# Main_Board.net
KiCad netlist of a schematic drawn in EAGLE
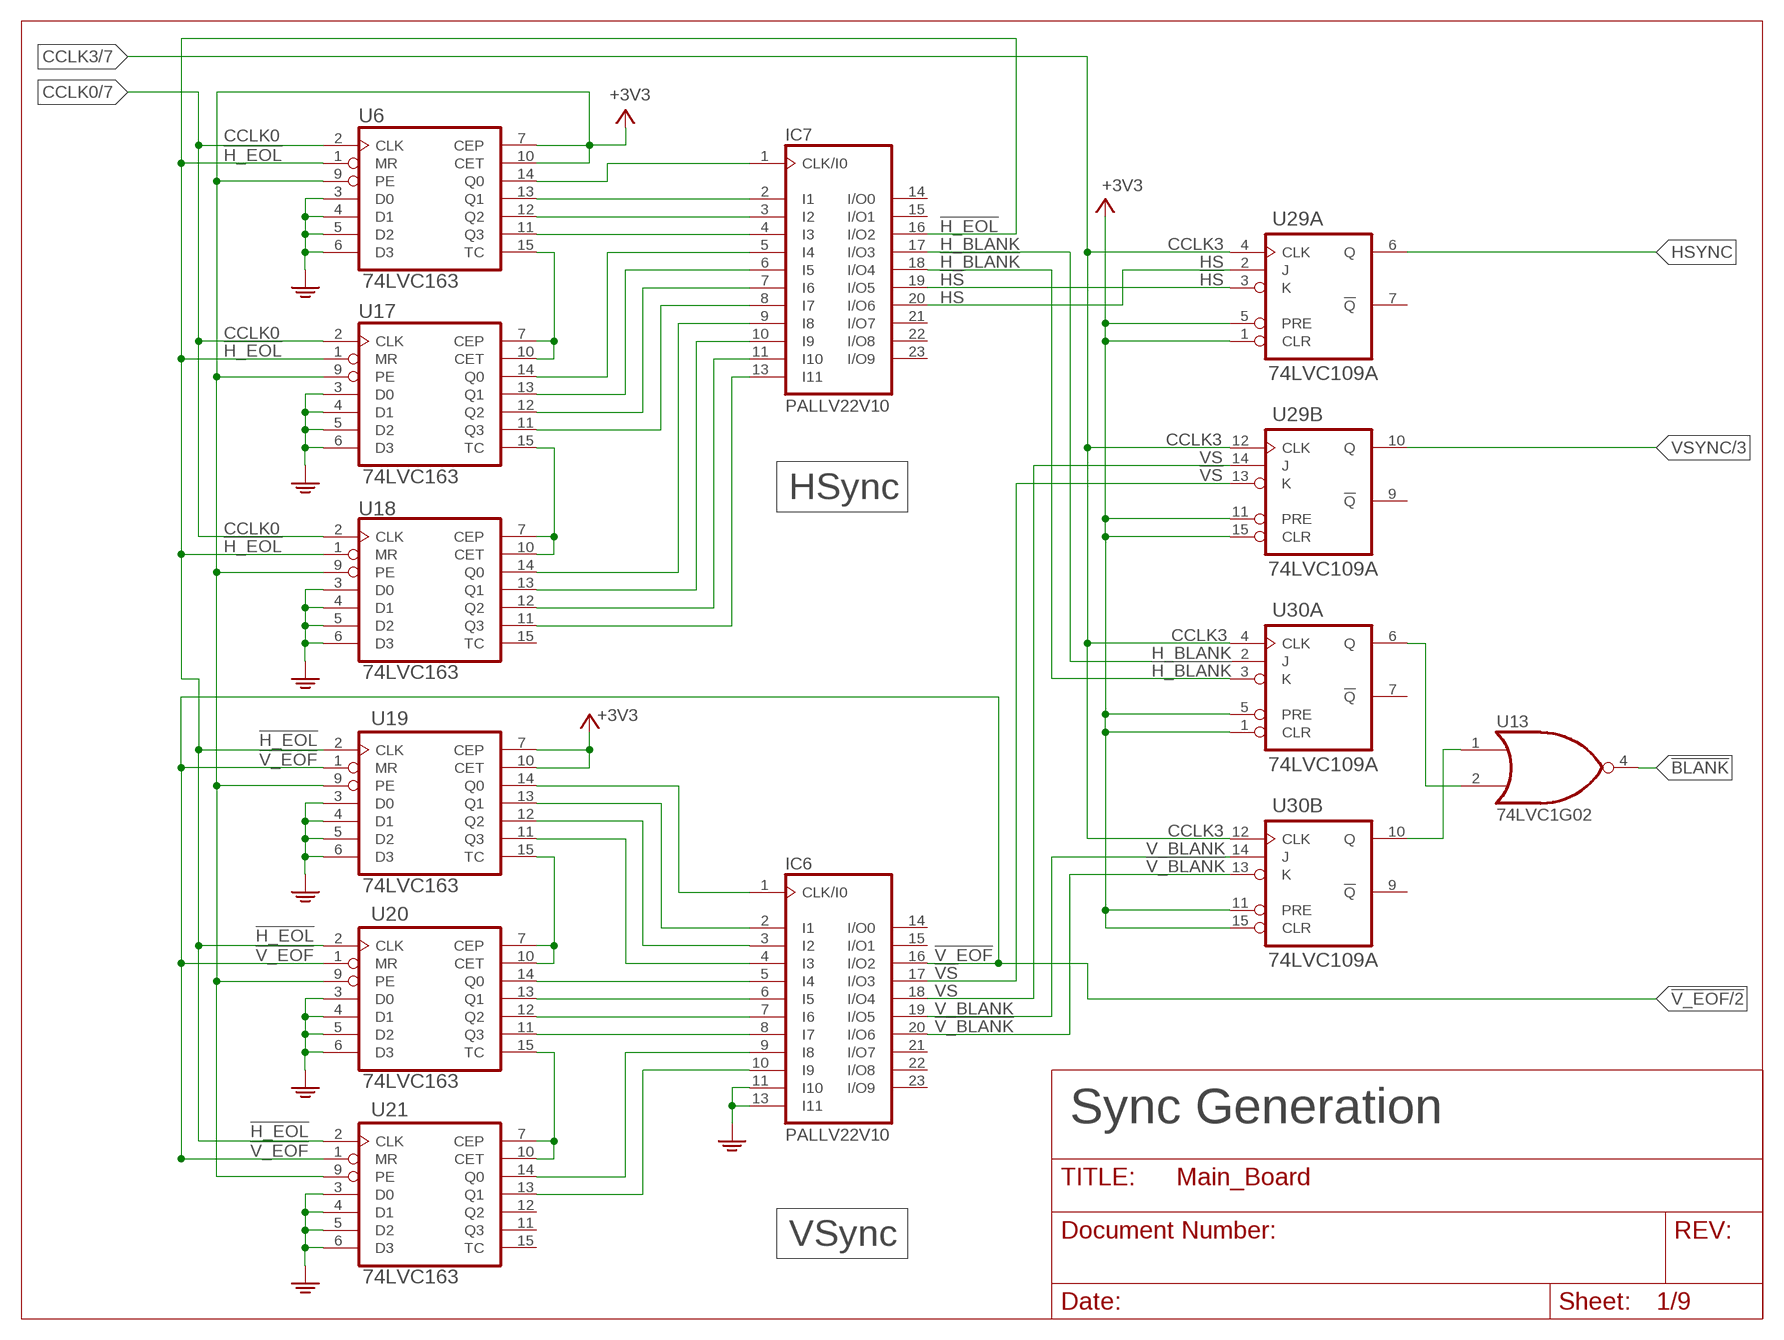
[diagram p0: schematic, sheet 1]
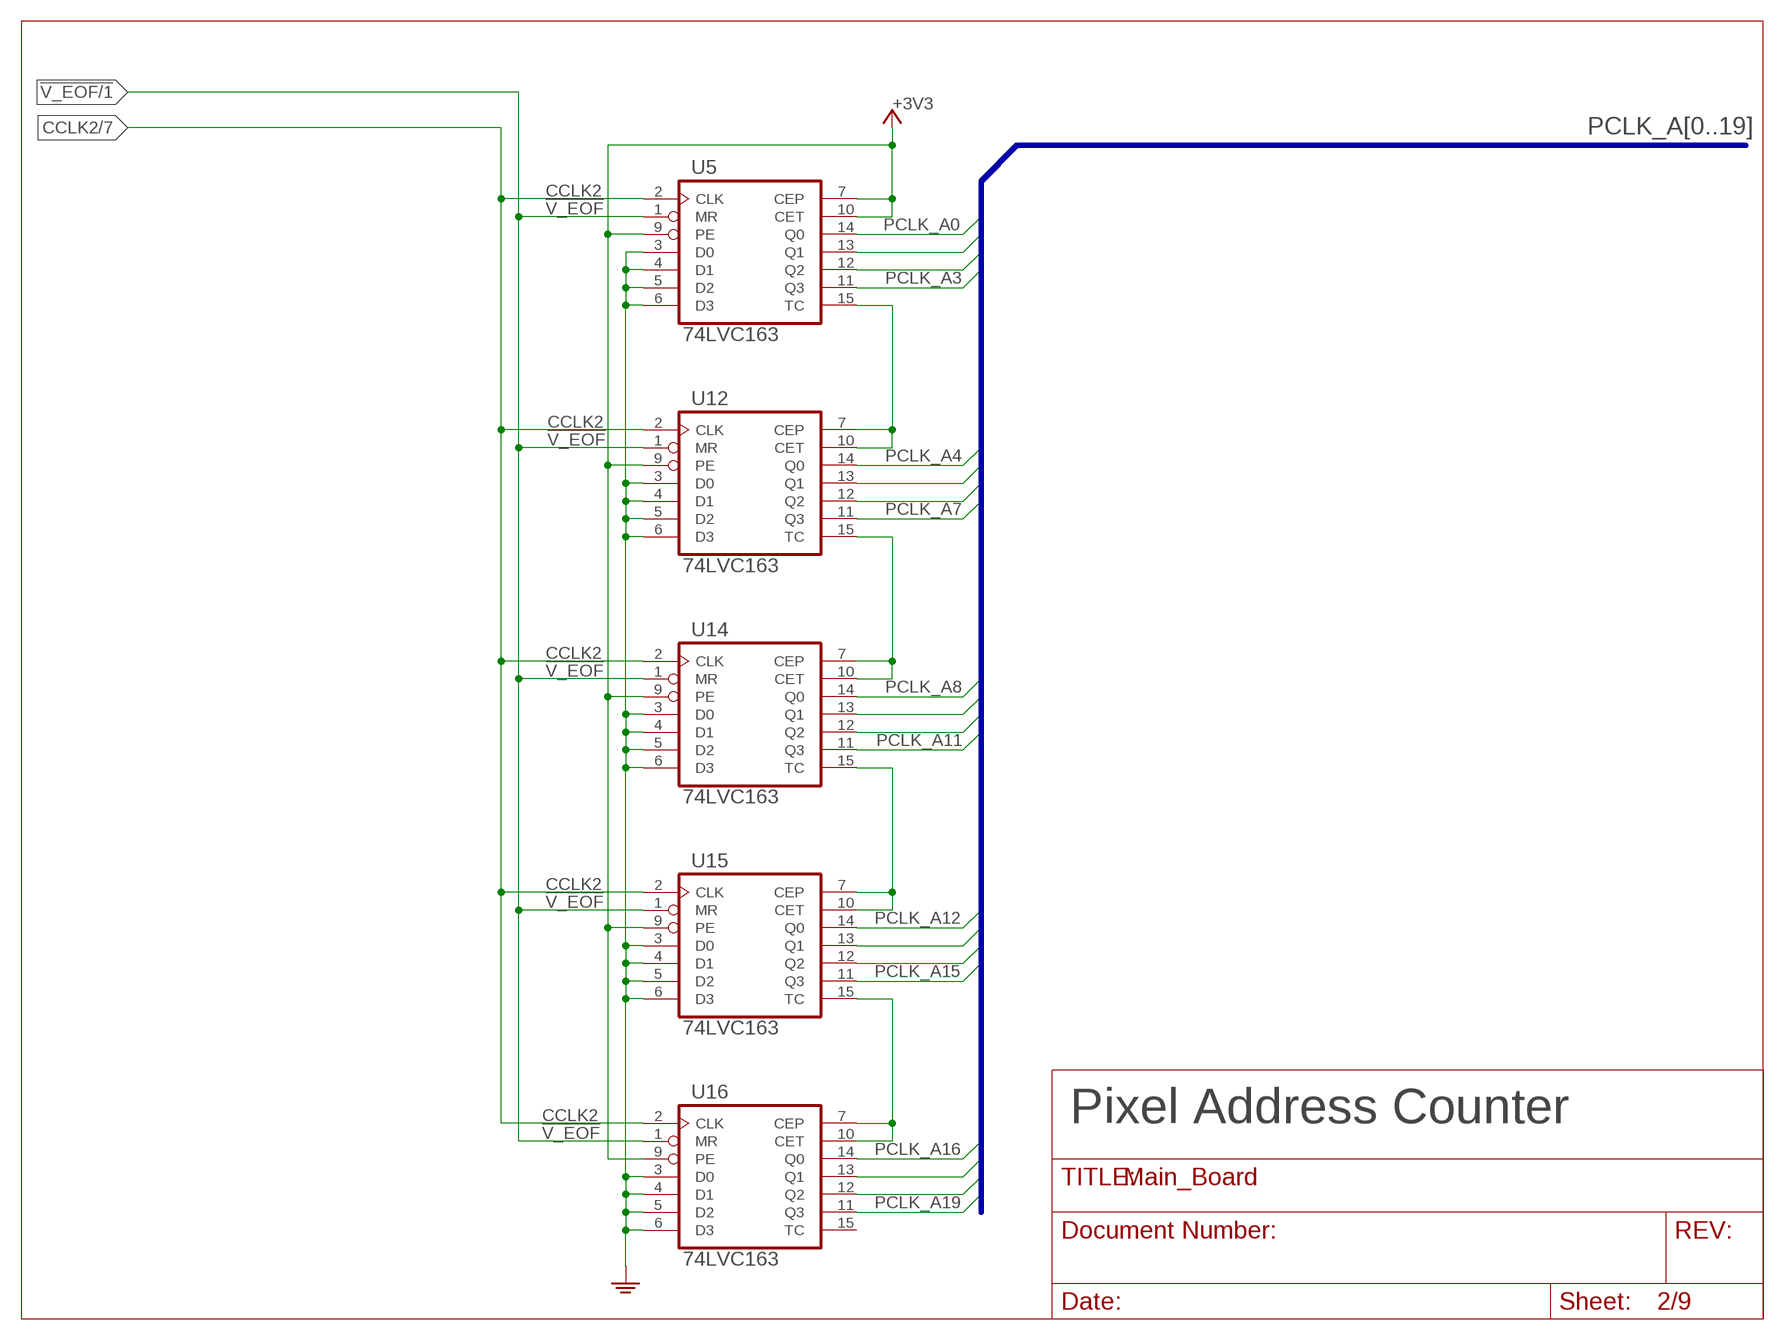
[diagram p1: schematic, sheet 2]
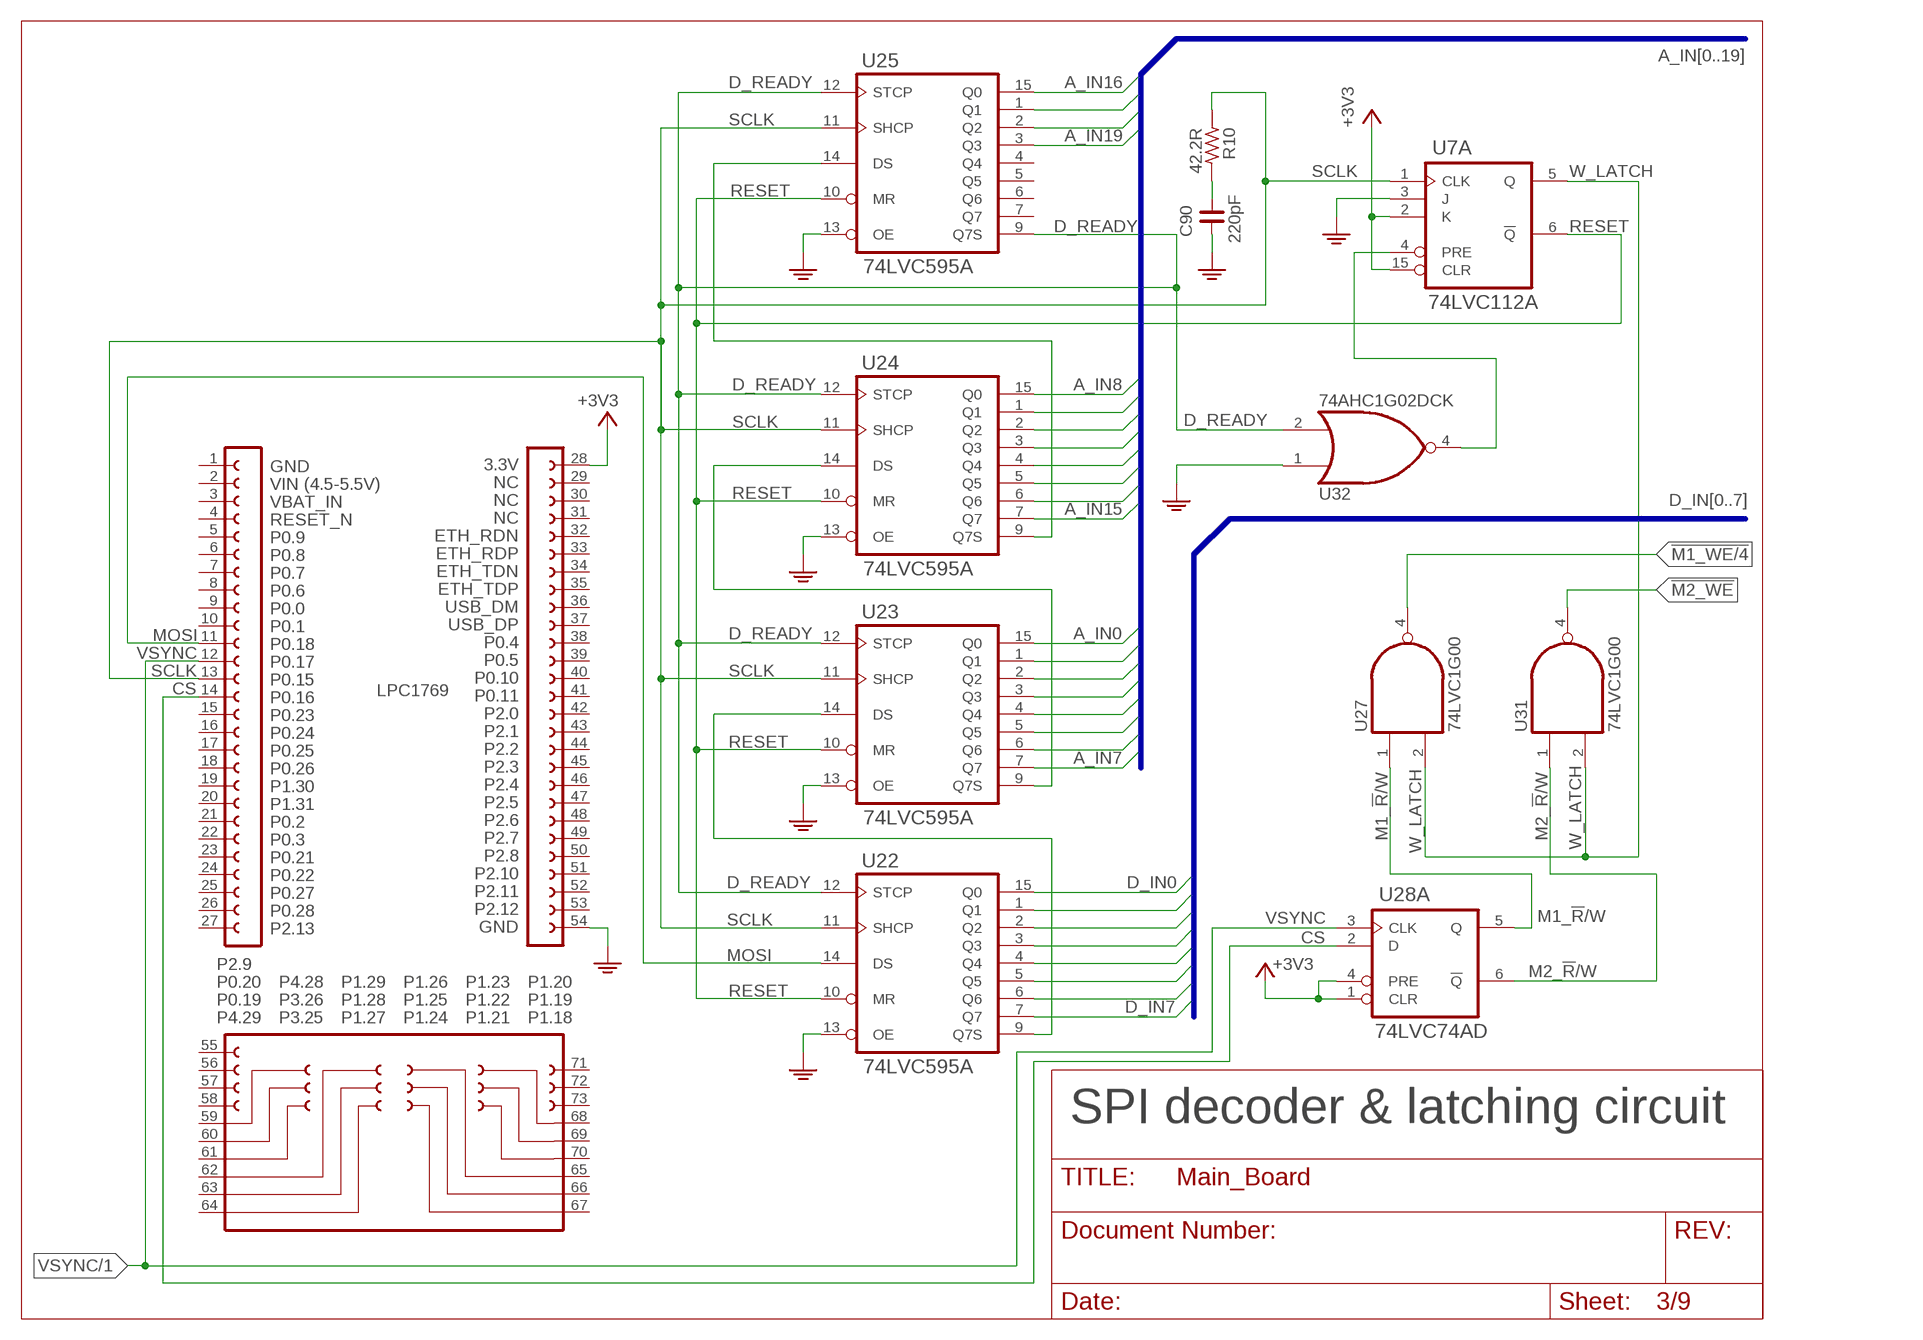
[diagram p2: schematic, sheet 3]
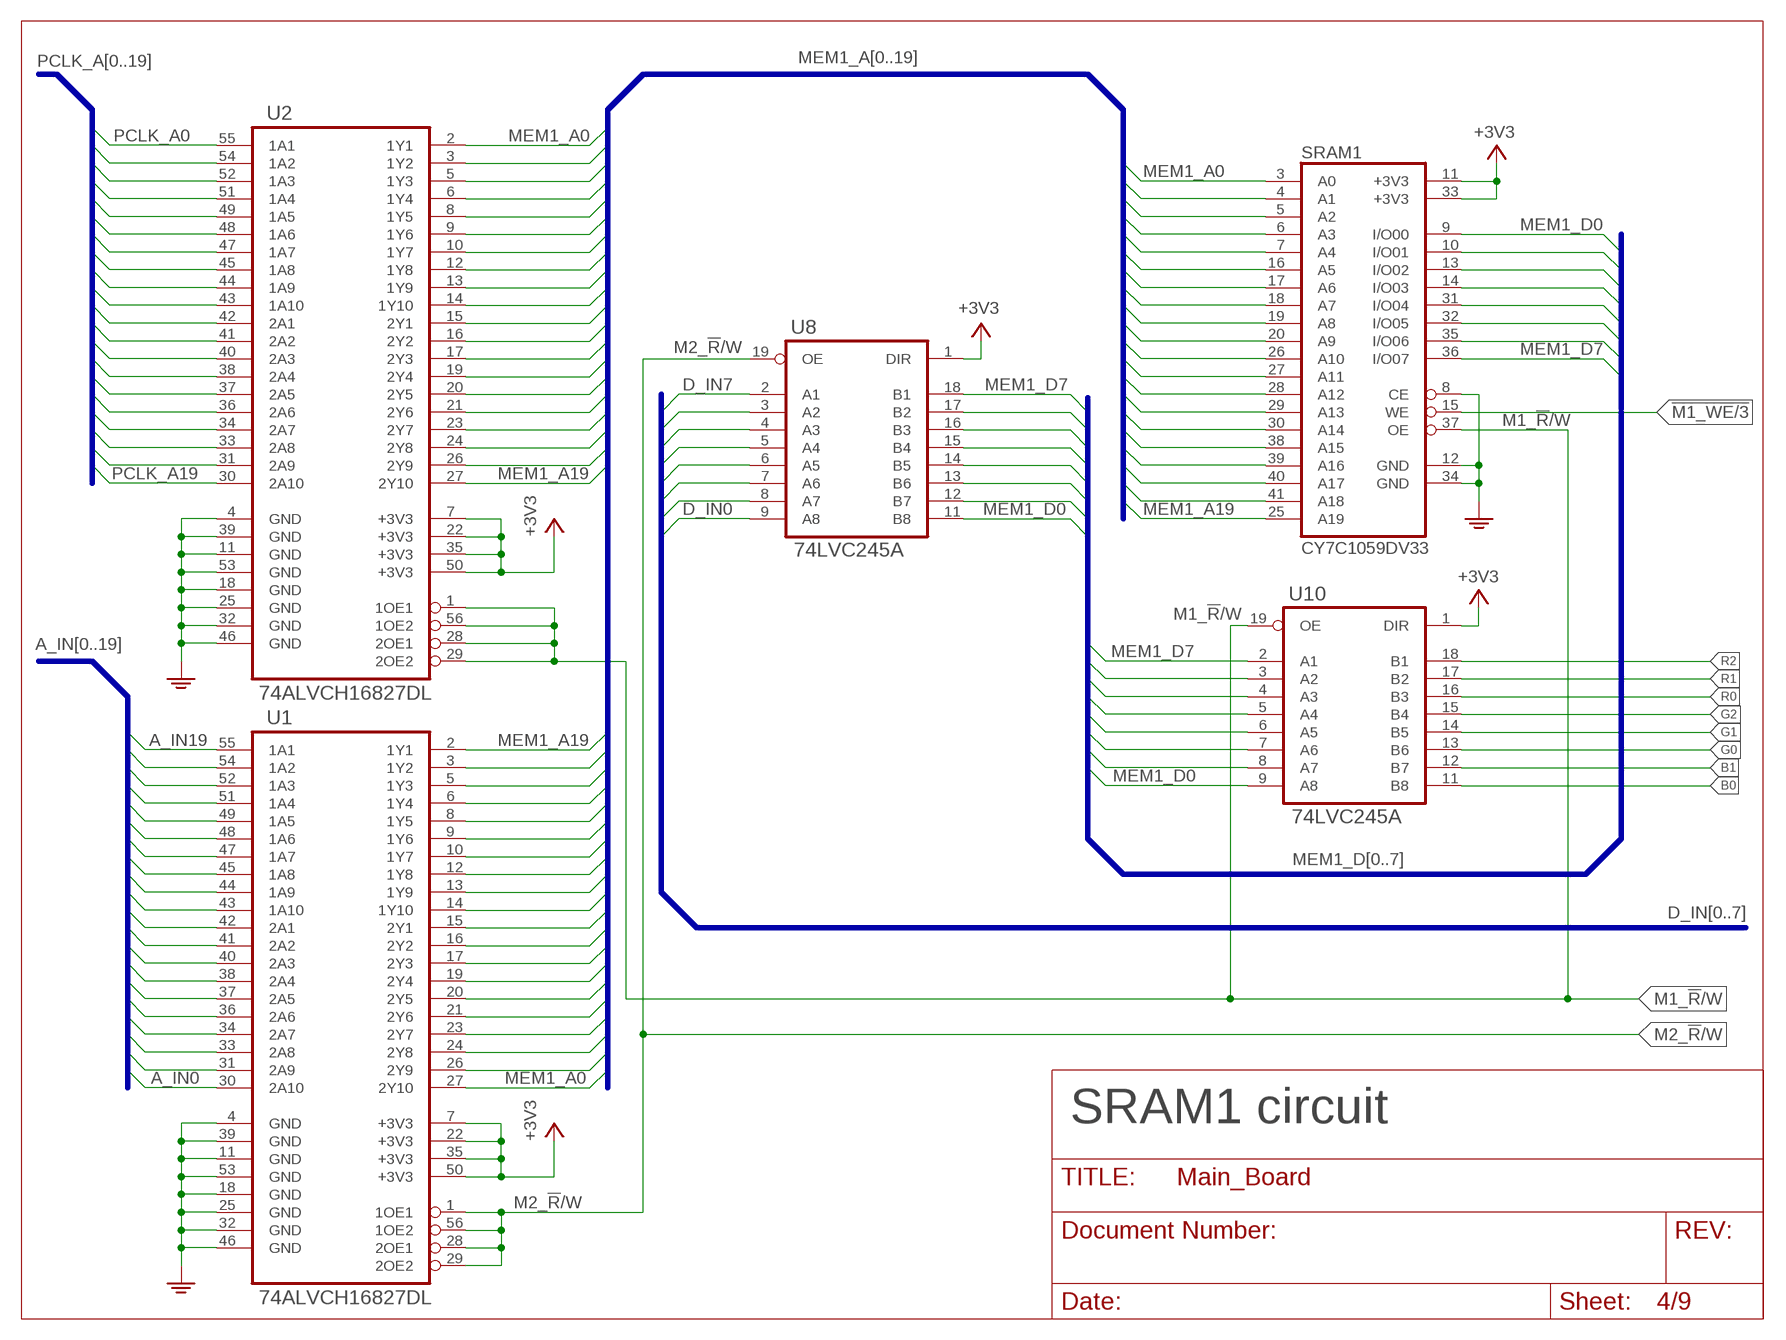
[diagram p3: schematic, sheet 4]
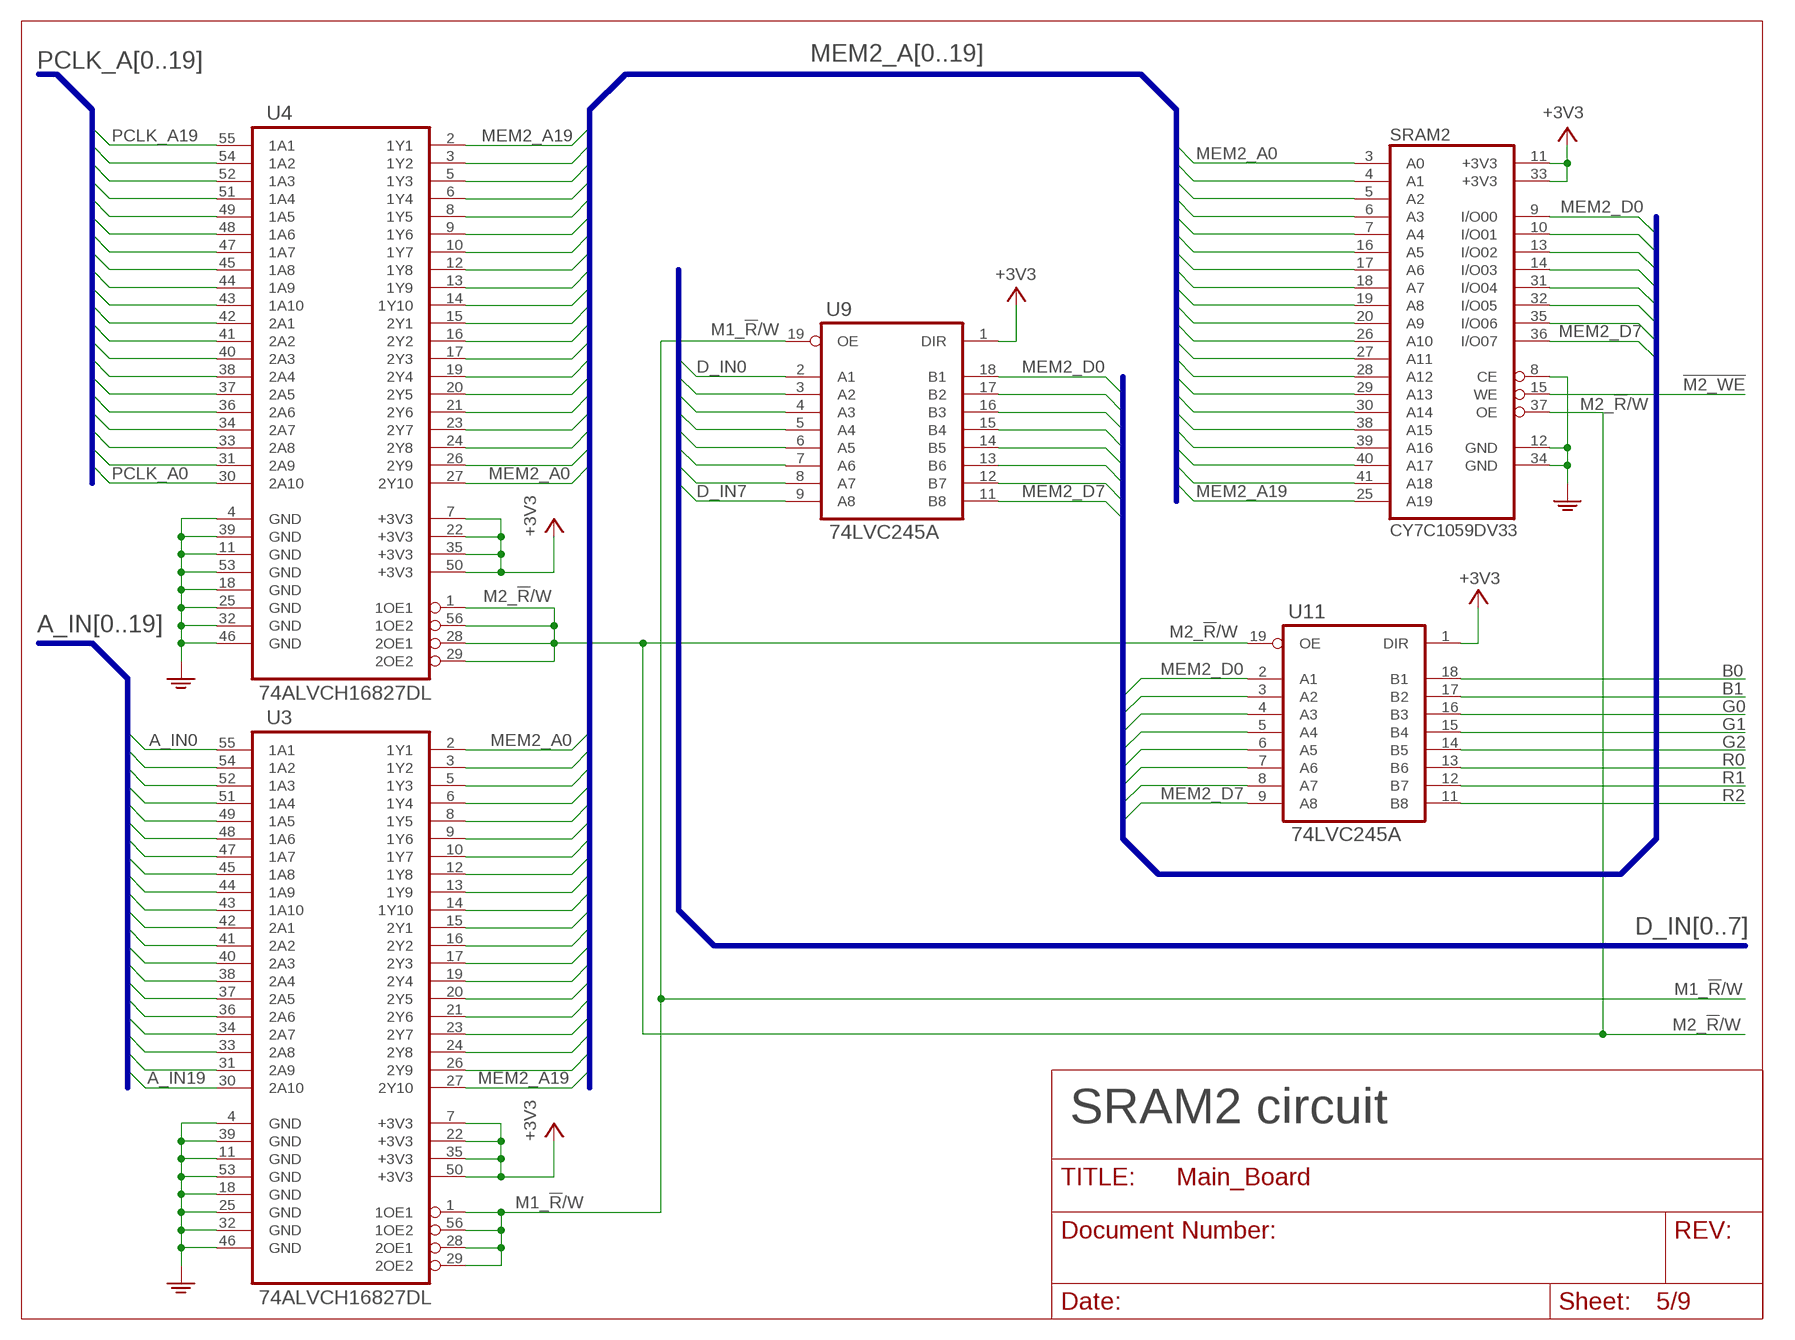
[diagram p4: schematic, sheet 5]
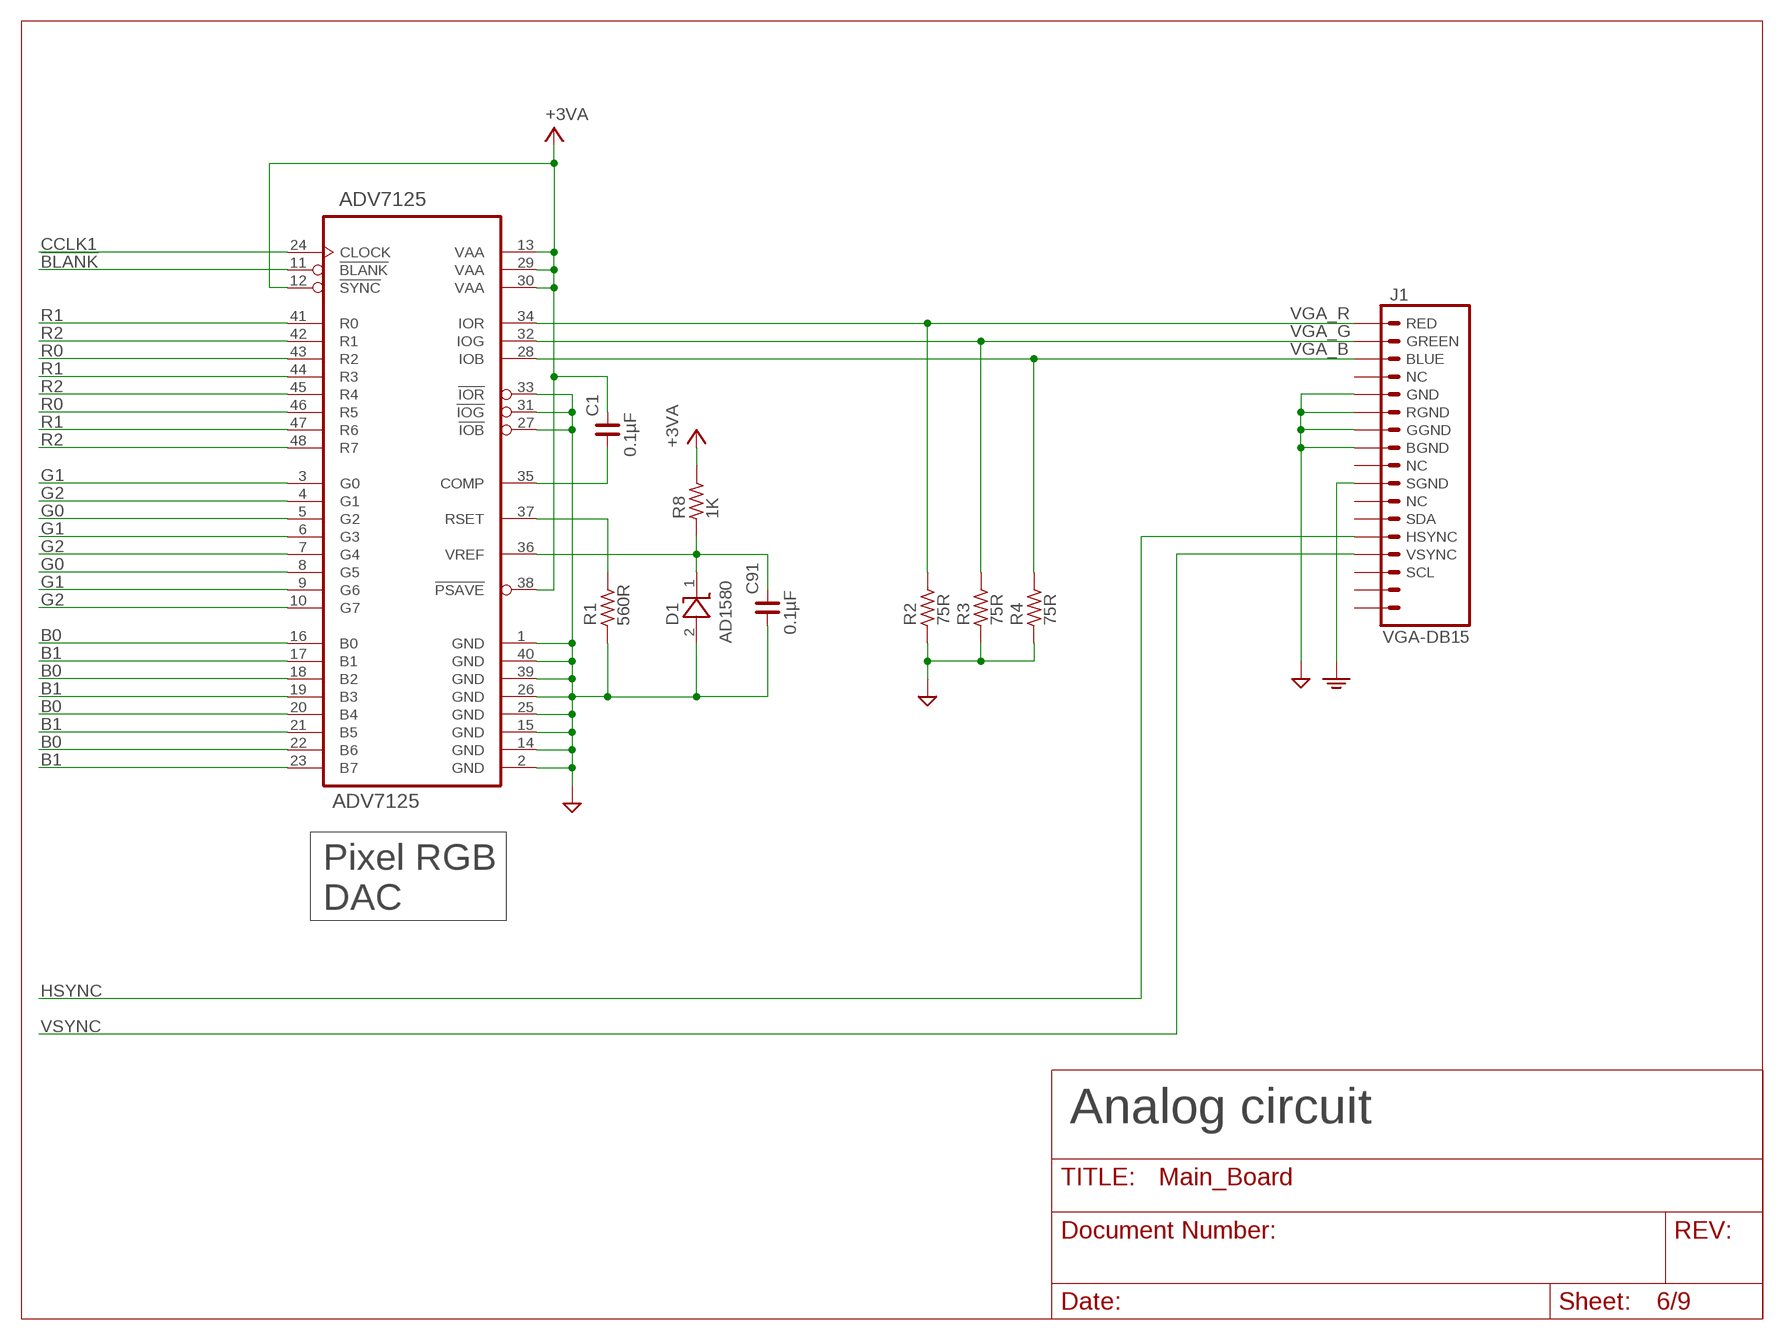
[diagram p5: schematic, sheet 6]
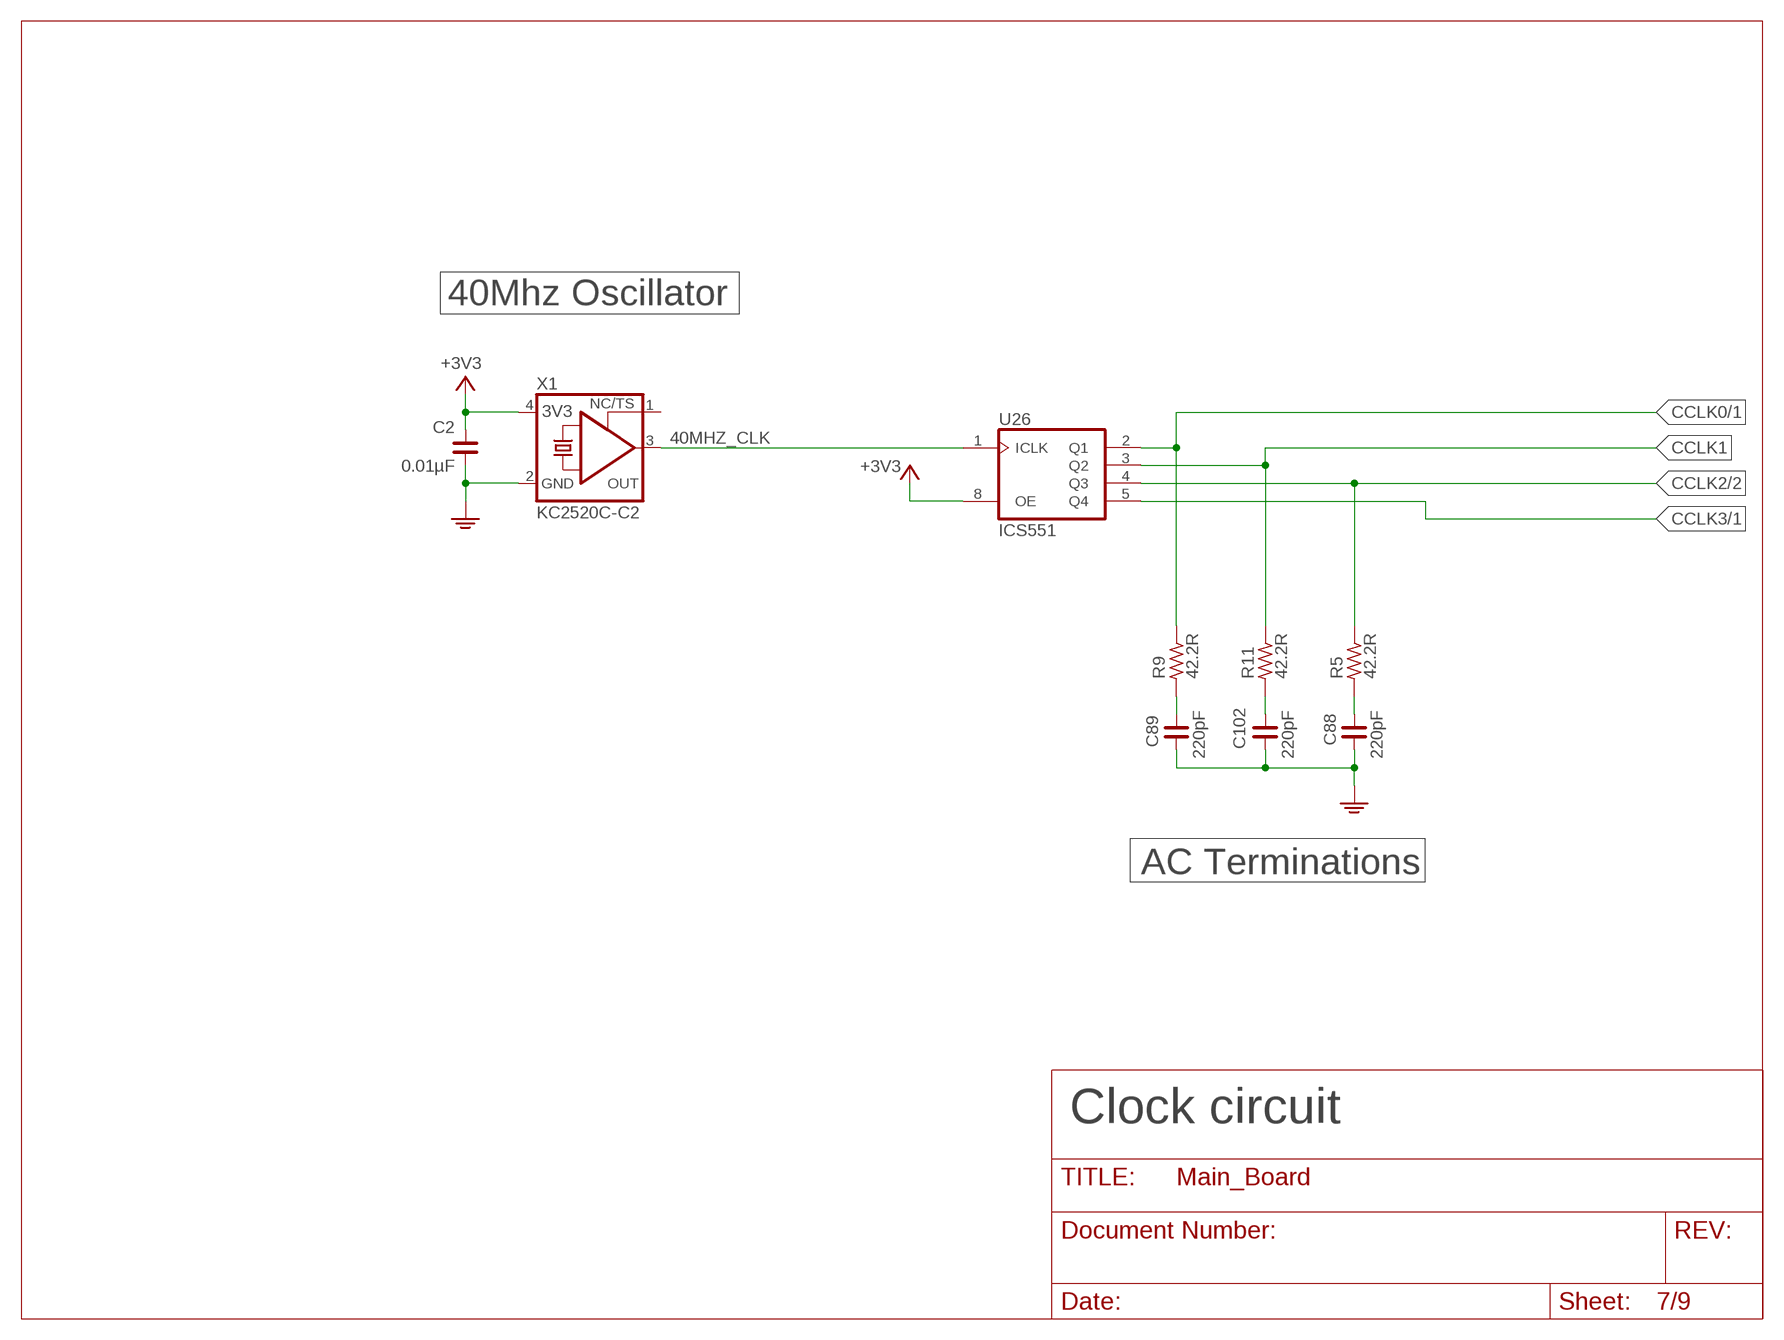
[diagram p6: schematic, sheet 7]
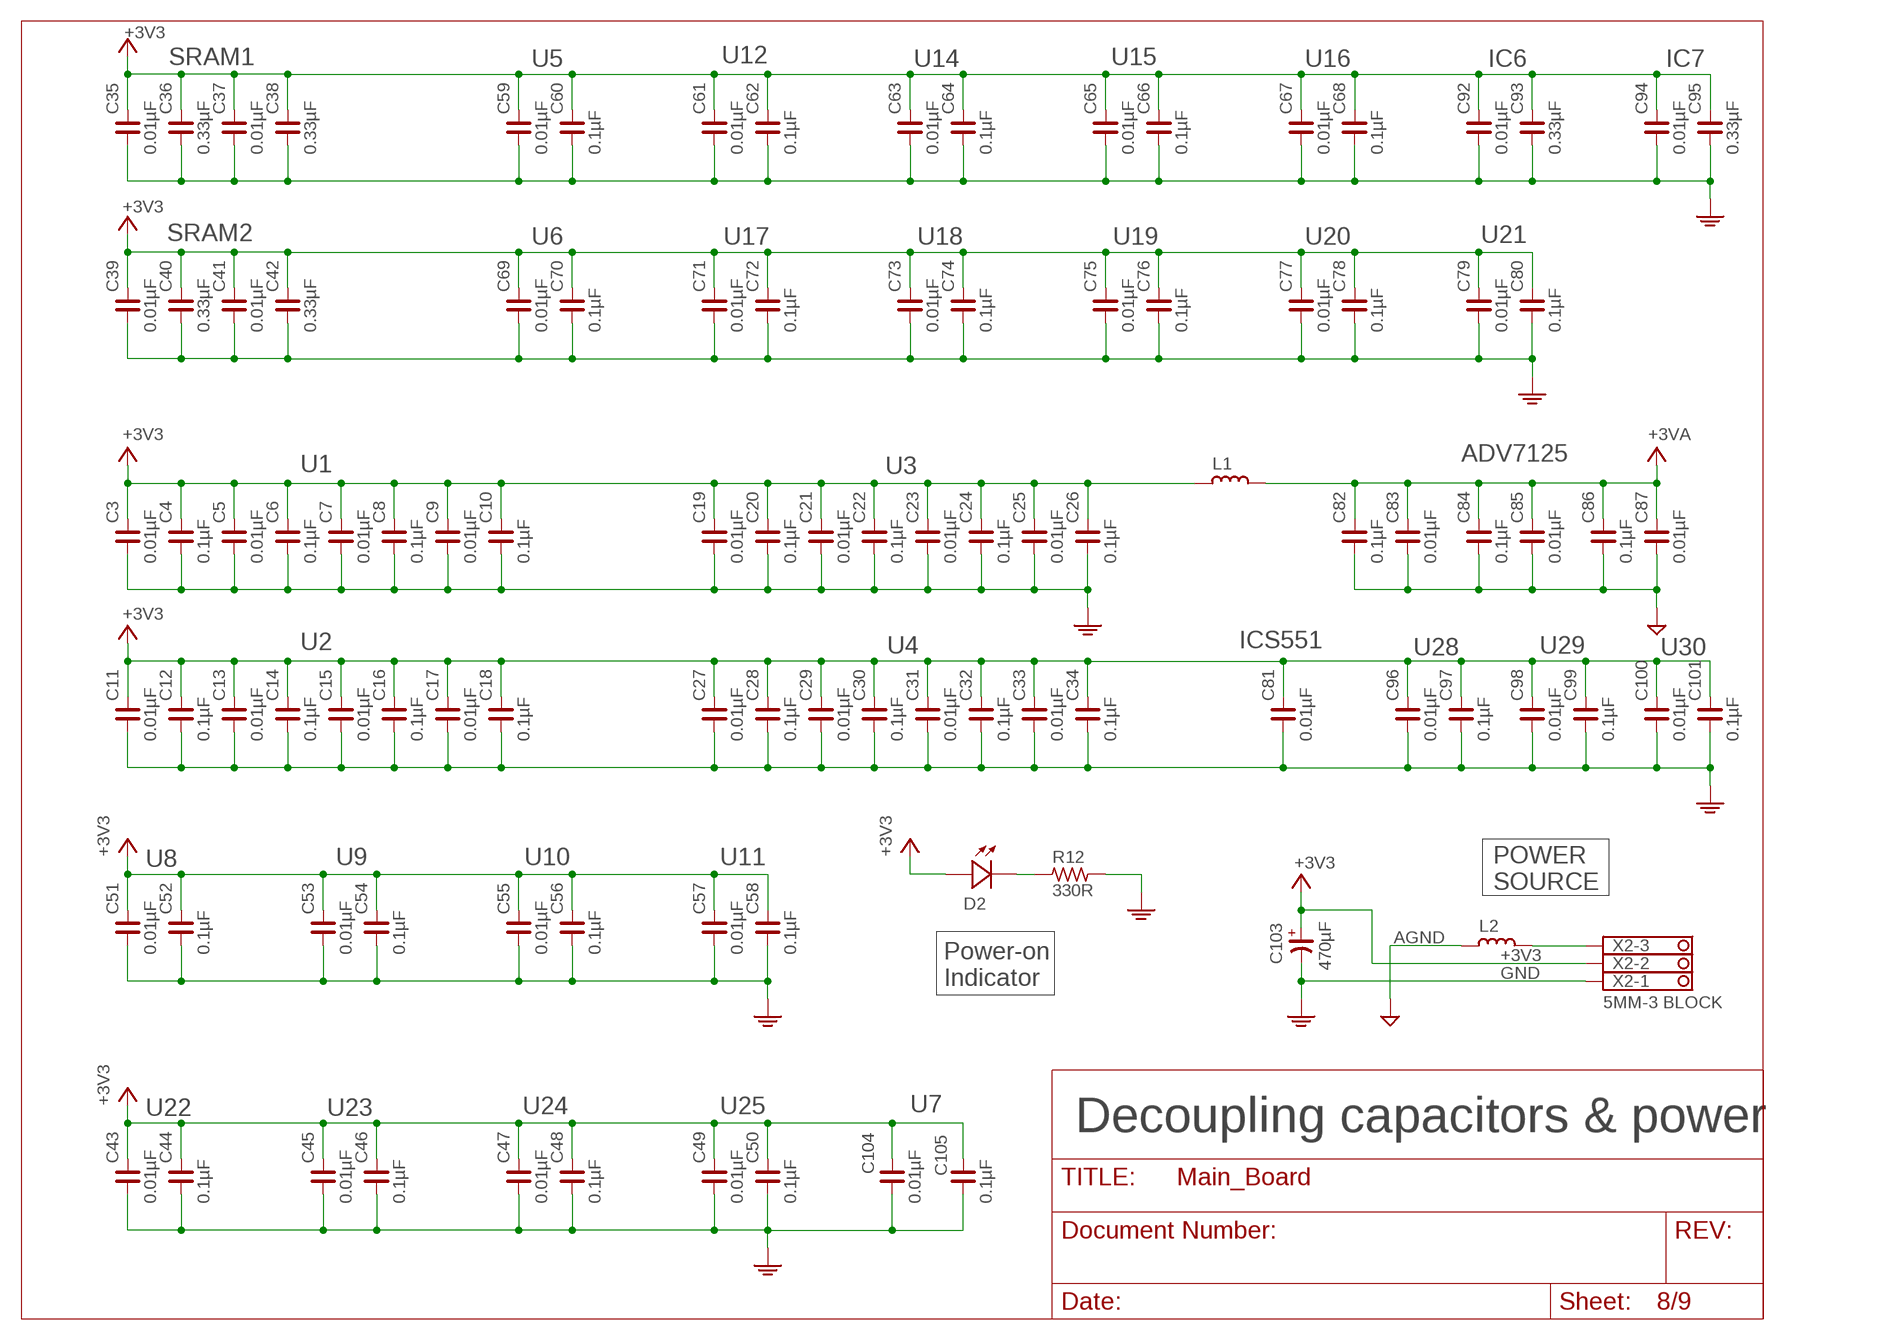
[diagram p7: schematic, sheet 8]
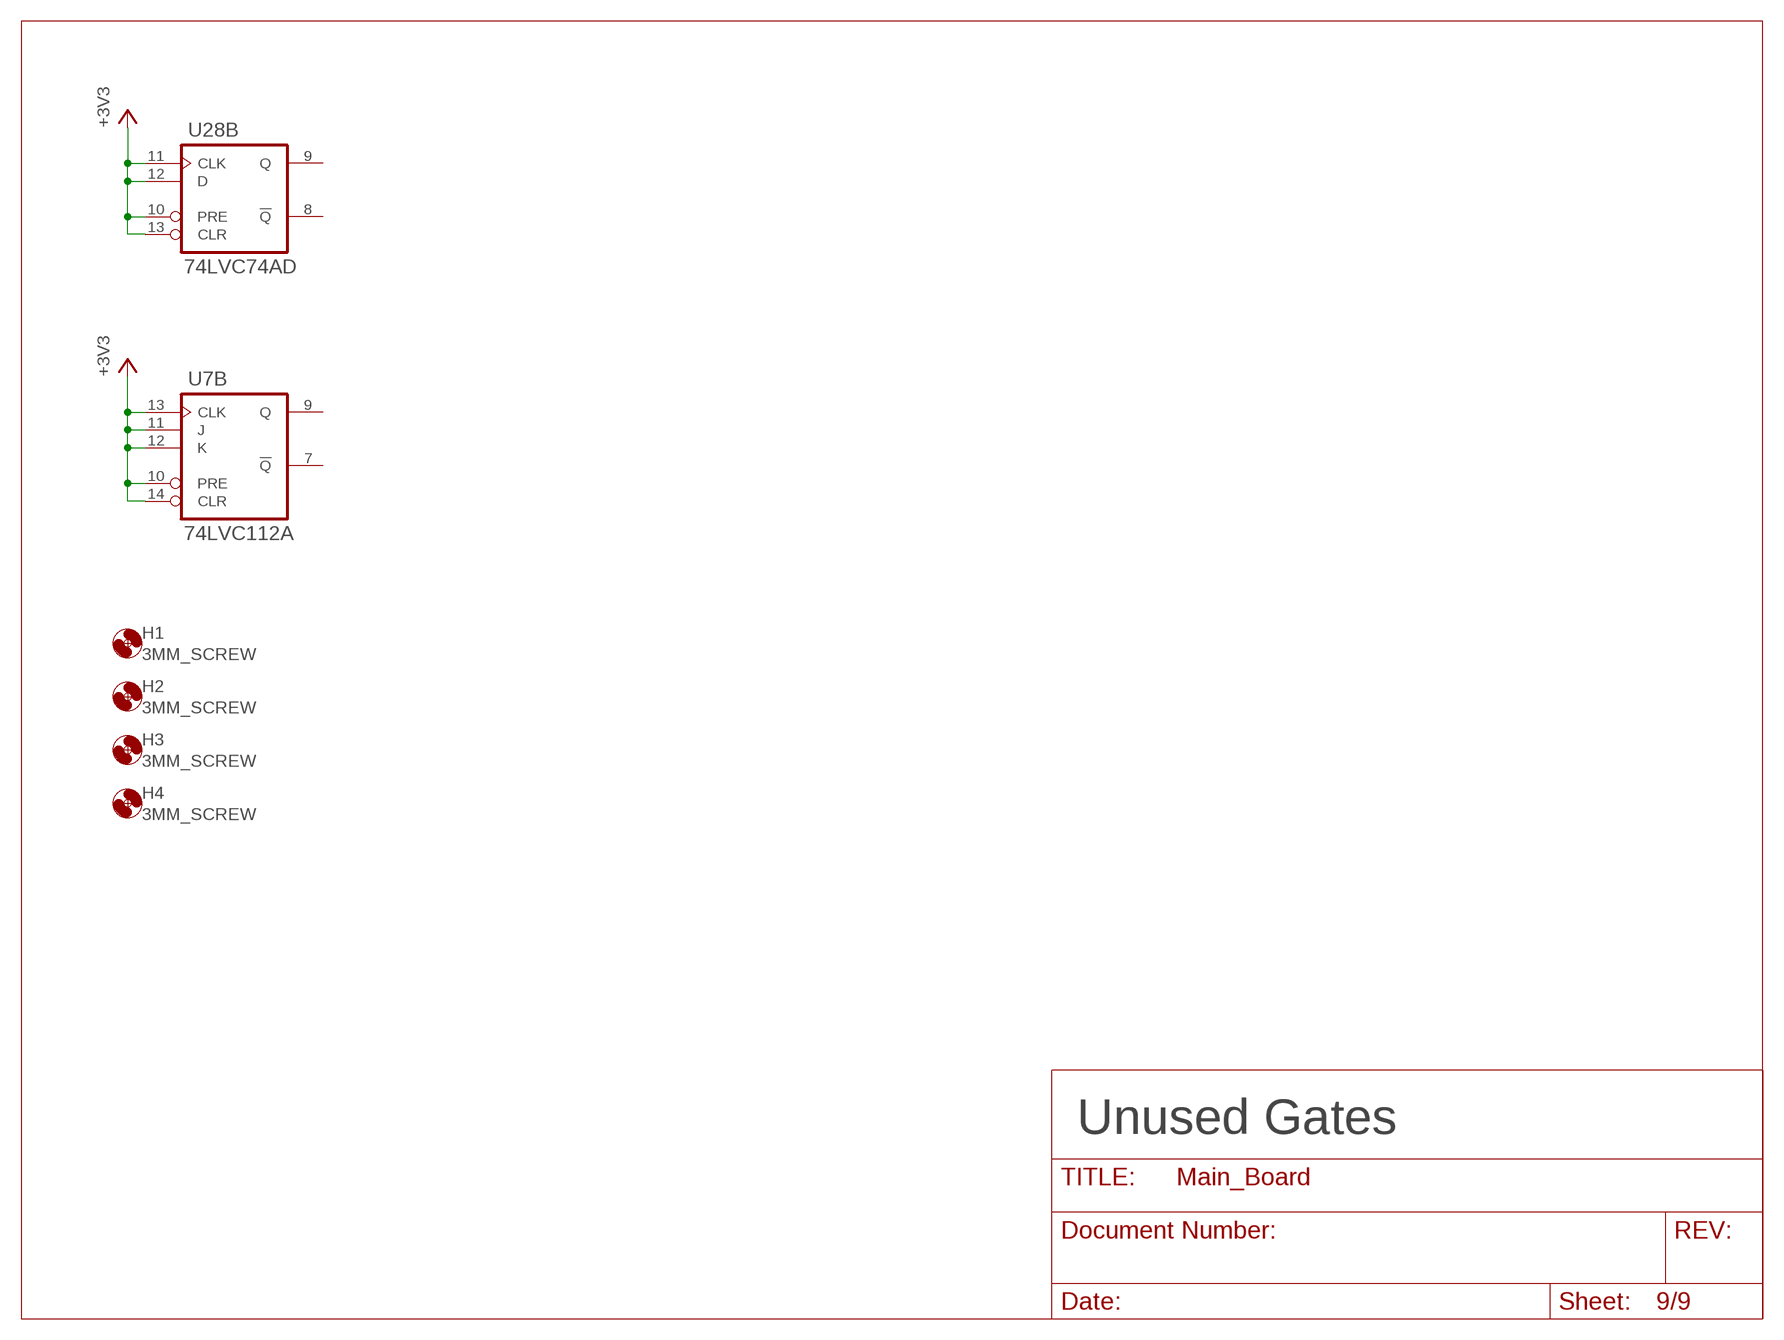
[diagram p8: schematic, sheet 9]

(export (version "E")
  (design (tool "Eeschema 10.0.6"))
  (components
    (comp (ref "C2")
      (value "0.01µF")
      (footprint "eagle-import:C0603")
      (libsource (lib "eagle-import") (part "C_0603"))
    )
    (comp (ref "C88")
      (value "220pF")
      (footprint "eagle-import:C0603")
      (libsource (lib "eagle-import") (part "C_0603"))
    )
    (comp (ref "C89")
      (value "220pF")
      (footprint "eagle-import:C0603")
      (libsource (lib "eagle-import") (part "C_0603"))
    )
    (comp (ref "C102")
      (value "220pF")
      (footprint "eagle-import:C0603")
      (libsource (lib "eagle-import") (part "C_0603"))
    )
    (comp (ref "R5")
      (value "42.2R")
      (footprint "eagle-import:R0603")
      (libsource (lib "eagle-import") (part "R_0603"))
    )
    (comp (ref "R9")
      (value "42.2R")
      (footprint "eagle-import:R0603")
      (libsource (lib "eagle-import") (part "R_0603"))
    )
    (comp (ref "R11")
      (value "42.2R")
      (footprint "eagle-import:R0603")
      (libsource (lib "eagle-import") (part "R_0603"))
    )
    (comp (ref "U26")
      (value "ICS551")
      (footprint "eagle-import:SO08(SOT96)")
      (libsource (lib "eagle-import") (part "ICS551"))
    )
    (comp (ref "X1")
      (value "KC2520C-C2")
      (footprint "eagle-import:OSCXO2.5X2.0")
      (libsource (lib "eagle-import") (part "KC2520C-C2"))
    )
    (comp (ref "C90")
      (value "220pF")
      (footprint "eagle-import:C0603")
      (libsource (lib "eagle-import") (part "C_0603"))
    )
    (comp (ref "LPC1769")
      (value "LPCXPRESSO_LPC1769")
      (footprint "eagle-import:LPCXPRESSO_LPC1769")
      (libsource (lib "eagle-import") (part "LPCXPRESSO_LPC1769"))
    )
    (comp (ref "R10")
      (value "42.2R")
      (footprint "eagle-import:R0603")
      (libsource (lib "eagle-import") (part "R_0603"))
    )
    (comp (ref "U7")
      (value "74LVC112A")
      (footprint "eagle-import:SO16D(SOT109)")
      (libsource (lib "eagle-import") (part "74LVC112A"))
    )
    (comp (ref "U22")
      (value "74LVC595A")
      (footprint "eagle-import:SO16D(SOT109)")
      (libsource (lib "eagle-import") (part "74LVC595A"))
    )
    (comp (ref "U23")
      (value "74LVC595A")
      (footprint "eagle-import:SO16D(SOT109)")
      (libsource (lib "eagle-import") (part "74LVC595A"))
    )
    (comp (ref "U24")
      (value "74LVC595A")
      (footprint "eagle-import:SO16D(SOT109)")
      (libsource (lib "eagle-import") (part "74LVC595A"))
    )
    (comp (ref "U25")
      (value "74LVC595A")
      (footprint "eagle-import:SO16D(SOT109)")
      (libsource (lib "eagle-import") (part "74LVC595A"))
    )
    (comp (ref "U27")
      (value "74LVC1G00")
      (footprint "eagle-import:SC70-5(SOT353)")
      (libsource (lib "eagle-import") (part "74LVC1G00"))
    )
    (comp (ref "U28")
      (value "74LVC74AD")
      (footprint "eagle-import:SO14(SOT108)")
      (libsource (lib "eagle-import") (part "74LVC74AD"))
    )
    (comp (ref "U31")
      (value "74LVC1G00")
      (footprint "eagle-import:SC70-5(SOT353)")
      (libsource (lib "eagle-import") (part "74LVC1G00"))
    )
    (comp (ref "U32")
      (value "74AHC1G02DCK")
      (footprint "eagle-import:SC70-5(SOT353)")
      (libsource (lib "eagle-import") (part "74AHC1G02DCKSC70-5"))
    )
    (comp (ref "U5")
      (value "74LVC163")
      (footprint "eagle-import:SO16D(SOT109)")
      (libsource (lib "eagle-import") (part "74LVC163"))
    )
    (comp (ref "U12")
      (value "74LVC163")
      (footprint "eagle-import:SO16D(SOT109)")
      (libsource (lib "eagle-import") (part "74LVC163"))
    )
    (comp (ref "U14")
      (value "74LVC163")
      (footprint "eagle-import:SO16D(SOT109)")
      (libsource (lib "eagle-import") (part "74LVC163"))
    )
    (comp (ref "U15")
      (value "74LVC163")
      (footprint "eagle-import:SO16D(SOT109)")
      (libsource (lib "eagle-import") (part "74LVC163"))
    )
    (comp (ref "U16")
      (value "74LVC163")
      (footprint "eagle-import:SO16D(SOT109)")
      (libsource (lib "eagle-import") (part "74LVC163"))
    )
    (comp (ref "IC6")
      (value "PALLV22V10")
      (footprint "eagle-import:DIP24")
      (libsource (lib "eagle-import") (part "PALLV22V10"))
    )
    (comp (ref "IC7")
      (value "PALLV22V10")
      (footprint "eagle-import:DIP24")
      (libsource (lib "eagle-import") (part "PALLV22V10"))
    )
    (comp (ref "U6")
      (value "74LVC163")
      (footprint "eagle-import:SO16D(SOT109)")
      (libsource (lib "eagle-import") (part "74LVC163"))
    )
    (comp (ref "U13")
      (value "74LVC1G02")
      (footprint "eagle-import:SC70-5(SOT353)")
      (libsource (lib "eagle-import") (part "74LVC1G02"))
    )
    (comp (ref "U17")
      (value "74LVC163")
      (footprint "eagle-import:SO16D(SOT109)")
      (libsource (lib "eagle-import") (part "74LVC163"))
    )
    (comp (ref "U18")
      (value "74LVC163")
      (footprint "eagle-import:SO16D(SOT109)")
      (libsource (lib "eagle-import") (part "74LVC163"))
    )
    (comp (ref "U19")
      (value "74LVC163")
      (footprint "eagle-import:SO16D(SOT109)")
      (libsource (lib "eagle-import") (part "74LVC163"))
    )
    (comp (ref "U20")
      (value "74LVC163")
      (footprint "eagle-import:SO16D(SOT109)")
      (libsource (lib "eagle-import") (part "74LVC163"))
    )
    (comp (ref "U21")
      (value "74LVC163")
      (footprint "eagle-import:SO16D(SOT109)")
      (libsource (lib "eagle-import") (part "74LVC163"))
    )
    (comp (ref "U29")
      (value "74LVC109A")
      (footprint "eagle-import:SO16D(SOT109)")
      (libsource (lib "eagle-import") (part "74LVC109A"))
    )
    (comp (ref "U30")
      (value "74LVC109A")
      (footprint "eagle-import:SO16D(SOT109)")
      (libsource (lib "eagle-import") (part "74LVC109A"))
    )
    (comp (ref "C3")
      (value "0.01µF")
      (footprint "eagle-import:C0603")
      (libsource (lib "eagle-import") (part "C_0603"))
    )
    (comp (ref "C4")
      (value "0.1µF")
      (footprint "eagle-import:C0603")
      (libsource (lib "eagle-import") (part "C_0603"))
    )
    (comp (ref "C5")
      (value "0.01µF")
      (footprint "eagle-import:C0603")
      (libsource (lib "eagle-import") (part "C_0603"))
    )
    (comp (ref "C6")
      (value "0.1µF")
      (footprint "eagle-import:C0603")
      (libsource (lib "eagle-import") (part "C_0603"))
    )
    (comp (ref "C7")
      (value "0.01µF")
      (footprint "eagle-import:C0603")
      (libsource (lib "eagle-import") (part "C_0603"))
    )
    (comp (ref "C8")
      (value "0.1µF")
      (footprint "eagle-import:C0603")
      (libsource (lib "eagle-import") (part "C_0603"))
    )
    (comp (ref "C9")
      (value "0.01µF")
      (footprint "eagle-import:C0603")
      (libsource (lib "eagle-import") (part "C_0603"))
    )
    (comp (ref "C10")
      (value "0.1µF")
      (footprint "eagle-import:C0603")
      (libsource (lib "eagle-import") (part "C_0603"))
    )
    (comp (ref "C11")
      (value "0.01µF")
      (footprint "eagle-import:C0603")
      (libsource (lib "eagle-import") (part "C_0603"))
    )
    (comp (ref "C12")
      (value "0.1µF")
      (footprint "eagle-import:C0603")
      (libsource (lib "eagle-import") (part "C_0603"))
    )
    (comp (ref "C13")
      (value "0.01µF")
      (footprint "eagle-import:C0603")
      (libsource (lib "eagle-import") (part "C_0603"))
    )
    (comp (ref "C14")
      (value "0.1µF")
      (footprint "eagle-import:C0603")
      (libsource (lib "eagle-import") (part "C_0603"))
    )
    (comp (ref "C15")
      (value "0.01µF")
      (footprint "eagle-import:C0603")
      (libsource (lib "eagle-import") (part "C_0603"))
    )
    (comp (ref "C16")
      (value "0.1µF")
      (footprint "eagle-import:C0603")
      (libsource (lib "eagle-import") (part "C_0603"))
    )
    (comp (ref "C17")
      (value "0.01µF")
      (footprint "eagle-import:C0603")
      (libsource (lib "eagle-import") (part "C_0603"))
    )
    (comp (ref "C18")
      (value "0.1µF")
      (footprint "eagle-import:C0603")
      (libsource (lib "eagle-import") (part "C_0603"))
    )
    (comp (ref "C19")
      (value "0.01µF")
      (footprint "eagle-import:C0603")
      (libsource (lib "eagle-import") (part "C_0603"))
    )
    (comp (ref "C20")
      (value "0.1µF")
      (footprint "eagle-import:C0603")
      (libsource (lib "eagle-import") (part "C_0603"))
    )
    (comp (ref "C21")
      (value "0.01µF")
      (footprint "eagle-import:C0603")
      (libsource (lib "eagle-import") (part "C_0603"))
    )
    (comp (ref "C22")
      (value "0.1µF")
      (footprint "eagle-import:C0603")
      (libsource (lib "eagle-import") (part "C_0603"))
    )
    (comp (ref "C23")
      (value "0.01µF")
      (footprint "eagle-import:C0603")
      (libsource (lib "eagle-import") (part "C_0603"))
    )
    (comp (ref "C24")
      (value "0.1µF")
      (footprint "eagle-import:C0603")
      (libsource (lib "eagle-import") (part "C_0603"))
    )
    (comp (ref "C25")
      (value "0.01µF")
      (footprint "eagle-import:C0603")
      (libsource (lib "eagle-import") (part "C_0603"))
    )
    (comp (ref "C26")
      (value "0.1µF")
      (footprint "eagle-import:C0603")
      (libsource (lib "eagle-import") (part "C_0603"))
    )
    (comp (ref "C27")
      (value "0.01µF")
      (footprint "eagle-import:C0603")
      (libsource (lib "eagle-import") (part "C_0603"))
    )
    (comp (ref "C28")
      (value "0.1µF")
      (footprint "eagle-import:C0603")
      (libsource (lib "eagle-import") (part "C_0603"))
    )
    (comp (ref "C29")
      (value "0.01µF")
      (footprint "eagle-import:C0603")
      (libsource (lib "eagle-import") (part "C_0603"))
    )
    (comp (ref "C30")
      (value "0.1µF")
      (footprint "eagle-import:C0603")
      (libsource (lib "eagle-import") (part "C_0603"))
    )
    (comp (ref "C31")
      (value "0.01µF")
      (footprint "eagle-import:C0603")
      (libsource (lib "eagle-import") (part "C_0603"))
    )
    (comp (ref "C32")
      (value "0.1µF")
      (footprint "eagle-import:C0603")
      (libsource (lib "eagle-import") (part "C_0603"))
    )
    (comp (ref "C33")
      (value "0.01µF")
      (footprint "eagle-import:C0603")
      (libsource (lib "eagle-import") (part "C_0603"))
    )
    (comp (ref "C34")
      (value "0.1µF")
      (footprint "eagle-import:C0603")
      (libsource (lib "eagle-import") (part "C_0603"))
    )
    (comp (ref "C35")
      (value "0.01µF")
      (footprint "eagle-import:C0603")
      (libsource (lib "eagle-import") (part "C_0603"))
    )
    (comp (ref "C36")
      (value "0.33µF")
      (footprint "eagle-import:C0603")
      (libsource (lib "eagle-import") (part "C_0603"))
    )
    (comp (ref "C37")
      (value "0.01µF")
      (footprint "eagle-import:C0603")
      (libsource (lib "eagle-import") (part "C_0603"))
    )
    (comp (ref "C38")
      (value "0.33µF")
      (footprint "eagle-import:C0603")
      (libsource (lib "eagle-import") (part "C_0603"))
    )
    (comp (ref "C39")
      (value "0.01µF")
      (footprint "eagle-import:C0603")
      (libsource (lib "eagle-import") (part "C_0603"))
    )
    (comp (ref "C40")
      (value "0.33µF")
      (footprint "eagle-import:C0603")
      (libsource (lib "eagle-import") (part "C_0603"))
    )
    (comp (ref "C41")
      (value "0.01µF")
      (footprint "eagle-import:C0603")
      (libsource (lib "eagle-import") (part "C_0603"))
    )
    (comp (ref "C42")
      (value "0.33µF")
      (footprint "eagle-import:C0603")
      (libsource (lib "eagle-import") (part "C_0603"))
    )
    (comp (ref "C43")
      (value "0.01µF")
      (footprint "eagle-import:C0603")
      (libsource (lib "eagle-import") (part "C_0603"))
    )
    (comp (ref "C44")
      (value "0.1µF")
      (footprint "eagle-import:C0603")
      (libsource (lib "eagle-import") (part "C_0603"))
    )
    (comp (ref "C45")
      (value "0.01µF")
      (footprint "eagle-import:C0603")
      (libsource (lib "eagle-import") (part "C_0603"))
    )
    (comp (ref "C46")
      (value "0.1µF")
      (footprint "eagle-import:C0603")
      (libsource (lib "eagle-import") (part "C_0603"))
    )
    (comp (ref "C47")
      (value "0.01µF")
      (footprint "eagle-import:C0603")
      (fields (field (name "SPICEPREFIX") "C"))
      (libsource (lib "eagle-import") (part "C_0603"))
    )
    (comp (ref "C48")
      (value "0.1µF")
      (footprint "eagle-import:C0603")
      (libsource (lib "eagle-import") (part "C_0603"))
    )
    (comp (ref "C49")
      (value "0.01µF")
      (footprint "eagle-import:C0603")
      (libsource (lib "eagle-import") (part "C_0603"))
    )
    (comp (ref "C50")
      (value "0.1µF")
      (footprint "eagle-import:C0603")
      (libsource (lib "eagle-import") (part "C_0603"))
    )
    (comp (ref "C51")
      (value "0.01µF")
      (footprint "eagle-import:C0603")
      (libsource (lib "eagle-import") (part "C_0603"))
    )
    (comp (ref "C52")
      (value "0.1µF")
      (footprint "eagle-import:C0603")
      (libsource (lib "eagle-import") (part "C_0603"))
    )
    (comp (ref "C53")
      (value "0.01µF")
      (footprint "eagle-import:C0603")
      (libsource (lib "eagle-import") (part "C_0603"))
    )
    (comp (ref "C54")
      (value "0.1µF")
      (footprint "eagle-import:C0603")
      (libsource (lib "eagle-import") (part "C_0603"))
    )
    (comp (ref "C55")
      (value "0.01µF")
      (footprint "eagle-import:C0603")
      (libsource (lib "eagle-import") (part "C_0603"))
    )
    (comp (ref "C56")
      (value "0.1µF")
      (footprint "eagle-import:C0603")
      (libsource (lib "eagle-import") (part "C_0603"))
    )
    (comp (ref "C57")
      (value "0.01µF")
      (footprint "eagle-import:C0603")
      (libsource (lib "eagle-import") (part "C_0603"))
    )
    (comp (ref "C58")
      (value "0.1µF")
      (footprint "eagle-import:C0603")
      (libsource (lib "eagle-import") (part "C_0603"))
    )
    (comp (ref "C59")
      (value "0.01µF")
      (footprint "eagle-import:C0603")
      (libsource (lib "eagle-import") (part "C_0603"))
    )
    (comp (ref "C60")
      (value "0.1µF")
      (footprint "eagle-import:C0603")
      (libsource (lib "eagle-import") (part "C_0603"))
    )
    (comp (ref "C61")
      (value "0.01µF")
      (footprint "eagle-import:C0603")
      (libsource (lib "eagle-import") (part "C_0603"))
    )
    (comp (ref "C62")
      (value "0.1µF")
      (footprint "eagle-import:C0603")
      (libsource (lib "eagle-import") (part "C_0603"))
    )
    (comp (ref "C63")
      (value "0.01µF")
      (footprint "eagle-import:C0603")
      (libsource (lib "eagle-import") (part "C_0603"))
    )
    (comp (ref "C64")
      (value "0.1µF")
      (footprint "eagle-import:C0603")
      (libsource (lib "eagle-import") (part "C_0603"))
    )
    (comp (ref "C65")
      (value "0.01µF")
      (footprint "eagle-import:C0603")
      (libsource (lib "eagle-import") (part "C_0603"))
    )
    (comp (ref "C66")
      (value "0.1µF")
      (footprint "eagle-import:C0603")
      (libsource (lib "eagle-import") (part "C_0603"))
    )
    (comp (ref "C67")
      (value "0.01µF")
      (footprint "eagle-import:C0603")
      (libsource (lib "eagle-import") (part "C_0603"))
    )
    (comp (ref "C68")
      (value "0.1µF")
      (footprint "eagle-import:C0603")
      (libsource (lib "eagle-import") (part "C_0603"))
    )
    (comp (ref "C69")
      (value "0.01µF")
      (footprint "eagle-import:C0603")
      (libsource (lib "eagle-import") (part "C_0603"))
    )
    (comp (ref "C70")
      (value "0.1µF")
      (footprint "eagle-import:C0603")
      (libsource (lib "eagle-import") (part "C_0603"))
    )
    (comp (ref "C71")
      (value "0.01µF")
      (footprint "eagle-import:C0603")
      (libsource (lib "eagle-import") (part "C_0603"))
    )
    (comp (ref "C72")
      (value "0.1µF")
      (footprint "eagle-import:C0603")
      (libsource (lib "eagle-import") (part "C_0603"))
    )
    (comp (ref "C73")
      (value "0.01µF")
      (footprint "eagle-import:C0603")
      (libsource (lib "eagle-import") (part "C_0603"))
    )
    (comp (ref "C74")
      (value "0.1µF")
      (footprint "eagle-import:C0603")
      (libsource (lib "eagle-import") (part "C_0603"))
    )
    (comp (ref "C75")
      (value "0.01µF")
      (footprint "eagle-import:C0603")
      (libsource (lib "eagle-import") (part "C_0603"))
    )
    (comp (ref "C76")
      (value "0.1µF")
      (footprint "eagle-import:C0603")
      (libsource (lib "eagle-import") (part "C_0603"))
    )
    (comp (ref "C77")
      (value "0.01µF")
      (footprint "eagle-import:C0603")
      (libsource (lib "eagle-import") (part "C_0603"))
    )
    (comp (ref "C78")
      (value "0.1µF")
      (footprint "eagle-import:C0603")
      (libsource (lib "eagle-import") (part "C_0603"))
    )
    (comp (ref "C79")
      (value "0.01µF")
      (footprint "eagle-import:C0603")
      (libsource (lib "eagle-import") (part "C_0603"))
    )
    (comp (ref "C80")
      (value "0.1µF")
      (footprint "eagle-import:C0603")
      (libsource (lib "eagle-import") (part "C_0603"))
    )
    (comp (ref "C81")
      (value "0.01µF")
      (footprint "eagle-import:C0603")
      (libsource (lib "eagle-import") (part "C_0603"))
    )
    (comp (ref "C82")
      (value "0.1µF")
      (footprint "eagle-import:C0603")
      (libsource (lib "eagle-import") (part "C_0603"))
    )
    (comp (ref "C83")
      (value "0.01µF")
      (footprint "eagle-import:C0603")
      (libsource (lib "eagle-import") (part "C_0603"))
    )
    (comp (ref "C84")
      (value "0.1µF")
      (footprint "eagle-import:C0603")
      (libsource (lib "eagle-import") (part "C_0603"))
    )
    (comp (ref "C85")
      (value "0.01µF")
      (footprint "eagle-import:C0603")
      (libsource (lib "eagle-import") (part "C_0603"))
    )
    (comp (ref "C86")
      (value "0.1µF")
      (footprint "eagle-import:C0603")
      (libsource (lib "eagle-import") (part "C_0603"))
    )
    (comp (ref "C87")
      (value "0.01µF")
      (footprint "eagle-import:C0603")
      (libsource (lib "eagle-import") (part "C_0603"))
    )
    (comp (ref "C92")
      (value "0.01µF")
      (footprint "eagle-import:C0603")
      (libsource (lib "eagle-import") (part "C_0603"))
    )
    (comp (ref "C93")
      (value "0.33µF")
      (footprint "eagle-import:C0603")
      (libsource (lib "eagle-import") (part "C_0603"))
    )
    (comp (ref "C94")
      (value "0.01µF")
      (footprint "eagle-import:C0603")
      (libsource (lib "eagle-import") (part "C_0603"))
    )
    (comp (ref "C95")
      (value "0.33µF")
      (footprint "eagle-import:C0603")
      (libsource (lib "eagle-import") (part "C_0603"))
    )
    (comp (ref "C96")
      (value "0.01µF")
      (footprint "eagle-import:C0603")
      (libsource (lib "eagle-import") (part "C_0603"))
    )
    (comp (ref "C97")
      (value "0.1µF")
      (footprint "eagle-import:C0603")
      (libsource (lib "eagle-import") (part "C_0603"))
    )
    (comp (ref "C98")
      (value "0.01µF")
      (footprint "eagle-import:C0603")
      (libsource (lib "eagle-import") (part "C_0603"))
    )
    (comp (ref "C99")
      (value "0.1µF")
      (footprint "eagle-import:C0603")
      (libsource (lib "eagle-import") (part "C_0603"))
    )
    (comp (ref "C100")
      (value "0.01µF")
      (footprint "eagle-import:C0603")
      (libsource (lib "eagle-import") (part "C_0603"))
    )
    (comp (ref "C101")
      (value "0.1µF")
      (footprint "eagle-import:C0603")
      (libsource (lib "eagle-import") (part "C_0603"))
    )
    (comp (ref "C103")
      (value "470µF")
      (footprint "eagle-import:CSV-G")
      (libsource (lib "eagle-import") (part "CP_SV-G"))
    )
    (comp (ref "C104")
      (value "0.01µF")
      (footprint "eagle-import:C0603")
      (libsource (lib "eagle-import") (part "C_0603"))
    )
    (comp (ref "C105")
      (value "0.1µF")
      (footprint "eagle-import:C0603")
      (libsource (lib "eagle-import") (part "C_0603"))
    )
    (comp (ref "D2")
      (value "DEL-1206")
      (footprint "eagle-import:DEL1206")
      (libsource (lib "eagle-import") (part "DEL-1206"))
    )
    (comp (ref "L1")
      (value "L_0805")
      (footprint "eagle-import:L0805")
      (libsource (lib "eagle-import") (part "L_0805"))
    )
    (comp (ref "L2")
      (value "L_0805")
      (footprint "eagle-import:L0805")
      (libsource (lib "eagle-import") (part "L_0805"))
    )
    (comp (ref "R12")
      (value "330R")
      (footprint "eagle-import:R1206")
      (libsource (lib "eagle-import") (part "R_1206"))
    )
    (comp (ref "X2")
      (value "5MM-3 BLOCK")
      (footprint "eagle-import:TERMINAL-BLOCK-3-PIN-5MM")
      (libsource (lib "eagle-import") (part "TERMINAL-BLOCK-5MM-3-PIN-LONG-PAD"))
    )
    (comp (ref "SRAM1")
      (value "CY7C1059DV33")
      (footprint "eagle-import:TSOPII-44")
      (libsource (lib "eagle-import") (part "CY7C1059DV33"))
    )
    (comp (ref "U1")
      (value "74ALVCH16827DL")
      (footprint "eagle-import:SSOP56(SOT371)")
      (libsource (lib "eagle-import") (part "74ALVCH16827DL"))
    )
    (comp (ref "U2")
      (value "74ALVCH16827DL")
      (footprint "eagle-import:SSOP56(SOT371)")
      (libsource (lib "eagle-import") (part "74ALVCH16827DL"))
    )
    (comp (ref "U8")
      (value "74LVC245A")
      (footprint "eagle-import:SO20DW(SOT163)")
      (libsource (lib "eagle-import") (part "74LVC245A"))
    )
    (comp (ref "U10")
      (value "74LVC245A")
      (footprint "eagle-import:SO20DW(SOT163)")
      (libsource (lib "eagle-import") (part "74LVC245A"))
    )
    (comp (ref "ADV7125")
      (value "ADV7125")
      (footprint "eagle-import:LQFP48(SOT313)")
      (libsource (lib "eagle-import") (part "ADV7125"))
    )
    (comp (ref "C1")
      (value "0.1µF")
      (footprint "eagle-import:C0603")
      (libsource (lib "eagle-import") (part "C_0603"))
    )
    (comp (ref "C91")
      (value "0.1µF")
      (footprint "eagle-import:C0603")
      (libsource (lib "eagle-import") (part "C_0603"))
    )
    (comp (ref "D1")
      (value "AD1580")
      (footprint "eagle-import:TO236-3(SOT23)")
      (fields (field (name "MPN") "AD1580BRTZ"))
      (libsource (lib "eagle-import") (part "AD1580"))
    )
    (comp (ref "J1")
      (value "VGA-DB15")
      (footprint "eagle-import:DB15-VGA-90DEG")
      (libsource (lib "eagle-import") (part "VGA-DB15"))
    )
    (comp (ref "R1")
      (value "560R")
      (footprint "eagle-import:R0603")
      (libsource (lib "eagle-import") (part "R_0603"))
    )
    (comp (ref "R2")
      (value "75R")
      (footprint "eagle-import:R0603")
      (libsource (lib "eagle-import") (part "R_0603"))
    )
    (comp (ref "R3")
      (value "75R")
      (footprint "eagle-import:R0603")
      (libsource (lib "eagle-import") (part "R_0603"))
    )
    (comp (ref "R4")
      (value "75R")
      (footprint "eagle-import:R0603")
      (libsource (lib "eagle-import") (part "R_0603"))
    )
    (comp (ref "R8")
      (value "1K")
      (footprint "eagle-import:R0603")
      (libsource (lib "eagle-import") (part "R_0603"))
    )
    (comp (ref "SRAM2")
      (value "CY7C1059DV33")
      (footprint "eagle-import:TSOPII-44")
      (libsource (lib "eagle-import") (part "CY7C1059DV33"))
    )
    (comp (ref "U3")
      (value "74ALVCH16827DL")
      (footprint "eagle-import:SSOP56(SOT371)")
      (libsource (lib "eagle-import") (part "74ALVCH16827DL"))
    )
    (comp (ref "U4")
      (value "74ALVCH16827DL")
      (footprint "eagle-import:SSOP56(SOT371)")
      (libsource (lib "eagle-import") (part "74ALVCH16827DL"))
    )
    (comp (ref "U9")
      (value "74LVC245A")
      (footprint "eagle-import:SO20DW(SOT163)")
      (libsource (lib "eagle-import") (part "74LVC245A"))
    )
    (comp (ref "U11")
      (value "74LVC245A")
      (footprint "eagle-import:SO20DW(SOT163)")
      (libsource (lib "eagle-import") (part "74LVC245A"))
    )
    (comp (ref "H1")
      (value "3MM_SCREW")
      (footprint "eagle-import:3MM_HOLE")
      (libsource (lib "eagle-import") (part "SCREW_MOUNT_HOLE3.0"))
    )
    (comp (ref "H2")
      (value "3MM_SCREW")
      (footprint "eagle-import:3MM_HOLE")
      (libsource (lib "eagle-import") (part "SCREW_MOUNT_HOLE3.0"))
    )
    (comp (ref "H3")
      (value "3MM_SCREW")
      (footprint "eagle-import:3MM_HOLE")
      (libsource (lib "eagle-import") (part "SCREW_MOUNT_HOLE3.0"))
    )
    (comp (ref "H4")
      (value "3MM_SCREW")
      (footprint "eagle-import:3MM_HOLE")
      (libsource (lib "eagle-import") (part "SCREW_MOUNT_HOLE3.0"))
    )
  )
  (nets
    (net (code "1") (name "+3V3") (class "Default")
      (node (ref "C10") (pin "2") (pinfunction "2_2") (pintype "passive"))
      (node (ref "C100") (pin "2") (pinfunction "2_2") (pintype "passive"))
      (node (ref "C101") (pin "2") (pinfunction "2_2") (pintype "passive"))
      (node (ref "C103") (pin "+") (pinfunction "+_+") (pintype "passive"))
      (node (ref "C104") (pin "2") (pinfunction "2_2") (pintype "passive"))
      (node (ref "C105") (pin "2") (pinfunction "2_2") (pintype "passive"))
      (node (ref "C11") (pin "2") (pinfunction "2_2") (pintype "passive"))
      (node (ref "C12") (pin "2") (pinfunction "2_2") (pintype "passive"))
      (node (ref "C13") (pin "2") (pinfunction "2_2") (pintype "passive"))
      (node (ref "C14") (pin "2") (pinfunction "2_2") (pintype "passive"))
      (node (ref "C15") (pin "2") (pinfunction "2_2") (pintype "passive"))
      (node (ref "C16") (pin "2") (pinfunction "2_2") (pintype "passive"))
      (node (ref "C17") (pin "2") (pinfunction "2_2") (pintype "passive"))
      (node (ref "C18") (pin "2") (pinfunction "2_2") (pintype "passive"))
      (node (ref "C19") (pin "2") (pinfunction "2_2") (pintype "passive"))
      (node (ref "C2") (pin "2") (pinfunction "2_2") (pintype "passive"))
      (node (ref "C20") (pin "2") (pinfunction "2_2") (pintype "passive"))
      (node (ref "C21") (pin "2") (pinfunction "2_2") (pintype "passive"))
      (node (ref "C22") (pin "2") (pinfunction "2_2") (pintype "passive"))
      (node (ref "C23") (pin "2") (pinfunction "2_2") (pintype "passive"))
      (node (ref "C24") (pin "2") (pinfunction "2_2") (pintype "passive"))
      (node (ref "C25") (pin "2") (pinfunction "2_2") (pintype "passive"))
      (node (ref "C26") (pin "2") (pinfunction "2_2") (pintype "passive"))
      (node (ref "C27") (pin "2") (pinfunction "2_2") (pintype "passive"))
      (node (ref "C28") (pin "2") (pinfunction "2_2") (pintype "passive"))
      (node (ref "C29") (pin "2") (pinfunction "2_2") (pintype "passive"))
      (node (ref "C3") (pin "2") (pinfunction "2_2") (pintype "passive"))
      (node (ref "C30") (pin "2") (pinfunction "2_2") (pintype "passive"))
      (node (ref "C31") (pin "2") (pinfunction "2_2") (pintype "passive"))
      (node (ref "C32") (pin "2") (pinfunction "2_2") (pintype "passive"))
      (node (ref "C33") (pin "2") (pinfunction "2_2") (pintype "passive"))
      (node (ref "C34") (pin "2") (pinfunction "2_2") (pintype "passive"))
      (node (ref "C35") (pin "2") (pinfunction "2_2") (pintype "passive"))
      (node (ref "C36") (pin "2") (pinfunction "2_2") (pintype "passive"))
      (node (ref "C37") (pin "2") (pinfunction "2_2") (pintype "passive"))
      (node (ref "C38") (pin "2") (pinfunction "2_2") (pintype "passive"))
      (node (ref "C39") (pin "2") (pinfunction "2_2") (pintype "passive"))
      (node (ref "C4") (pin "2") (pinfunction "2_2") (pintype "passive"))
      (node (ref "C40") (pin "2") (pinfunction "2_2") (pintype "passive"))
      (node (ref "C41") (pin "2") (pinfunction "2_2") (pintype "passive"))
      (node (ref "C42") (pin "2") (pinfunction "2_2") (pintype "passive"))
      (node (ref "C43") (pin "2") (pinfunction "2_2") (pintype "passive"))
      (node (ref "C44") (pin "2") (pinfunction "2_2") (pintype "passive"))
      (node (ref "C45") (pin "2") (pinfunction "2_2") (pintype "passive"))
      (node (ref "C46") (pin "2") (pinfunction "2_2") (pintype "passive"))
      (node (ref "C47") (pin "2") (pinfunction "2_2") (pintype "passive"))
      (node (ref "C48") (pin "2") (pinfunction "2_2") (pintype "passive"))
      (node (ref "C49") (pin "2") (pinfunction "2_2") (pintype "passive"))
      (node (ref "C5") (pin "2") (pinfunction "2_2") (pintype "passive"))
      (node (ref "C50") (pin "2") (pinfunction "2_2") (pintype "passive"))
      (node (ref "C51") (pin "2") (pinfunction "2_2") (pintype "passive"))
      (node (ref "C52") (pin "2") (pinfunction "2_2") (pintype "passive"))
      (node (ref "C53") (pin "2") (pinfunction "2_2") (pintype "passive"))
      (node (ref "C54") (pin "2") (pinfunction "2_2") (pintype "passive"))
      (node (ref "C55") (pin "2") (pinfunction "2_2") (pintype "passive"))
      (node (ref "C56") (pin "2") (pinfunction "2_2") (pintype "passive"))
      (node (ref "C57") (pin "2") (pinfunction "2_2") (pintype "passive"))
      (node (ref "C58") (pin "2") (pinfunction "2_2") (pintype "passive"))
      (node (ref "C59") (pin "2") (pinfunction "2_2") (pintype "passive"))
      (node (ref "C6") (pin "2") (pinfunction "2_2") (pintype "passive"))
      (node (ref "C60") (pin "2") (pinfunction "2_2") (pintype "passive"))
      (node (ref "C61") (pin "2") (pinfunction "2_2") (pintype "passive"))
      (node (ref "C62") (pin "2") (pinfunction "2_2") (pintype "passive"))
      (node (ref "C63") (pin "2") (pinfunction "2_2") (pintype "passive"))
      (node (ref "C64") (pin "2") (pinfunction "2_2") (pintype "passive"))
      (node (ref "C65") (pin "2") (pinfunction "2_2") (pintype "passive"))
      (node (ref "C66") (pin "2") (pinfunction "2_2") (pintype "passive"))
      (node (ref "C67") (pin "2") (pinfunction "2_2") (pintype "passive"))
      (node (ref "C68") (pin "2") (pinfunction "2_2") (pintype "passive"))
      (node (ref "C69") (pin "2") (pinfunction "2_2") (pintype "passive"))
      (node (ref "C7") (pin "2") (pinfunction "2_2") (pintype "passive"))
      (node (ref "C70") (pin "2") (pinfunction "2_2") (pintype "passive"))
      (node (ref "C71") (pin "2") (pinfunction "2_2") (pintype "passive"))
      (node (ref "C72") (pin "2") (pinfunction "2_2") (pintype "passive"))
      (node (ref "C73") (pin "2") (pinfunction "2_2") (pintype "passive"))
      (node (ref "C74") (pin "2") (pinfunction "2_2") (pintype "passive"))
      (node (ref "C75") (pin "2") (pinfunction "2_2") (pintype "passive"))
      (node (ref "C76") (pin "2") (pinfunction "2_2") (pintype "passive"))
      (node (ref "C77") (pin "2") (pinfunction "2_2") (pintype "passive"))
      (node (ref "C78") (pin "2") (pinfunction "2_2") (pintype "passive"))
      (node (ref "C79") (pin "2") (pinfunction "2_2") (pintype "passive"))
      (node (ref "C8") (pin "2") (pinfunction "2_2") (pintype "passive"))
      (node (ref "C80") (pin "2") (pinfunction "2_2") (pintype "passive"))
      (node (ref "C81") (pin "2") (pinfunction "2_2") (pintype "passive"))
      (node (ref "C9") (pin "2") (pinfunction "2_2") (pintype "passive"))
      (node (ref "C92") (pin "2") (pinfunction "2_2") (pintype "passive"))
      (node (ref "C93") (pin "2") (pinfunction "2_2") (pintype "passive"))
      (node (ref "C94") (pin "2") (pinfunction "2_2") (pintype "passive"))
      (node (ref "C95") (pin "2") (pinfunction "2_2") (pintype "passive"))
      (node (ref "C96") (pin "2") (pinfunction "2_2") (pintype "passive"))
      (node (ref "C97") (pin "2") (pinfunction "2_2") (pintype "passive"))
      (node (ref "C98") (pin "2") (pinfunction "2_2") (pintype "passive"))
      (node (ref "C99") (pin "2") (pinfunction "2_2") (pintype "passive"))
      (node (ref "D2") (pin "A") (pinfunction "A_A") (pintype "passive"))
      (node (ref "L1") (pin "2") (pinfunction "2_2") (pintype "passive"))
      (node (ref "LPC1769") (pin "28") (pinfunction "28_28") (pintype "passive"))
      (node (ref "SRAM1") (pin "11") (pinfunction "+3V3_11") (pintype "power_in"))
      (node (ref "SRAM1") (pin "33") (pinfunction "+3V3_33") (pintype "power_in"))
      (node (ref "SRAM2") (pin "11") (pinfunction "+3V3_11") (pintype "power_in"))
      (node (ref "SRAM2") (pin "33") (pinfunction "+3V3_33") (pintype "power_in"))
      (node (ref "U1") (pin "22") (pinfunction "+3V3_22") (pintype "power_in"))
      (node (ref "U1") (pin "35") (pinfunction "+3V3_35") (pintype "power_in"))
      (node (ref "U1") (pin "50") (pinfunction "+3V3_50") (pintype "power_in"))
      (node (ref "U1") (pin "7") (pinfunction "+3V3_7") (pintype "power_in"))
      (node (ref "U10") (pin "1") (pinfunction "DIR_1") (pintype "input"))
      (node (ref "U11") (pin "1") (pinfunction "DIR_1") (pintype "input"))
      (node (ref "U12") (pin "9") (pinfunction "PE_9") (pintype "input"))
      (node (ref "U14") (pin "9") (pinfunction "PE_9") (pintype "input"))
      (node (ref "U15") (pin "9") (pinfunction "PE_9") (pintype "input"))
      (node (ref "U16") (pin "9") (pinfunction "PE_9") (pintype "input"))
      (node (ref "U17") (pin "9") (pinfunction "PE_9") (pintype "input"))
      (node (ref "U18") (pin "9") (pinfunction "PE_9") (pintype "input"))
      (node (ref "U19") (pin "10") (pinfunction "CET_10") (pintype "input"))
      (node (ref "U19") (pin "7") (pinfunction "CEP_7") (pintype "input"))
      (node (ref "U19") (pin "9") (pinfunction "PE_9") (pintype "input"))
      (node (ref "U2") (pin "22") (pinfunction "+3V3_22") (pintype "power_in"))
      (node (ref "U2") (pin "35") (pinfunction "+3V3_35") (pintype "power_in"))
      (node (ref "U2") (pin "50") (pinfunction "+3V3_50") (pintype "power_in"))
      (node (ref "U2") (pin "7") (pinfunction "+3V3_7") (pintype "power_in"))
      (node (ref "U20") (pin "9") (pinfunction "PE_9") (pintype "input"))
      (node (ref "U21") (pin "9") (pinfunction "PE_9") (pintype "input"))
      (node (ref "U26") (pin "8") (pinfunction "OE_8") (pintype "input"))
      (node (ref "U28") (pin "1") (pinfunction "CLR_1") (pintype "input"))
      (node (ref "U28") (pin "10") (pinfunction "PRE_10") (pintype "input"))
      (node (ref "U28") (pin "11") (pinfunction "CLK_11") (pintype "input"))
      (node (ref "U28") (pin "12") (pinfunction "D_12") (pintype "input"))
      (node (ref "U28") (pin "13") (pinfunction "CLR_13") (pintype "input"))
      (node (ref "U28") (pin "4") (pinfunction "PRE_4") (pintype "input"))
      (node (ref "U29") (pin "1") (pinfunction "CLR_1") (pintype "input"))
      (node (ref "U29") (pin "11") (pinfunction "PRE_11") (pintype "input"))
      (node (ref "U29") (pin "15") (pinfunction "CLR_15") (pintype "input"))
      (node (ref "U29") (pin "5") (pinfunction "PRE_5") (pintype "input"))
      (node (ref "U3") (pin "22") (pinfunction "+3V3_22") (pintype "power_in"))
      (node (ref "U3") (pin "35") (pinfunction "+3V3_35") (pintype "power_in"))
      (node (ref "U3") (pin "50") (pinfunction "+3V3_50") (pintype "power_in"))
      (node (ref "U3") (pin "7") (pinfunction "+3V3_7") (pintype "power_in"))
      (node (ref "U30") (pin "1") (pinfunction "CLR_1") (pintype "input"))
      (node (ref "U30") (pin "11") (pinfunction "PRE_11") (pintype "input"))
      (node (ref "U30") (pin "15") (pinfunction "CLR_15") (pintype "input"))
      (node (ref "U30") (pin "5") (pinfunction "PRE_5") (pintype "input"))
      (node (ref "U4") (pin "22") (pinfunction "+3V3_22") (pintype "power_in"))
      (node (ref "U4") (pin "35") (pinfunction "+3V3_35") (pintype "power_in"))
      (node (ref "U4") (pin "50") (pinfunction "+3V3_50") (pintype "power_in"))
      (node (ref "U4") (pin "7") (pinfunction "+3V3_7") (pintype "power_in"))
      (node (ref "U5") (pin "10") (pinfunction "CET_10") (pintype "input"))
      (node (ref "U5") (pin "7") (pinfunction "CEP_7") (pintype "input"))
      (node (ref "U5") (pin "9") (pinfunction "PE_9") (pintype "input"))
      (node (ref "U6") (pin "10") (pinfunction "CET_10") (pintype "input"))
      (node (ref "U6") (pin "7") (pinfunction "CEP_7") (pintype "input"))
      (node (ref "U6") (pin "9") (pinfunction "PE_9") (pintype "input"))
      (node (ref "U7") (pin "10") (pinfunction "PRE_10") (pintype "input"))
      (node (ref "U7") (pin "11") (pinfunction "J_11") (pintype "input"))
      (node (ref "U7") (pin "12") (pinfunction "K_12") (pintype "input"))
      (node (ref "U7") (pin "13") (pinfunction "CLK_13") (pintype "input"))
      (node (ref "U7") (pin "14") (pinfunction "CLR_14") (pintype "input"))
      (node (ref "U7") (pin "15") (pinfunction "CLR_15") (pintype "input"))
      (node (ref "U7") (pin "2") (pinfunction "K_2") (pintype "input"))
      (node (ref "U8") (pin "1") (pinfunction "DIR_1") (pintype "input"))
      (node (ref "U9") (pin "1") (pinfunction "DIR_1") (pintype "input"))
      (node (ref "X1") (pin "4") (pinfunction "+3V3_4") (pintype "power_in"))
      (node (ref "X2") (pin "2") (pinfunction "K_2") (pintype "passive"))
    )
    (net (code "2") (name "+3VA") (class "Default")
      (node (ref "ADV7125") (pin "12") (pinfunction "~{SYNC}_12") (pintype "input"))
      (node (ref "ADV7125") (pin "13") (pinfunction "VAA_13") (pintype "power_in"))
      (node (ref "ADV7125") (pin "29") (pinfunction "VAA_29") (pintype "power_in"))
      (node (ref "ADV7125") (pin "30") (pinfunction "VAA_30") (pintype "power_in"))
      (node (ref "ADV7125") (pin "38") (pinfunction "~{PSAVE}_38") (pintype "input"))
      (node (ref "C1") (pin "2") (pinfunction "2_2") (pintype "passive"))
      (node (ref "C82") (pin "2") (pinfunction "2_2") (pintype "passive"))
      (node (ref "C83") (pin "2") (pinfunction "2_2") (pintype "passive"))
      (node (ref "C84") (pin "2") (pinfunction "2_2") (pintype "passive"))
      (node (ref "C85") (pin "2") (pinfunction "2_2") (pintype "passive"))
      (node (ref "C86") (pin "2") (pinfunction "2_2") (pintype "passive"))
      (node (ref "C87") (pin "2") (pinfunction "2_2") (pintype "passive"))
      (node (ref "L1") (pin "1") (pinfunction "1_1") (pintype "passive"))
      (node (ref "R8") (pin "2") (pinfunction "2_2") (pintype "passive"))
    )
    (net (code "15") (name "40MHZ_CLK") (class "Default")
      (node (ref "U26") (pin "1") (pinfunction "ICLK_1") (pintype "input"))
      (node (ref "X1") (pin "3") (pinfunction "OUT_3") (pintype "output"))
    )
    (net (code "16") (name "AGND") (class "Default")
      (node (ref "ADV7125") (pin "1") (pinfunction "GND_1") (pintype "passive"))
      (node (ref "ADV7125") (pin "14") (pinfunction "GND_14") (pintype "passive"))
      (node (ref "ADV7125") (pin "15") (pinfunction "GND_15") (pintype "passive"))
      (node (ref "ADV7125") (pin "2") (pinfunction "GND_2") (pintype "passive"))
      (node (ref "ADV7125") (pin "25") (pinfunction "GND_25") (pintype "passive"))
      (node (ref "ADV7125") (pin "26") (pinfunction "GND_26") (pintype "passive"))
      (node (ref "ADV7125") (pin "27") (pinfunction "~{IOB}_27") (pintype "output"))
      (node (ref "ADV7125") (pin "31") (pinfunction "~{IOG}_31") (pintype "output"))
      (node (ref "ADV7125") (pin "33") (pinfunction "~{IOR}_33") (pintype "output"))
      (node (ref "ADV7125") (pin "39") (pinfunction "GND_39") (pintype "passive"))
      (node (ref "ADV7125") (pin "40") (pinfunction "GND_40") (pintype "passive"))
      (node (ref "C82") (pin "1") (pinfunction "1_1") (pintype "passive"))
      (node (ref "C83") (pin "1") (pinfunction "1_1") (pintype "passive"))
      (node (ref "C84") (pin "1") (pinfunction "1_1") (pintype "passive"))
      (node (ref "C85") (pin "1") (pinfunction "1_1") (pintype "passive"))
      (node (ref "C86") (pin "1") (pinfunction "1_1") (pintype "passive"))
      (node (ref "C87") (pin "1") (pinfunction "1_1") (pintype "passive"))
      (node (ref "C91") (pin "1") (pinfunction "1_1") (pintype "passive"))
      (node (ref "D1") (pin "2") (pinfunction "V-_2") (pintype "passive"))
      (node (ref "J1") (pin "5") (pinfunction "GND_5") (pintype "passive"))
      (node (ref "J1") (pin "6") (pinfunction "RGND_6") (pintype "passive"))
      (node (ref "J1") (pin "7") (pinfunction "GGND_7") (pintype "passive"))
      (node (ref "J1") (pin "8") (pinfunction "BGND_8") (pintype "passive"))
      (node (ref "L2") (pin "2") (pinfunction "2_2") (pintype "passive"))
      (node (ref "R1") (pin "1") (pinfunction "1_1") (pintype "passive"))
      (node (ref "R2") (pin "1") (pinfunction "1_1") (pintype "passive"))
      (node (ref "R3") (pin "1") (pinfunction "1_1") (pintype "passive"))
      (node (ref "R4") (pin "1") (pinfunction "1_1") (pintype "passive"))
    )
    (net (code "17") (name "A_IN0") (class "Default")
      (node (ref "U1") (pin "30") (pinfunction "2A10_30") (pintype "input"))
      (node (ref "U23") (pin "15") (pinfunction "Q0_15") (pintype "output"))
      (node (ref "U3") (pin "55") (pinfunction "1A1_55") (pintype "input"))
    )
    (net (code "18") (name "A_IN1") (class "Default")
      (node (ref "U1") (pin "31") (pinfunction "2A9_31") (pintype "input"))
      (node (ref "U23") (pin "1") (pinfunction "Q1_1") (pintype "output"))
      (node (ref "U3") (pin "54") (pinfunction "1A2_54") (pintype "input"))
    )
    (net (code "19") (name "A_IN2") (class "Default")
      (node (ref "U1") (pin "33") (pinfunction "2A8_33") (pintype "input"))
      (node (ref "U23") (pin "2") (pinfunction "Q2_2") (pintype "output"))
      (node (ref "U3") (pin "52") (pinfunction "1A3_52") (pintype "input"))
    )
    (net (code "20") (name "A_IN3") (class "Default")
      (node (ref "U1") (pin "34") (pinfunction "2A7_34") (pintype "input"))
      (node (ref "U23") (pin "3") (pinfunction "Q3_3") (pintype "output"))
      (node (ref "U3") (pin "51") (pinfunction "1A4_51") (pintype "input"))
    )
    (net (code "21") (name "A_IN4") (class "Default")
      (node (ref "U1") (pin "36") (pinfunction "2A6_36") (pintype "input"))
      (node (ref "U23") (pin "4") (pinfunction "Q4_4") (pintype "output"))
      (node (ref "U3") (pin "49") (pinfunction "1A5_49") (pintype "input"))
    )
    (net (code "22") (name "A_IN5") (class "Default")
      (node (ref "U1") (pin "37") (pinfunction "2A5_37") (pintype "input"))
      (node (ref "U23") (pin "5") (pinfunction "Q5_5") (pintype "output"))
      (node (ref "U3") (pin "48") (pinfunction "1A6_48") (pintype "input"))
    )
    (net (code "23") (name "A_IN6") (class "Default")
      (node (ref "U1") (pin "38") (pinfunction "2A4_38") (pintype "input"))
      (node (ref "U23") (pin "6") (pinfunction "Q6_6") (pintype "output"))
      (node (ref "U3") (pin "47") (pinfunction "1A7_47") (pintype "input"))
    )
    (net (code "24") (name "A_IN7") (class "Default")
      (node (ref "U1") (pin "40") (pinfunction "2A3_40") (pintype "input"))
      (node (ref "U23") (pin "7") (pinfunction "Q7_7") (pintype "output"))
      (node (ref "U3") (pin "45") (pinfunction "1A8_45") (pintype "input"))
    )
    (net (code "25") (name "A_IN8") (class "Default")
      (node (ref "U1") (pin "41") (pinfunction "2A2_41") (pintype "input"))
      (node (ref "U24") (pin "15") (pinfunction "Q0_15") (pintype "output"))
      (node (ref "U3") (pin "44") (pinfunction "1A9_44") (pintype "input"))
    )
    (net (code "26") (name "A_IN9") (class "Default")
      (node (ref "U1") (pin "42") (pinfunction "2A1_42") (pintype "input"))
      (node (ref "U24") (pin "1") (pinfunction "Q1_1") (pintype "output"))
      (node (ref "U3") (pin "43") (pinfunction "1A10_43") (pintype "input"))
    )
    (net (code "27") (name "A_IN10") (class "Default")
      (node (ref "U1") (pin "43") (pinfunction "1A10_43") (pintype "input"))
      (node (ref "U24") (pin "2") (pinfunction "Q2_2") (pintype "output"))
      (node (ref "U3") (pin "42") (pinfunction "2A1_42") (pintype "input"))
    )
    (net (code "28") (name "A_IN11") (class "Default")
      (node (ref "U1") (pin "44") (pinfunction "1A9_44") (pintype "input"))
      (node (ref "U24") (pin "3") (pinfunction "Q3_3") (pintype "output"))
      (node (ref "U3") (pin "41") (pinfunction "2A2_41") (pintype "input"))
    )
    (net (code "29") (name "A_IN12") (class "Default")
      (node (ref "U1") (pin "45") (pinfunction "1A8_45") (pintype "input"))
      (node (ref "U24") (pin "4") (pinfunction "Q4_4") (pintype "output"))
      (node (ref "U3") (pin "40") (pinfunction "2A3_40") (pintype "input"))
    )
    (net (code "30") (name "A_IN13") (class "Default")
      (node (ref "U1") (pin "47") (pinfunction "1A7_47") (pintype "input"))
      (node (ref "U24") (pin "5") (pinfunction "Q5_5") (pintype "output"))
      (node (ref "U3") (pin "38") (pinfunction "2A4_38") (pintype "input"))
    )
    (net (code "31") (name "A_IN14") (class "Default")
      (node (ref "U1") (pin "48") (pinfunction "1A6_48") (pintype "input"))
      (node (ref "U24") (pin "6") (pinfunction "Q6_6") (pintype "output"))
      (node (ref "U3") (pin "37") (pinfunction "2A5_37") (pintype "input"))
    )
    (net (code "32") (name "A_IN15") (class "Default")
      (node (ref "U1") (pin "49") (pinfunction "1A5_49") (pintype "input"))
      (node (ref "U24") (pin "7") (pinfunction "Q7_7") (pintype "output"))
      (node (ref "U3") (pin "36") (pinfunction "2A6_36") (pintype "input"))
    )
    (net (code "33") (name "A_IN16") (class "Default")
      (node (ref "U1") (pin "51") (pinfunction "1A4_51") (pintype "input"))
      (node (ref "U25") (pin "15") (pinfunction "Q0_15") (pintype "output"))
      (node (ref "U3") (pin "34") (pinfunction "2A7_34") (pintype "input"))
    )
    (net (code "34") (name "A_IN17") (class "Default")
      (node (ref "U1") (pin "52") (pinfunction "1A3_52") (pintype "input"))
      (node (ref "U25") (pin "1") (pinfunction "Q1_1") (pintype "output"))
      (node (ref "U3") (pin "33") (pinfunction "2A8_33") (pintype "input"))
    )
    (net (code "35") (name "A_IN18") (class "Default")
      (node (ref "U1") (pin "54") (pinfunction "1A2_54") (pintype "input"))
      (node (ref "U25") (pin "2") (pinfunction "Q2_2") (pintype "output"))
      (node (ref "U3") (pin "31") (pinfunction "2A9_31") (pintype "input"))
    )
    (net (code "36") (name "A_IN19") (class "Default")
      (node (ref "U1") (pin "55") (pinfunction "1A1_55") (pintype "input"))
      (node (ref "U25") (pin "3") (pinfunction "Q3_3") (pintype "output"))
      (node (ref "U3") (pin "30") (pinfunction "2A10_30") (pintype "input"))
    )
    (net (code "37") (name "B0") (class "Default")
      (node (ref "ADV7125") (pin "16") (pinfunction "B0_16") (pintype "input"))
      (node (ref "ADV7125") (pin "18") (pinfunction "B2_18") (pintype "input"))
      (node (ref "ADV7125") (pin "20") (pinfunction "B4_20") (pintype "input"))
      (node (ref "ADV7125") (pin "22") (pinfunction "B6_22") (pintype "input"))
      (node (ref "U10") (pin "11") (pinfunction "B8_11") (pintype "output"))
      (node (ref "U11") (pin "18") (pinfunction "B1_18") (pintype "output"))
    )
    (net (code "38") (name "B1") (class "Default")
      (node (ref "ADV7125") (pin "17") (pinfunction "B1_17") (pintype "input"))
      (node (ref "ADV7125") (pin "19") (pinfunction "B3_19") (pintype "input"))
      (node (ref "ADV7125") (pin "21") (pinfunction "B5_21") (pintype "input"))
      (node (ref "ADV7125") (pin "23") (pinfunction "B7_23") (pintype "input"))
      (node (ref "U10") (pin "12") (pinfunction "B7_12") (pintype "output"))
      (node (ref "U11") (pin "17") (pinfunction "B2_17") (pintype "output"))
    )
    (net (code "39") (name "CCLK0") (class "Default")
      (node (ref "R9") (pin "2") (pinfunction "2_2") (pintype "passive"))
      (node (ref "U17") (pin "2") (pinfunction "CLK_2") (pintype "input"))
      (node (ref "U18") (pin "2") (pinfunction "CLK_2") (pintype "input"))
      (node (ref "U26") (pin "2") (pinfunction "Q1_2") (pintype "output"))
      (node (ref "U6") (pin "2") (pinfunction "CLK_2") (pintype "input"))
    )
    (net (code "40") (name "CCLK1") (class "Default")
      (node (ref "ADV7125") (pin "24") (pinfunction "CLOCK_24") (pintype "input"))
      (node (ref "R11") (pin "2") (pinfunction "2_2") (pintype "passive"))
      (node (ref "U26") (pin "3") (pinfunction "Q2_3") (pintype "output"))
    )
    (net (code "41") (name "CCLK2") (class "Default")
      (node (ref "R5") (pin "2") (pinfunction "2_2") (pintype "passive"))
      (node (ref "U12") (pin "2") (pinfunction "CLK_2") (pintype "input"))
      (node (ref "U14") (pin "2") (pinfunction "CLK_2") (pintype "input"))
      (node (ref "U15") (pin "2") (pinfunction "CLK_2") (pintype "input"))
      (node (ref "U16") (pin "2") (pinfunction "CLK_2") (pintype "input"))
      (node (ref "U26") (pin "4") (pinfunction "Q3_4") (pintype "output"))
      (node (ref "U5") (pin "2") (pinfunction "CLK_2") (pintype "input"))
    )
    (net (code "42") (name "CCLK3") (class "Default")
      (node (ref "U26") (pin "5") (pinfunction "Q4_5") (pintype "output"))
      (node (ref "U29") (pin "12") (pinfunction "CLK_12") (pintype "input"))
      (node (ref "U29") (pin "4") (pinfunction "CLK_4") (pintype "input"))
      (node (ref "U30") (pin "12") (pinfunction "CLK_12") (pintype "input"))
      (node (ref "U30") (pin "4") (pinfunction "CLK_4") (pintype "input"))
    )
    (net (code "43") (name "CS") (class "Default")
      (node (ref "LPC1769") (pin "14") (pinfunction "14_14") (pintype "passive"))
      (node (ref "U28") (pin "2") (pinfunction "D_2") (pintype "input"))
    )
    (net (code "44") (name "D_IN0") (class "Default")
      (node (ref "U22") (pin "15") (pinfunction "Q0_15") (pintype "output"))
      (node (ref "U8") (pin "9") (pinfunction "A8_9") (pintype "input"))
      (node (ref "U9") (pin "2") (pinfunction "A1_2") (pintype "input"))
    )
    (net (code "45") (name "D_IN1") (class "Default")
      (node (ref "U22") (pin "1") (pinfunction "Q1_1") (pintype "output"))
      (node (ref "U8") (pin "8") (pinfunction "A7_8") (pintype "input"))
      (node (ref "U9") (pin "3") (pinfunction "A2_3") (pintype "input"))
    )
    (net (code "46") (name "D_IN2") (class "Default")
      (node (ref "U22") (pin "2") (pinfunction "Q2_2") (pintype "output"))
      (node (ref "U8") (pin "7") (pinfunction "A6_7") (pintype "input"))
      (node (ref "U9") (pin "4") (pinfunction "A3_4") (pintype "input"))
    )
    (net (code "47") (name "D_IN3") (class "Default")
      (node (ref "U22") (pin "3") (pinfunction "Q3_3") (pintype "output"))
      (node (ref "U8") (pin "6") (pinfunction "A5_6") (pintype "input"))
      (node (ref "U9") (pin "5") (pinfunction "A4_5") (pintype "input"))
    )
    (net (code "48") (name "D_IN4") (class "Default")
      (node (ref "U22") (pin "4") (pinfunction "Q4_4") (pintype "output"))
      (node (ref "U8") (pin "5") (pinfunction "A4_5") (pintype "input"))
      (node (ref "U9") (pin "6") (pinfunction "A5_6") (pintype "input"))
    )
    (net (code "49") (name "D_IN5") (class "Default")
      (node (ref "U22") (pin "5") (pinfunction "Q5_5") (pintype "output"))
      (node (ref "U8") (pin "4") (pinfunction "A3_4") (pintype "input"))
      (node (ref "U9") (pin "7") (pinfunction "A6_7") (pintype "input"))
    )
    (net (code "50") (name "D_IN6") (class "Default")
      (node (ref "U22") (pin "6") (pinfunction "Q6_6") (pintype "output"))
      (node (ref "U8") (pin "3") (pinfunction "A2_3") (pintype "input"))
      (node (ref "U9") (pin "8") (pinfunction "A7_8") (pintype "input"))
    )
    (net (code "51") (name "D_IN7") (class "Default")
      (node (ref "U22") (pin "7") (pinfunction "Q7_7") (pintype "output"))
      (node (ref "U8") (pin "2") (pinfunction "A1_2") (pintype "input"))
      (node (ref "U9") (pin "9") (pinfunction "A8_9") (pintype "input"))
    )
    (net (code "52") (name "D_READY") (class "Default")
      (node (ref "U22") (pin "12") (pinfunction "STCP_12") (pintype "input"))
      (node (ref "U23") (pin "12") (pinfunction "STCP_12") (pintype "input"))
      (node (ref "U24") (pin "12") (pinfunction "STCP_12") (pintype "input"))
      (node (ref "U25") (pin "12") (pinfunction "STCP_12") (pintype "input"))
      (node (ref "U25") (pin "9") (pinfunction "Q7S_9") (pintype "output"))
      (node (ref "U32") (pin "2") (pinfunction "B_2") (pintype "input"))
    )
    (net (code "53") (name "G0") (class "Default")
      (node (ref "ADV7125") (pin "5") (pinfunction "G2_5") (pintype "input"))
      (node (ref "ADV7125") (pin "8") (pinfunction "G5_8") (pintype "input"))
      (node (ref "U10") (pin "13") (pinfunction "B6_13") (pintype "output"))
      (node (ref "U11") (pin "16") (pinfunction "B3_16") (pintype "output"))
    )
    (net (code "54") (name "G1") (class "Default")
      (node (ref "ADV7125") (pin "3") (pinfunction "G0_3") (pintype "input"))
      (node (ref "ADV7125") (pin "6") (pinfunction "G3_6") (pintype "input"))
      (node (ref "ADV7125") (pin "9") (pinfunction "G6_9") (pintype "input"))
      (node (ref "U10") (pin "14") (pinfunction "B5_14") (pintype "output"))
      (node (ref "U11") (pin "15") (pinfunction "B4_15") (pintype "output"))
    )
    (net (code "55") (name "G2") (class "Default")
      (node (ref "ADV7125") (pin "10") (pinfunction "G7_10") (pintype "input"))
      (node (ref "ADV7125") (pin "4") (pinfunction "G1_4") (pintype "input"))
      (node (ref "ADV7125") (pin "7") (pinfunction "G4_7") (pintype "input"))
      (node (ref "U10") (pin "15") (pinfunction "B4_15") (pintype "output"))
      (node (ref "U11") (pin "14") (pinfunction "B5_14") (pintype "output"))
    )
    (net (code "56") (name "GND") (class "Default")
      (node (ref "C10") (pin "1") (pinfunction "1_1") (pintype "passive"))
      (node (ref "C100") (pin "1") (pinfunction "1_1") (pintype "passive"))
      (node (ref "C101") (pin "1") (pinfunction "1_1") (pintype "passive"))
      (node (ref "C102") (pin "1") (pinfunction "1_1") (pintype "passive"))
      (node (ref "C103") (pin "-") (pinfunction "-_-") (pintype "passive"))
      (node (ref "C104") (pin "1") (pinfunction "1_1") (pintype "passive"))
      (node (ref "C105") (pin "1") (pinfunction "1_1") (pintype "passive"))
      (node (ref "C11") (pin "1") (pinfunction "1_1") (pintype "passive"))
      (node (ref "C12") (pin "1") (pinfunction "1_1") (pintype "passive"))
      (node (ref "C13") (pin "1") (pinfunction "1_1") (pintype "passive"))
      (node (ref "C14") (pin "1") (pinfunction "1_1") (pintype "passive"))
      (node (ref "C15") (pin "1") (pinfunction "1_1") (pintype "passive"))
      (node (ref "C16") (pin "1") (pinfunction "1_1") (pintype "passive"))
      (node (ref "C17") (pin "1") (pinfunction "1_1") (pintype "passive"))
      (node (ref "C18") (pin "1") (pinfunction "1_1") (pintype "passive"))
      (node (ref "C19") (pin "1") (pinfunction "1_1") (pintype "passive"))
      (node (ref "C2") (pin "1") (pinfunction "1_1") (pintype "passive"))
      (node (ref "C20") (pin "1") (pinfunction "1_1") (pintype "passive"))
      (node (ref "C21") (pin "1") (pinfunction "1_1") (pintype "passive"))
      (node (ref "C22") (pin "1") (pinfunction "1_1") (pintype "passive"))
      (node (ref "C23") (pin "1") (pinfunction "1_1") (pintype "passive"))
      (node (ref "C24") (pin "1") (pinfunction "1_1") (pintype "passive"))
      (node (ref "C25") (pin "1") (pinfunction "1_1") (pintype "passive"))
      (node (ref "C26") (pin "1") (pinfunction "1_1") (pintype "passive"))
      (node (ref "C27") (pin "1") (pinfunction "1_1") (pintype "passive"))
      (node (ref "C28") (pin "1") (pinfunction "1_1") (pintype "passive"))
      (node (ref "C29") (pin "1") (pinfunction "1_1") (pintype "passive"))
      (node (ref "C3") (pin "1") (pinfunction "1_1") (pintype "passive"))
      (node (ref "C30") (pin "1") (pinfunction "1_1") (pintype "passive"))
      (node (ref "C31") (pin "1") (pinfunction "1_1") (pintype "passive"))
      (node (ref "C32") (pin "1") (pinfunction "1_1") (pintype "passive"))
      (node (ref "C33") (pin "1") (pinfunction "1_1") (pintype "passive"))
      (node (ref "C34") (pin "1") (pinfunction "1_1") (pintype "passive"))
      (node (ref "C35") (pin "1") (pinfunction "1_1") (pintype "passive"))
      (node (ref "C36") (pin "1") (pinfunction "1_1") (pintype "passive"))
      (node (ref "C37") (pin "1") (pinfunction "1_1") (pintype "passive"))
      (node (ref "C38") (pin "1") (pinfunction "1_1") (pintype "passive"))
      (node (ref "C39") (pin "1") (pinfunction "1_1") (pintype "passive"))
      (node (ref "C4") (pin "1") (pinfunction "1_1") (pintype "passive"))
      (node (ref "C40") (pin "1") (pinfunction "1_1") (pintype "passive"))
      (node (ref "C41") (pin "1") (pinfunction "1_1") (pintype "passive"))
      (node (ref "C42") (pin "1") (pinfunction "1_1") (pintype "passive"))
      (node (ref "C43") (pin "1") (pinfunction "1_1") (pintype "passive"))
      (node (ref "C44") (pin "1") (pinfunction "1_1") (pintype "passive"))
      (node (ref "C45") (pin "1") (pinfunction "1_1") (pintype "passive"))
      (node (ref "C46") (pin "1") (pinfunction "1_1") (pintype "passive"))
      (node (ref "C47") (pin "1") (pinfunction "1_1") (pintype "passive"))
      (node (ref "C48") (pin "1") (pinfunction "1_1") (pintype "passive"))
      (node (ref "C49") (pin "1") (pinfunction "1_1") (pintype "passive"))
      (node (ref "C5") (pin "1") (pinfunction "1_1") (pintype "passive"))
      (node (ref "C50") (pin "1") (pinfunction "1_1") (pintype "passive"))
      (node (ref "C51") (pin "1") (pinfunction "1_1") (pintype "passive"))
      (node (ref "C52") (pin "1") (pinfunction "1_1") (pintype "passive"))
      (node (ref "C53") (pin "1") (pinfunction "1_1") (pintype "passive"))
      (node (ref "C54") (pin "1") (pinfunction "1_1") (pintype "passive"))
      (node (ref "C55") (pin "1") (pinfunction "1_1") (pintype "passive"))
      (node (ref "C56") (pin "1") (pinfunction "1_1") (pintype "passive"))
      (node (ref "C57") (pin "1") (pinfunction "1_1") (pintype "passive"))
      (node (ref "C58") (pin "1") (pinfunction "1_1") (pintype "passive"))
      (node (ref "C59") (pin "1") (pinfunction "1_1") (pintype "passive"))
      (node (ref "C6") (pin "1") (pinfunction "1_1") (pintype "passive"))
      (node (ref "C60") (pin "1") (pinfunction "1_1") (pintype "passive"))
      (node (ref "C61") (pin "1") (pinfunction "1_1") (pintype "passive"))
      (node (ref "C62") (pin "1") (pinfunction "1_1") (pintype "passive"))
      (node (ref "C63") (pin "1") (pinfunction "1_1") (pintype "passive"))
      (node (ref "C64") (pin "1") (pinfunction "1_1") (pintype "passive"))
      (node (ref "C65") (pin "1") (pinfunction "1_1") (pintype "passive"))
      (node (ref "C66") (pin "1") (pinfunction "1_1") (pintype "passive"))
      (node (ref "C67") (pin "1") (pinfunction "1_1") (pintype "passive"))
      (node (ref "C68") (pin "1") (pinfunction "1_1") (pintype "passive"))
      (node (ref "C69") (pin "1") (pinfunction "1_1") (pintype "passive"))
      (node (ref "C7") (pin "1") (pinfunction "1_1") (pintype "passive"))
      (node (ref "C70") (pin "1") (pinfunction "1_1") (pintype "passive"))
      (node (ref "C71") (pin "1") (pinfunction "1_1") (pintype "passive"))
      (node (ref "C72") (pin "1") (pinfunction "1_1") (pintype "passive"))
      (node (ref "C73") (pin "1") (pinfunction "1_1") (pintype "passive"))
      (node (ref "C74") (pin "1") (pinfunction "1_1") (pintype "passive"))
      (node (ref "C75") (pin "1") (pinfunction "1_1") (pintype "passive"))
      (node (ref "C76") (pin "1") (pinfunction "1_1") (pintype "passive"))
      (node (ref "C77") (pin "1") (pinfunction "1_1") (pintype "passive"))
      (node (ref "C78") (pin "1") (pinfunction "1_1") (pintype "passive"))
      (node (ref "C79") (pin "1") (pinfunction "1_1") (pintype "passive"))
      (node (ref "C8") (pin "1") (pinfunction "1_1") (pintype "passive"))
      (node (ref "C80") (pin "1") (pinfunction "1_1") (pintype "passive"))
      (node (ref "C81") (pin "1") (pinfunction "1_1") (pintype "passive"))
      (node (ref "C88") (pin "1") (pinfunction "1_1") (pintype "passive"))
      (node (ref "C89") (pin "1") (pinfunction "1_1") (pintype "passive"))
      (node (ref "C9") (pin "1") (pinfunction "1_1") (pintype "passive"))
      (node (ref "C90") (pin "1") (pinfunction "1_1") (pintype "passive"))
      (node (ref "C92") (pin "1") (pinfunction "1_1") (pintype "passive"))
      (node (ref "C93") (pin "1") (pinfunction "1_1") (pintype "passive"))
      (node (ref "C94") (pin "1") (pinfunction "1_1") (pintype "passive"))
      (node (ref "C95") (pin "1") (pinfunction "1_1") (pintype "passive"))
      (node (ref "C96") (pin "1") (pinfunction "1_1") (pintype "passive"))
      (node (ref "C97") (pin "1") (pinfunction "1_1") (pintype "passive"))
      (node (ref "C98") (pin "1") (pinfunction "1_1") (pintype "passive"))
      (node (ref "C99") (pin "1") (pinfunction "1_1") (pintype "passive"))
      (node (ref "IC6") (pin "11") (pinfunction "I10_11") (pintype "input"))
      (node (ref "IC6") (pin "13") (pinfunction "I11_13") (pintype "input"))
      (node (ref "J1") (pin "10") (pinfunction "SGND_10") (pintype "passive"))
      (node (ref "LPC1769") (pin "54") (pinfunction "54_54") (pintype "passive"))
      (node (ref "R12") (pin "2") (pinfunction "2_2") (pintype "passive"))
      (node (ref "SRAM1") (pin "12") (pinfunction "GND_12") (pintype "power_in"))
      (node (ref "SRAM1") (pin "34") (pinfunction "GND_34") (pintype "power_in"))
      (node (ref "SRAM1") (pin "8") (pinfunction "CE_8") (pintype "input"))
      (node (ref "SRAM2") (pin "12") (pinfunction "GND_12") (pintype "power_in"))
      (node (ref "SRAM2") (pin "34") (pinfunction "GND_34") (pintype "power_in"))
      (node (ref "SRAM2") (pin "8") (pinfunction "CE_8") (pintype "input"))
      (node (ref "U1") (pin "11") (pinfunction "GND_11") (pintype "power_in"))
      (node (ref "U1") (pin "18") (pinfunction "GND_18") (pintype "power_in"))
      (node (ref "U1") (pin "25") (pinfunction "GND_25") (pintype "power_in"))
      (node (ref "U1") (pin "32") (pinfunction "GND_32") (pintype "power_in"))
      (node (ref "U1") (pin "39") (pinfunction "GND_39") (pintype "power_in"))
      (node (ref "U1") (pin "4") (pinfunction "GND_4") (pintype "power_in"))
      (node (ref "U1") (pin "46") (pinfunction "GND_46") (pintype "power_in"))
      (node (ref "U1") (pin "53") (pinfunction "GND_53") (pintype "power_in"))
      (node (ref "U12") (pin "3") (pinfunction "D0_3") (pintype "input"))
      (node (ref "U12") (pin "4") (pinfunction "D1_4") (pintype "input"))
      (node (ref "U12") (pin "5") (pinfunction "D2_5") (pintype "input"))
      (node (ref "U12") (pin "6") (pinfunction "D3_6") (pintype "input"))
      (node (ref "U14") (pin "3") (pinfunction "D0_3") (pintype "input"))
      (node (ref "U14") (pin "4") (pinfunction "D1_4") (pintype "input"))
      (node (ref "U14") (pin "5") (pinfunction "D2_5") (pintype "input"))
      (node (ref "U14") (pin "6") (pinfunction "D3_6") (pintype "input"))
      (node (ref "U15") (pin "3") (pinfunction "D0_3") (pintype "input"))
      (node (ref "U15") (pin "4") (pinfunction "D1_4") (pintype "input"))
      (node (ref "U15") (pin "5") (pinfunction "D2_5") (pintype "input"))
      (node (ref "U15") (pin "6") (pinfunction "D3_6") (pintype "input"))
      (node (ref "U16") (pin "3") (pinfunction "D0_3") (pintype "input"))
      (node (ref "U16") (pin "4") (pinfunction "D1_4") (pintype "input"))
      (node (ref "U16") (pin "5") (pinfunction "D2_5") (pintype "input"))
      (node (ref "U16") (pin "6") (pinfunction "D3_6") (pintype "input"))
      (node (ref "U17") (pin "3") (pinfunction "D0_3") (pintype "input"))
      (node (ref "U17") (pin "4") (pinfunction "D1_4") (pintype "input"))
      (node (ref "U17") (pin "5") (pinfunction "D2_5") (pintype "input"))
      (node (ref "U17") (pin "6") (pinfunction "D3_6") (pintype "input"))
      (node (ref "U18") (pin "3") (pinfunction "D0_3") (pintype "input"))
      (node (ref "U18") (pin "4") (pinfunction "D1_4") (pintype "input"))
      (node (ref "U18") (pin "5") (pinfunction "D2_5") (pintype "input"))
      (node (ref "U18") (pin "6") (pinfunction "D3_6") (pintype "input"))
      (node (ref "U19") (pin "3") (pinfunction "D0_3") (pintype "input"))
      (node (ref "U19") (pin "4") (pinfunction "D1_4") (pintype "input"))
      (node (ref "U19") (pin "5") (pinfunction "D2_5") (pintype "input"))
      (node (ref "U19") (pin "6") (pinfunction "D3_6") (pintype "input"))
      (node (ref "U2") (pin "11") (pinfunction "GND_11") (pintype "power_in"))
      (node (ref "U2") (pin "18") (pinfunction "GND_18") (pintype "power_in"))
      (node (ref "U2") (pin "25") (pinfunction "GND_25") (pintype "power_in"))
      (node (ref "U2") (pin "32") (pinfunction "GND_32") (pintype "power_in"))
      (node (ref "U2") (pin "39") (pinfunction "GND_39") (pintype "power_in"))
      (node (ref "U2") (pin "4") (pinfunction "GND_4") (pintype "power_in"))
      (node (ref "U2") (pin "46") (pinfunction "GND_46") (pintype "power_in"))
      (node (ref "U2") (pin "53") (pinfunction "GND_53") (pintype "power_in"))
      (node (ref "U20") (pin "3") (pinfunction "D0_3") (pintype "input"))
      (node (ref "U20") (pin "4") (pinfunction "D1_4") (pintype "input"))
      (node (ref "U20") (pin "5") (pinfunction "D2_5") (pintype "input"))
      (node (ref "U20") (pin "6") (pinfunction "D3_6") (pintype "input"))
      (node (ref "U21") (pin "3") (pinfunction "D0_3") (pintype "input"))
      (node (ref "U21") (pin "4") (pinfunction "D1_4") (pintype "input"))
      (node (ref "U21") (pin "5") (pinfunction "D2_5") (pintype "input"))
      (node (ref "U21") (pin "6") (pinfunction "D3_6") (pintype "input"))
      (node (ref "U22") (pin "13") (pinfunction "OE_13") (pintype "input"))
      (node (ref "U23") (pin "13") (pinfunction "OE_13") (pintype "input"))
      (node (ref "U24") (pin "13") (pinfunction "OE_13") (pintype "input"))
      (node (ref "U25") (pin "13") (pinfunction "OE_13") (pintype "input"))
      (node (ref "U3") (pin "11") (pinfunction "GND_11") (pintype "power_in"))
      (node (ref "U3") (pin "18") (pinfunction "GND_18") (pintype "power_in"))
      (node (ref "U3") (pin "25") (pinfunction "GND_25") (pintype "power_in"))
      (node (ref "U3") (pin "32") (pinfunction "GND_32") (pintype "power_in"))
      (node (ref "U3") (pin "39") (pinfunction "GND_39") (pintype "power_in"))
      (node (ref "U3") (pin "4") (pinfunction "GND_4") (pintype "power_in"))
      (node (ref "U3") (pin "46") (pinfunction "GND_46") (pintype "power_in"))
      (node (ref "U3") (pin "53") (pinfunction "GND_53") (pintype "power_in"))
      (node (ref "U32") (pin "1") (pinfunction "A_1") (pintype "input"))
      (node (ref "U4") (pin "11") (pinfunction "GND_11") (pintype "power_in"))
      (node (ref "U4") (pin "18") (pinfunction "GND_18") (pintype "power_in"))
      (node (ref "U4") (pin "25") (pinfunction "GND_25") (pintype "power_in"))
      (node (ref "U4") (pin "32") (pinfunction "GND_32") (pintype "power_in"))
      (node (ref "U4") (pin "39") (pinfunction "GND_39") (pintype "power_in"))
      (node (ref "U4") (pin "4") (pinfunction "GND_4") (pintype "power_in"))
      (node (ref "U4") (pin "46") (pinfunction "GND_46") (pintype "power_in"))
      (node (ref "U4") (pin "53") (pinfunction "GND_53") (pintype "power_in"))
      (node (ref "U5") (pin "3") (pinfunction "D0_3") (pintype "input"))
      (node (ref "U5") (pin "4") (pinfunction "D1_4") (pintype "input"))
      (node (ref "U5") (pin "5") (pinfunction "D2_5") (pintype "input"))
      (node (ref "U5") (pin "6") (pinfunction "D3_6") (pintype "input"))
      (node (ref "U6") (pin "3") (pinfunction "D0_3") (pintype "input"))
      (node (ref "U6") (pin "4") (pinfunction "D1_4") (pintype "input"))
      (node (ref "U6") (pin "5") (pinfunction "D2_5") (pintype "input"))
      (node (ref "U6") (pin "6") (pinfunction "D3_6") (pintype "input"))
      (node (ref "U7") (pin "3") (pinfunction "J_3") (pintype "input"))
      (node (ref "X1") (pin "2") (pinfunction "GND_2") (pintype "power_in"))
      (node (ref "X2") (pin "1") (pinfunction "K_1") (pintype "passive"))
    )
    (net (code "57") (name "HS") (class "Default")
      (node (ref "IC7") (pin "20") (pinfunction "I/O6_20") (pintype "bidirectional"))
      (node (ref "U29") (pin "2") (pinfunction "J_2") (pintype "input"))
    )
    (net (code "58") (name "HSYNC") (class "Default")
      (node (ref "J1") (pin "13") (pinfunction "HSYNC_13") (pintype "passive"))
      (node (ref "U29") (pin "6") (pinfunction "Q_6") (pintype "output"))
    )
    (net (code "59") (name "H_BLANK") (class "Default")
      (node (ref "IC7") (pin "17") (pinfunction "I/O3_17") (pintype "bidirectional"))
      (node (ref "U30") (pin "2") (pinfunction "J_2") (pintype "input"))
    )
    (net (code "60") (name "M1_~{R}{slash}W") (class "Default")
      (node (ref "SRAM1") (pin "37") (pinfunction "OE_37") (pintype "input"))
      (node (ref "U10") (pin "19") (pinfunction "OE_19") (pintype "input"))
      (node (ref "U2") (pin "1") (pinfunction "1OE1_1") (pintype "input"))
      (node (ref "U2") (pin "28") (pinfunction "2OE1_28") (pintype "input"))
      (node (ref "U2") (pin "29") (pinfunction "2OE2_29") (pintype "input"))
      (node (ref "U2") (pin "56") (pinfunction "1OE2_56") (pintype "input"))
      (node (ref "U27") (pin "1") (pinfunction "B_1") (pintype "input"))
      (node (ref "U28") (pin "5") (pinfunction "Q_5") (pintype "output"))
      (node (ref "U3") (pin "1") (pinfunction "1OE1_1") (pintype "input"))
      (node (ref "U3") (pin "28") (pinfunction "2OE1_28") (pintype "input"))
      (node (ref "U3") (pin "29") (pinfunction "2OE2_29") (pintype "input"))
      (node (ref "U3") (pin "56") (pinfunction "1OE2_56") (pintype "input"))
      (node (ref "U9") (pin "19") (pinfunction "OE_19") (pintype "input"))
    )
    (net (code "61") (name "M2_~{R}{slash}W") (class "Default")
      (node (ref "SRAM2") (pin "37") (pinfunction "OE_37") (pintype "input"))
      (node (ref "U1") (pin "1") (pinfunction "1OE1_1") (pintype "input"))
      (node (ref "U1") (pin "28") (pinfunction "2OE1_28") (pintype "input"))
      (node (ref "U1") (pin "29") (pinfunction "2OE2_29") (pintype "input"))
      (node (ref "U1") (pin "56") (pinfunction "1OE2_56") (pintype "input"))
      (node (ref "U11") (pin "19") (pinfunction "OE_19") (pintype "input"))
      (node (ref "U28") (pin "6") (pinfunction "~{Q}_6") (pintype "output"))
      (node (ref "U31") (pin "1") (pinfunction "B_1") (pintype "input"))
      (node (ref "U4") (pin "1") (pinfunction "1OE1_1") (pintype "input"))
      (node (ref "U4") (pin "28") (pinfunction "2OE1_28") (pintype "input"))
      (node (ref "U4") (pin "29") (pinfunction "2OE2_29") (pintype "input"))
      (node (ref "U4") (pin "56") (pinfunction "1OE2_56") (pintype "input"))
      (node (ref "U8") (pin "19") (pinfunction "OE_19") (pintype "input"))
    )
    (net (code "62") (name "MEM1_A0") (class "Default")
      (node (ref "SRAM1") (pin "3") (pinfunction "A0_3") (pintype "input"))
      (node (ref "U1") (pin "27") (pinfunction "2Y10_27") (pintype "output"))
      (node (ref "U2") (pin "2") (pinfunction "1Y1_2") (pintype "output"))
    )
    (net (code "63") (name "MEM1_A1") (class "Default")
      (node (ref "SRAM1") (pin "4") (pinfunction "A1_4") (pintype "input"))
      (node (ref "U1") (pin "26") (pinfunction "2Y9_26") (pintype "output"))
      (node (ref "U2") (pin "3") (pinfunction "1Y2_3") (pintype "output"))
    )
    (net (code "64") (name "MEM1_A2") (class "Default")
      (node (ref "SRAM1") (pin "5") (pinfunction "A2_5") (pintype "input"))
      (node (ref "U1") (pin "24") (pinfunction "2Y8_24") (pintype "output"))
      (node (ref "U2") (pin "5") (pinfunction "1Y3_5") (pintype "output"))
    )
    (net (code "65") (name "MEM1_A3") (class "Default")
      (node (ref "SRAM1") (pin "6") (pinfunction "A3_6") (pintype "input"))
      (node (ref "U1") (pin "23") (pinfunction "2Y7_23") (pintype "output"))
      (node (ref "U2") (pin "6") (pinfunction "1Y4_6") (pintype "output"))
    )
    (net (code "66") (name "MEM1_A4") (class "Default")
      (node (ref "SRAM1") (pin "7") (pinfunction "A4_7") (pintype "input"))
      (node (ref "U1") (pin "21") (pinfunction "2Y6_21") (pintype "output"))
      (node (ref "U2") (pin "8") (pinfunction "1Y5_8") (pintype "output"))
    )
    (net (code "67") (name "MEM1_A5") (class "Default")
      (node (ref "SRAM1") (pin "16") (pinfunction "A5_16") (pintype "input"))
      (node (ref "U1") (pin "20") (pinfunction "2Y5_20") (pintype "output"))
      (node (ref "U2") (pin "9") (pinfunction "1Y6_9") (pintype "output"))
    )
    (net (code "68") (name "MEM1_A6") (class "Default")
      (node (ref "SRAM1") (pin "17") (pinfunction "A6_17") (pintype "input"))
      (node (ref "U1") (pin "19") (pinfunction "2Y4_19") (pintype "output"))
      (node (ref "U2") (pin "10") (pinfunction "1Y7_10") (pintype "output"))
    )
    (net (code "69") (name "MEM1_A7") (class "Default")
      (node (ref "SRAM1") (pin "18") (pinfunction "A7_18") (pintype "input"))
      (node (ref "U1") (pin "17") (pinfunction "2Y3_17") (pintype "output"))
      (node (ref "U2") (pin "12") (pinfunction "1Y8_12") (pintype "output"))
    )
    (net (code "70") (name "MEM1_A8") (class "Default")
      (node (ref "SRAM1") (pin "19") (pinfunction "A8_19") (pintype "input"))
      (node (ref "U1") (pin "16") (pinfunction "2Y2_16") (pintype "output"))
      (node (ref "U2") (pin "13") (pinfunction "1Y9_13") (pintype "output"))
    )
    (net (code "71") (name "MEM1_A9") (class "Default")
      (node (ref "SRAM1") (pin "20") (pinfunction "A9_20") (pintype "input"))
      (node (ref "U1") (pin "15") (pinfunction "2Y1_15") (pintype "output"))
      (node (ref "U2") (pin "14") (pinfunction "1Y10_14") (pintype "output"))
    )
    (net (code "72") (name "MEM1_A10") (class "Default")
      (node (ref "SRAM1") (pin "26") (pinfunction "A10_26") (pintype "input"))
      (node (ref "U1") (pin "14") (pinfunction "1Y10_14") (pintype "output"))
      (node (ref "U2") (pin "15") (pinfunction "2Y1_15") (pintype "output"))
    )
    (net (code "73") (name "MEM1_A11") (class "Default")
      (node (ref "SRAM1") (pin "27") (pinfunction "A11_27") (pintype "input"))
      (node (ref "U1") (pin "13") (pinfunction "1Y9_13") (pintype "output"))
      (node (ref "U2") (pin "16") (pinfunction "2Y2_16") (pintype "output"))
    )
    (net (code "74") (name "MEM1_A12") (class "Default")
      (node (ref "SRAM1") (pin "28") (pinfunction "A12_28") (pintype "input"))
      (node (ref "U1") (pin "12") (pinfunction "1Y8_12") (pintype "output"))
      (node (ref "U2") (pin "17") (pinfunction "2Y3_17") (pintype "output"))
    )
    (net (code "75") (name "MEM1_A13") (class "Default")
      (node (ref "SRAM1") (pin "29") (pinfunction "A13_29") (pintype "input"))
      (node (ref "U1") (pin "10") (pinfunction "1Y7_10") (pintype "output"))
      (node (ref "U2") (pin "19") (pinfunction "2Y4_19") (pintype "output"))
    )
    (net (code "76") (name "MEM1_A14") (class "Default")
      (node (ref "SRAM1") (pin "30") (pinfunction "A14_30") (pintype "input"))
      (node (ref "U1") (pin "9") (pinfunction "1Y6_9") (pintype "output"))
      (node (ref "U2") (pin "20") (pinfunction "2Y5_20") (pintype "output"))
    )
    (net (code "77") (name "MEM1_A15") (class "Default")
      (node (ref "SRAM1") (pin "38") (pinfunction "A15_38") (pintype "input"))
      (node (ref "U1") (pin "8") (pinfunction "1Y5_8") (pintype "output"))
      (node (ref "U2") (pin "21") (pinfunction "2Y6_21") (pintype "output"))
    )
    (net (code "78") (name "MEM1_A16") (class "Default")
      (node (ref "SRAM1") (pin "39") (pinfunction "A16_39") (pintype "input"))
      (node (ref "U1") (pin "6") (pinfunction "1Y4_6") (pintype "output"))
      (node (ref "U2") (pin "23") (pinfunction "2Y7_23") (pintype "output"))
    )
    (net (code "79") (name "MEM1_A17") (class "Default")
      (node (ref "SRAM1") (pin "40") (pinfunction "A17_40") (pintype "input"))
      (node (ref "U1") (pin "5") (pinfunction "1Y3_5") (pintype "output"))
      (node (ref "U2") (pin "24") (pinfunction "2Y8_24") (pintype "output"))
    )
    (net (code "80") (name "MEM1_A18") (class "Default")
      (node (ref "SRAM1") (pin "41") (pinfunction "A18_41") (pintype "input"))
      (node (ref "U1") (pin "3") (pinfunction "1Y2_3") (pintype "output"))
      (node (ref "U2") (pin "26") (pinfunction "2Y9_26") (pintype "output"))
    )
    (net (code "81") (name "MEM1_A19") (class "Default")
      (node (ref "SRAM1") (pin "25") (pinfunction "A19_25") (pintype "input"))
      (node (ref "U1") (pin "2") (pinfunction "1Y1_2") (pintype "output"))
      (node (ref "U2") (pin "27") (pinfunction "2Y10_27") (pintype "output"))
    )
    (net (code "82") (name "MEM1_D0") (class "Default")
      (node (ref "SRAM1") (pin "9") (pinfunction "I/O00_9") (pintype "bidirectional"))
      (node (ref "U10") (pin "9") (pinfunction "A8_9") (pintype "input"))
      (node (ref "U8") (pin "11") (pinfunction "B8_11") (pintype "output"))
    )
    (net (code "83") (name "MEM1_D1") (class "Default")
      (node (ref "SRAM1") (pin "10") (pinfunction "I/O01_10") (pintype "bidirectional"))
      (node (ref "U10") (pin "8") (pinfunction "A7_8") (pintype "input"))
      (node (ref "U8") (pin "12") (pinfunction "B7_12") (pintype "output"))
    )
    (net (code "84") (name "MEM1_D2") (class "Default")
      (node (ref "SRAM1") (pin "13") (pinfunction "I/O02_13") (pintype "bidirectional"))
      (node (ref "U10") (pin "7") (pinfunction "A6_7") (pintype "input"))
      (node (ref "U8") (pin "13") (pinfunction "B6_13") (pintype "output"))
    )
    (net (code "85") (name "MEM1_D3") (class "Default")
      (node (ref "SRAM1") (pin "14") (pinfunction "I/O03_14") (pintype "bidirectional"))
      (node (ref "U10") (pin "6") (pinfunction "A5_6") (pintype "input"))
      (node (ref "U8") (pin "14") (pinfunction "B5_14") (pintype "output"))
    )
    (net (code "86") (name "MEM1_D4") (class "Default")
      (node (ref "SRAM1") (pin "31") (pinfunction "I/O04_31") (pintype "bidirectional"))
      (node (ref "U10") (pin "5") (pinfunction "A4_5") (pintype "input"))
      (node (ref "U8") (pin "15") (pinfunction "B4_15") (pintype "output"))
    )
    (net (code "87") (name "MEM1_D5") (class "Default")
      (node (ref "SRAM1") (pin "32") (pinfunction "I/O05_32") (pintype "bidirectional"))
      (node (ref "U10") (pin "4") (pinfunction "A3_4") (pintype "input"))
      (node (ref "U8") (pin "16") (pinfunction "B3_16") (pintype "output"))
    )
    (net (code "88") (name "MEM1_D6") (class "Default")
      (node (ref "SRAM1") (pin "35") (pinfunction "I/O06_35") (pintype "bidirectional"))
      (node (ref "U10") (pin "3") (pinfunction "A2_3") (pintype "input"))
      (node (ref "U8") (pin "17") (pinfunction "B2_17") (pintype "output"))
    )
    (net (code "89") (name "MEM1_D7") (class "Default")
      (node (ref "SRAM1") (pin "36") (pinfunction "I/O07_36") (pintype "bidirectional"))
      (node (ref "U10") (pin "2") (pinfunction "A1_2") (pintype "input"))
      (node (ref "U8") (pin "18") (pinfunction "B1_18") (pintype "output"))
    )
    (net (code "90") (name "MEM2_A0") (class "Default")
      (node (ref "SRAM2") (pin "3") (pinfunction "A0_3") (pintype "input"))
      (node (ref "U3") (pin "2") (pinfunction "1Y1_2") (pintype "output"))
      (node (ref "U4") (pin "27") (pinfunction "2Y10_27") (pintype "output"))
    )
    (net (code "91") (name "MEM2_A1") (class "Default")
      (node (ref "SRAM2") (pin "4") (pinfunction "A1_4") (pintype "input"))
      (node (ref "U3") (pin "3") (pinfunction "1Y2_3") (pintype "output"))
      (node (ref "U4") (pin "26") (pinfunction "2Y9_26") (pintype "output"))
    )
    (net (code "92") (name "MEM2_A2") (class "Default")
      (node (ref "SRAM2") (pin "5") (pinfunction "A2_5") (pintype "input"))
      (node (ref "U3") (pin "5") (pinfunction "1Y3_5") (pintype "output"))
      (node (ref "U4") (pin "24") (pinfunction "2Y8_24") (pintype "output"))
    )
    (net (code "93") (name "MEM2_A3") (class "Default")
      (node (ref "SRAM2") (pin "6") (pinfunction "A3_6") (pintype "input"))
      (node (ref "U3") (pin "6") (pinfunction "1Y4_6") (pintype "output"))
      (node (ref "U4") (pin "23") (pinfunction "2Y7_23") (pintype "output"))
    )
    (net (code "94") (name "MEM2_A4") (class "Default")
      (node (ref "SRAM2") (pin "7") (pinfunction "A4_7") (pintype "input"))
      (node (ref "U3") (pin "8") (pinfunction "1Y5_8") (pintype "output"))
      (node (ref "U4") (pin "21") (pinfunction "2Y6_21") (pintype "output"))
    )
    (net (code "95") (name "MEM2_A5") (class "Default")
      (node (ref "SRAM2") (pin "16") (pinfunction "A5_16") (pintype "input"))
      (node (ref "U3") (pin "9") (pinfunction "1Y6_9") (pintype "output"))
      (node (ref "U4") (pin "20") (pinfunction "2Y5_20") (pintype "output"))
    )
    (net (code "96") (name "MEM2_A6") (class "Default")
      (node (ref "SRAM2") (pin "17") (pinfunction "A6_17") (pintype "input"))
      (node (ref "U3") (pin "10") (pinfunction "1Y7_10") (pintype "output"))
      (node (ref "U4") (pin "19") (pinfunction "2Y4_19") (pintype "output"))
    )
    (net (code "97") (name "MEM2_A7") (class "Default")
      (node (ref "SRAM2") (pin "18") (pinfunction "A7_18") (pintype "input"))
      (node (ref "U3") (pin "12") (pinfunction "1Y8_12") (pintype "output"))
      (node (ref "U4") (pin "17") (pinfunction "2Y3_17") (pintype "output"))
    )
    (net (code "98") (name "MEM2_A8") (class "Default")
      (node (ref "SRAM2") (pin "19") (pinfunction "A8_19") (pintype "input"))
      (node (ref "U3") (pin "13") (pinfunction "1Y9_13") (pintype "output"))
      (node (ref "U4") (pin "16") (pinfunction "2Y2_16") (pintype "output"))
    )
    (net (code "99") (name "MEM2_A9") (class "Default")
      (node (ref "SRAM2") (pin "20") (pinfunction "A9_20") (pintype "input"))
      (node (ref "U3") (pin "14") (pinfunction "1Y10_14") (pintype "output"))
      (node (ref "U4") (pin "15") (pinfunction "2Y1_15") (pintype "output"))
    )
    (net (code "100") (name "MEM2_A10") (class "Default")
      (node (ref "SRAM2") (pin "26") (pinfunction "A10_26") (pintype "input"))
      (node (ref "U3") (pin "15") (pinfunction "2Y1_15") (pintype "output"))
      (node (ref "U4") (pin "14") (pinfunction "1Y10_14") (pintype "output"))
    )
    (net (code "101") (name "MEM2_A11") (class "Default")
      (node (ref "SRAM2") (pin "27") (pinfunction "A11_27") (pintype "input"))
      (node (ref "U3") (pin "16") (pinfunction "2Y2_16") (pintype "output"))
      (node (ref "U4") (pin "13") (pinfunction "1Y9_13") (pintype "output"))
    )
    (net (code "102") (name "MEM2_A12") (class "Default")
      (node (ref "SRAM2") (pin "28") (pinfunction "A12_28") (pintype "input"))
      (node (ref "U3") (pin "17") (pinfunction "2Y3_17") (pintype "output"))
      (node (ref "U4") (pin "12") (pinfunction "1Y8_12") (pintype "output"))
    )
    (net (code "103") (name "MEM2_A13") (class "Default")
      (node (ref "SRAM2") (pin "29") (pinfunction "A13_29") (pintype "input"))
      (node (ref "U3") (pin "19") (pinfunction "2Y4_19") (pintype "output"))
      (node (ref "U4") (pin "10") (pinfunction "1Y7_10") (pintype "output"))
    )
    (net (code "104") (name "MEM2_A14") (class "Default")
      (node (ref "SRAM2") (pin "30") (pinfunction "A14_30") (pintype "input"))
      (node (ref "U3") (pin "20") (pinfunction "2Y5_20") (pintype "output"))
      (node (ref "U4") (pin "9") (pinfunction "1Y6_9") (pintype "output"))
    )
    (net (code "105") (name "MEM2_A15") (class "Default")
      (node (ref "SRAM2") (pin "38") (pinfunction "A15_38") (pintype "input"))
      (node (ref "U3") (pin "21") (pinfunction "2Y6_21") (pintype "output"))
      (node (ref "U4") (pin "8") (pinfunction "1Y5_8") (pintype "output"))
    )
    (net (code "106") (name "MEM2_A16") (class "Default")
      (node (ref "SRAM2") (pin "39") (pinfunction "A16_39") (pintype "input"))
      (node (ref "U3") (pin "23") (pinfunction "2Y7_23") (pintype "output"))
      (node (ref "U4") (pin "6") (pinfunction "1Y4_6") (pintype "output"))
    )
    (net (code "107") (name "MEM2_A17") (class "Default")
      (node (ref "SRAM2") (pin "40") (pinfunction "A17_40") (pintype "input"))
      (node (ref "U3") (pin "24") (pinfunction "2Y8_24") (pintype "output"))
      (node (ref "U4") (pin "5") (pinfunction "1Y3_5") (pintype "output"))
    )
    (net (code "108") (name "MEM2_A18") (class "Default")
      (node (ref "SRAM2") (pin "41") (pinfunction "A18_41") (pintype "input"))
      (node (ref "U3") (pin "26") (pinfunction "2Y9_26") (pintype "output"))
      (node (ref "U4") (pin "3") (pinfunction "1Y2_3") (pintype "output"))
    )
    (net (code "109") (name "MEM2_A19") (class "Default")
      (node (ref "SRAM2") (pin "25") (pinfunction "A19_25") (pintype "input"))
      (node (ref "U3") (pin "27") (pinfunction "2Y10_27") (pintype "output"))
      (node (ref "U4") (pin "2") (pinfunction "1Y1_2") (pintype "output"))
    )
    (net (code "110") (name "MEM2_D0") (class "Default")
      (node (ref "SRAM2") (pin "9") (pinfunction "I/O00_9") (pintype "bidirectional"))
      (node (ref "U11") (pin "2") (pinfunction "A1_2") (pintype "input"))
      (node (ref "U9") (pin "18") (pinfunction "B1_18") (pintype "output"))
    )
    (net (code "111") (name "MEM2_D1") (class "Default")
      (node (ref "SRAM2") (pin "10") (pinfunction "I/O01_10") (pintype "bidirectional"))
      (node (ref "U11") (pin "3") (pinfunction "A2_3") (pintype "input"))
      (node (ref "U9") (pin "17") (pinfunction "B2_17") (pintype "output"))
    )
    (net (code "112") (name "MEM2_D2") (class "Default")
      (node (ref "SRAM2") (pin "13") (pinfunction "I/O02_13") (pintype "bidirectional"))
      (node (ref "U11") (pin "4") (pinfunction "A3_4") (pintype "input"))
      (node (ref "U9") (pin "16") (pinfunction "B3_16") (pintype "output"))
    )
    (net (code "113") (name "MEM2_D3") (class "Default")
      (node (ref "SRAM2") (pin "14") (pinfunction "I/O03_14") (pintype "bidirectional"))
      (node (ref "U11") (pin "5") (pinfunction "A4_5") (pintype "input"))
      (node (ref "U9") (pin "15") (pinfunction "B4_15") (pintype "output"))
    )
    (net (code "114") (name "MEM2_D4") (class "Default")
      (node (ref "SRAM2") (pin "31") (pinfunction "I/O04_31") (pintype "bidirectional"))
      (node (ref "U11") (pin "6") (pinfunction "A5_6") (pintype "input"))
      (node (ref "U9") (pin "14") (pinfunction "B5_14") (pintype "output"))
    )
    (net (code "115") (name "MEM2_D5") (class "Default")
      (node (ref "SRAM2") (pin "32") (pinfunction "I/O05_32") (pintype "bidirectional"))
      (node (ref "U11") (pin "7") (pinfunction "A6_7") (pintype "input"))
      (node (ref "U9") (pin "13") (pinfunction "B6_13") (pintype "output"))
    )
    (net (code "116") (name "MEM2_D6") (class "Default")
      (node (ref "SRAM2") (pin "35") (pinfunction "I/O06_35") (pintype "bidirectional"))
      (node (ref "U11") (pin "8") (pinfunction "A7_8") (pintype "input"))
      (node (ref "U9") (pin "12") (pinfunction "B7_12") (pintype "output"))
    )
    (net (code "117") (name "MEM2_D7") (class "Default")
      (node (ref "SRAM2") (pin "36") (pinfunction "I/O07_36") (pintype "bidirectional"))
      (node (ref "U11") (pin "9") (pinfunction "A8_9") (pintype "input"))
      (node (ref "U9") (pin "11") (pinfunction "B8_11") (pintype "output"))
    )
    (net (code "118") (name "MOSI") (class "Default")
      (node (ref "LPC1769") (pin "11") (pinfunction "11_11") (pintype "passive"))
      (node (ref "U22") (pin "14") (pinfunction "DS_14") (pintype "input"))
    )
    (net (code "119") (name "Net-(ADV7125-COMP)") (class "Default")
      (node (ref "ADV7125") (pin "35") (pinfunction "COMP_35") (pintype "passive"))
      (node (ref "C1") (pin "1") (pinfunction "1_1") (pintype "passive"))
    )
    (net (code "120") (name "Net-(ADV7125-RSET)") (class "Default")
      (node (ref "ADV7125") (pin "37") (pinfunction "RSET_37") (pintype "input"))
      (node (ref "R1") (pin "2") (pinfunction "2_2") (pintype "passive"))
    )
    (net (code "121") (name "Net-(ADV7125-VREF)") (class "Default")
      (node (ref "ADV7125") (pin "36") (pinfunction "VREF_36") (pintype "input"))
      (node (ref "C91") (pin "2") (pinfunction "2_2") (pintype "passive"))
      (node (ref "D1") (pin "1") (pinfunction "V+_1") (pintype "passive"))
      (node (ref "R8") (pin "1") (pinfunction "1_1") (pintype "passive"))
    )
    (net (code "122") (name "Net-(C88-Pad2)") (class "Default")
      (node (ref "C88") (pin "2") (pinfunction "2_2") (pintype "passive"))
      (node (ref "R5") (pin "1") (pinfunction "1_1") (pintype "passive"))
    )
    (net (code "123") (name "Net-(C89-Pad2)") (class "Default")
      (node (ref "C89") (pin "2") (pinfunction "2_2") (pintype "passive"))
      (node (ref "R9") (pin "1") (pinfunction "1_1") (pintype "passive"))
    )
    (net (code "124") (name "Net-(C90-Pad2)") (class "Default")
      (node (ref "C90") (pin "2") (pinfunction "2_2") (pintype "passive"))
      (node (ref "R10") (pin "2") (pinfunction "2_2") (pintype "passive"))
    )
    (net (code "125") (name "Net-(C102-Pad2)") (class "Default")
      (node (ref "C102") (pin "2") (pinfunction "2_2") (pintype "passive"))
      (node (ref "R11") (pin "1") (pinfunction "1_1") (pintype "passive"))
    )
    (net (code "126") (name "Net-(D2-PadC)") (class "Default")
      (node (ref "D2") (pin "C") (pinfunction "C_C") (pintype "passive"))
      (node (ref "R12") (pin "1") (pinfunction "1_1") (pintype "passive"))
    )
    (net (code "127") (name "Net-(IC6A-CLK{slash}I0)") (class "Default")
      (node (ref "IC6") (pin "1") (pinfunction "CLK/I0_1") (pintype "input"))
      (node (ref "U19") (pin "14") (pinfunction "Q0_14") (pintype "output"))
    )
    (net (code "128") (name "Net-(IC6A-I1)") (class "Default")
      (node (ref "IC6") (pin "2") (pinfunction "I1_2") (pintype "input"))
      (node (ref "U19") (pin "13") (pinfunction "Q1_13") (pintype "output"))
    )
    (net (code "129") (name "Net-(IC6A-I2)") (class "Default")
      (node (ref "IC6") (pin "3") (pinfunction "I2_3") (pintype "input"))
      (node (ref "U19") (pin "12") (pinfunction "Q2_12") (pintype "output"))
    )
    (net (code "130") (name "Net-(IC6A-I3)") (class "Default")
      (node (ref "IC6") (pin "4") (pinfunction "I3_4") (pintype "input"))
      (node (ref "U19") (pin "11") (pinfunction "Q3_11") (pintype "output"))
    )
    (net (code "131") (name "Net-(IC6A-I4)") (class "Default")
      (node (ref "IC6") (pin "5") (pinfunction "I4_5") (pintype "input"))
      (node (ref "U20") (pin "14") (pinfunction "Q0_14") (pintype "output"))
    )
    (net (code "132") (name "Net-(IC6A-I5)") (class "Default")
      (node (ref "IC6") (pin "6") (pinfunction "I5_6") (pintype "input"))
      (node (ref "U20") (pin "13") (pinfunction "Q1_13") (pintype "output"))
    )
    (net (code "133") (name "Net-(IC6A-I6)") (class "Default")
      (node (ref "IC6") (pin "7") (pinfunction "I6_7") (pintype "input"))
      (node (ref "U20") (pin "12") (pinfunction "Q2_12") (pintype "output"))
    )
    (net (code "134") (name "Net-(IC6A-I7)") (class "Default")
      (node (ref "IC6") (pin "8") (pinfunction "I7_8") (pintype "input"))
      (node (ref "U20") (pin "11") (pinfunction "Q3_11") (pintype "output"))
    )
    (net (code "135") (name "Net-(IC6A-I8)") (class "Default")
      (node (ref "IC6") (pin "9") (pinfunction "I8_9") (pintype "input"))
      (node (ref "U21") (pin "14") (pinfunction "Q0_14") (pintype "output"))
    )
    (net (code "136") (name "Net-(IC6A-I9)") (class "Default")
      (node (ref "IC6") (pin "10") (pinfunction "I9_10") (pintype "input"))
      (node (ref "U21") (pin "13") (pinfunction "Q1_13") (pintype "output"))
    )
    (net (code "137") (name "Net-(IC7A-CLK{slash}I0)") (class "Default")
      (node (ref "IC7") (pin "1") (pinfunction "CLK/I0_1") (pintype "input"))
      (node (ref "U6") (pin "14") (pinfunction "Q0_14") (pintype "output"))
    )
    (net (code "138") (name "Net-(IC7A-I1)") (class "Default")
      (node (ref "IC7") (pin "2") (pinfunction "I1_2") (pintype "input"))
      (node (ref "U6") (pin "13") (pinfunction "Q1_13") (pintype "output"))
    )
    (net (code "139") (name "Net-(IC7A-I2)") (class "Default")
      (node (ref "IC7") (pin "3") (pinfunction "I2_3") (pintype "input"))
      (node (ref "U6") (pin "12") (pinfunction "Q2_12") (pintype "output"))
    )
    (net (code "140") (name "Net-(IC7A-I3)") (class "Default")
      (node (ref "IC7") (pin "4") (pinfunction "I3_4") (pintype "input"))
      (node (ref "U6") (pin "11") (pinfunction "Q3_11") (pintype "output"))
    )
    (net (code "141") (name "Net-(IC7A-I4)") (class "Default")
      (node (ref "IC7") (pin "5") (pinfunction "I4_5") (pintype "input"))
      (node (ref "U17") (pin "14") (pinfunction "Q0_14") (pintype "output"))
    )
    (net (code "142") (name "Net-(IC7A-I5)") (class "Default")
      (node (ref "IC7") (pin "6") (pinfunction "I5_6") (pintype "input"))
      (node (ref "U17") (pin "13") (pinfunction "Q1_13") (pintype "output"))
    )
    (net (code "143") (name "Net-(IC7A-I6)") (class "Default")
      (node (ref "IC7") (pin "7") (pinfunction "I6_7") (pintype "input"))
      (node (ref "U17") (pin "12") (pinfunction "Q2_12") (pintype "output"))
    )
    (net (code "144") (name "Net-(IC7A-I7)") (class "Default")
      (node (ref "IC7") (pin "8") (pinfunction "I7_8") (pintype "input"))
      (node (ref "U17") (pin "11") (pinfunction "Q3_11") (pintype "output"))
    )
    (net (code "145") (name "Net-(IC7A-I8)") (class "Default")
      (node (ref "IC7") (pin "9") (pinfunction "I8_9") (pintype "input"))
      (node (ref "U18") (pin "14") (pinfunction "Q0_14") (pintype "output"))
    )
    (net (code "146") (name "Net-(IC7A-I9)") (class "Default")
      (node (ref "IC7") (pin "10") (pinfunction "I9_10") (pintype "input"))
      (node (ref "U18") (pin "13") (pinfunction "Q1_13") (pintype "output"))
    )
    (net (code "147") (name "Net-(IC7A-I10)") (class "Default")
      (node (ref "IC7") (pin "11") (pinfunction "I10_11") (pintype "input"))
      (node (ref "U18") (pin "12") (pinfunction "Q2_12") (pintype "output"))
    )
    (net (code "148") (name "Net-(IC7A-I11)") (class "Default")
      (node (ref "IC7") (pin "13") (pinfunction "I11_13") (pintype "input"))
      (node (ref "U18") (pin "11") (pinfunction "Q3_11") (pintype "output"))
    )
    (net (code "149") (name "Net-(U12A-CEP)") (class "Default")
      (node (ref "U12") (pin "10") (pinfunction "CET_10") (pintype "input"))
      (node (ref "U12") (pin "7") (pinfunction "CEP_7") (pintype "input"))
      (node (ref "U5") (pin "15") (pinfunction "TC_15") (pintype "output"))
    )
    (net (code "150") (name "Net-(U12A-TC)") (class "Default")
      (node (ref "U12") (pin "15") (pinfunction "TC_15") (pintype "output"))
      (node (ref "U14") (pin "10") (pinfunction "CET_10") (pintype "input"))
      (node (ref "U14") (pin "7") (pinfunction "CEP_7") (pintype "input"))
    )
    (net (code "151") (name "Net-(U13A-A)") (class "Default")
      (node (ref "U13") (pin "1") (pinfunction "A_1") (pintype "input"))
      (node (ref "U30") (pin "10") (pinfunction "Q_10") (pintype "output"))
    )
    (net (code "152") (name "Net-(U13A-B)") (class "Default")
      (node (ref "U13") (pin "2") (pinfunction "B_2") (pintype "input"))
      (node (ref "U30") (pin "6") (pinfunction "Q_6") (pintype "output"))
    )
    (net (code "153") (name "Net-(U14A-TC)") (class "Default")
      (node (ref "U14") (pin "15") (pinfunction "TC_15") (pintype "output"))
      (node (ref "U15") (pin "10") (pinfunction "CET_10") (pintype "input"))
      (node (ref "U15") (pin "7") (pinfunction "CEP_7") (pintype "input"))
    )
    (net (code "154") (name "Net-(U15A-TC)") (class "Default")
      (node (ref "U15") (pin "15") (pinfunction "TC_15") (pintype "output"))
      (node (ref "U16") (pin "10") (pinfunction "CET_10") (pintype "input"))
      (node (ref "U16") (pin "7") (pinfunction "CEP_7") (pintype "input"))
    )
    (net (code "155") (name "Net-(U17A-CEP)") (class "Default")
      (node (ref "U17") (pin "10") (pinfunction "CET_10") (pintype "input"))
      (node (ref "U17") (pin "7") (pinfunction "CEP_7") (pintype "input"))
      (node (ref "U6") (pin "15") (pinfunction "TC_15") (pintype "output"))
    )
    (net (code "156") (name "Net-(U17A-TC)") (class "Default")
      (node (ref "U17") (pin "15") (pinfunction "TC_15") (pintype "output"))
      (node (ref "U18") (pin "10") (pinfunction "CET_10") (pintype "input"))
      (node (ref "U18") (pin "7") (pinfunction "CEP_7") (pintype "input"))
    )
    (net (code "157") (name "Net-(U19A-TC)") (class "Default")
      (node (ref "U19") (pin "15") (pinfunction "TC_15") (pintype "output"))
      (node (ref "U20") (pin "10") (pinfunction "CET_10") (pintype "input"))
      (node (ref "U20") (pin "7") (pinfunction "CEP_7") (pintype "input"))
    )
    (net (code "158") (name "Net-(U20A-TC)") (class "Default")
      (node (ref "U20") (pin "15") (pinfunction "TC_15") (pintype "output"))
      (node (ref "U21") (pin "10") (pinfunction "CET_10") (pintype "input"))
      (node (ref "U21") (pin "7") (pinfunction "CEP_7") (pintype "input"))
    )
    (net (code "159") (name "Net-(U22A-Q7S)") (class "Default")
      (node (ref "U22") (pin "9") (pinfunction "Q7S_9") (pintype "output"))
      (node (ref "U23") (pin "14") (pinfunction "DS_14") (pintype "input"))
    )
    (net (code "160") (name "Net-(U23A-Q7S)") (class "Default")
      (node (ref "U23") (pin "9") (pinfunction "Q7S_9") (pintype "output"))
      (node (ref "U24") (pin "14") (pinfunction "DS_14") (pintype "input"))
    )
    (net (code "161") (name "Net-(U24A-Q7S)") (class "Default")
      (node (ref "U24") (pin "9") (pinfunction "Q7S_9") (pintype "output"))
      (node (ref "U25") (pin "14") (pinfunction "DS_14") (pintype "input"))
    )
    (net (code "162") (name "Net-(U32A-Y)") (class "Default")
      (node (ref "U32") (pin "4") (pinfunction "Y_4") (pintype "output"))
      (node (ref "U7") (pin "4") (pinfunction "PRE_4") (pintype "input"))
    )
    (net (code "163") (name "Net-(X2C-K)") (class "Default")
      (node (ref "L2") (pin "1") (pinfunction "1_1") (pintype "passive"))
      (node (ref "X2") (pin "3") (pinfunction "K_3") (pintype "passive"))
    )
    (net (code "164") (name "PCLK_A0") (class "Default")
      (node (ref "U2") (pin "55") (pinfunction "1A1_55") (pintype "input"))
      (node (ref "U4") (pin "30") (pinfunction "2A10_30") (pintype "input"))
      (node (ref "U5") (pin "14") (pinfunction "Q0_14") (pintype "output"))
    )
    (net (code "165") (name "PCLK_A1") (class "Default")
      (node (ref "U2") (pin "54") (pinfunction "1A2_54") (pintype "input"))
      (node (ref "U4") (pin "31") (pinfunction "2A9_31") (pintype "input"))
      (node (ref "U5") (pin "13") (pinfunction "Q1_13") (pintype "output"))
    )
    (net (code "166") (name "PCLK_A2") (class "Default")
      (node (ref "U2") (pin "52") (pinfunction "1A3_52") (pintype "input"))
      (node (ref "U4") (pin "33") (pinfunction "2A8_33") (pintype "input"))
      (node (ref "U5") (pin "12") (pinfunction "Q2_12") (pintype "output"))
    )
    (net (code "167") (name "PCLK_A3") (class "Default")
      (node (ref "U2") (pin "51") (pinfunction "1A4_51") (pintype "input"))
      (node (ref "U4") (pin "34") (pinfunction "2A7_34") (pintype "input"))
      (node (ref "U5") (pin "11") (pinfunction "Q3_11") (pintype "output"))
    )
    (net (code "168") (name "PCLK_A4") (class "Default")
      (node (ref "U12") (pin "14") (pinfunction "Q0_14") (pintype "output"))
      (node (ref "U2") (pin "49") (pinfunction "1A5_49") (pintype "input"))
      (node (ref "U4") (pin "36") (pinfunction "2A6_36") (pintype "input"))
    )
    (net (code "169") (name "PCLK_A5") (class "Default")
      (node (ref "U12") (pin "13") (pinfunction "Q1_13") (pintype "output"))
      (node (ref "U2") (pin "48") (pinfunction "1A6_48") (pintype "input"))
      (node (ref "U4") (pin "37") (pinfunction "2A5_37") (pintype "input"))
    )
    (net (code "170") (name "PCLK_A6") (class "Default")
      (node (ref "U12") (pin "12") (pinfunction "Q2_12") (pintype "output"))
      (node (ref "U2") (pin "47") (pinfunction "1A7_47") (pintype "input"))
      (node (ref "U4") (pin "38") (pinfunction "2A4_38") (pintype "input"))
    )
    (net (code "171") (name "PCLK_A7") (class "Default")
      (node (ref "U12") (pin "11") (pinfunction "Q3_11") (pintype "output"))
      (node (ref "U2") (pin "45") (pinfunction "1A8_45") (pintype "input"))
      (node (ref "U4") (pin "40") (pinfunction "2A3_40") (pintype "input"))
    )
    (net (code "172") (name "PCLK_A8") (class "Default")
      (node (ref "U14") (pin "14") (pinfunction "Q0_14") (pintype "output"))
      (node (ref "U2") (pin "44") (pinfunction "1A9_44") (pintype "input"))
      (node (ref "U4") (pin "41") (pinfunction "2A2_41") (pintype "input"))
    )
    (net (code "173") (name "PCLK_A9") (class "Default")
      (node (ref "U14") (pin "13") (pinfunction "Q1_13") (pintype "output"))
      (node (ref "U2") (pin "43") (pinfunction "1A10_43") (pintype "input"))
      (node (ref "U4") (pin "42") (pinfunction "2A1_42") (pintype "input"))
    )
    (net (code "174") (name "PCLK_A10") (class "Default")
      (node (ref "U14") (pin "12") (pinfunction "Q2_12") (pintype "output"))
      (node (ref "U2") (pin "42") (pinfunction "2A1_42") (pintype "input"))
      (node (ref "U4") (pin "43") (pinfunction "1A10_43") (pintype "input"))
    )
    (net (code "175") (name "PCLK_A11") (class "Default")
      (node (ref "U14") (pin "11") (pinfunction "Q3_11") (pintype "output"))
      (node (ref "U2") (pin "41") (pinfunction "2A2_41") (pintype "input"))
      (node (ref "U4") (pin "44") (pinfunction "1A9_44") (pintype "input"))
    )
    (net (code "176") (name "PCLK_A12") (class "Default")
      (node (ref "U15") (pin "14") (pinfunction "Q0_14") (pintype "output"))
      (node (ref "U2") (pin "40") (pinfunction "2A3_40") (pintype "input"))
      (node (ref "U4") (pin "45") (pinfunction "1A8_45") (pintype "input"))
    )
    (net (code "177") (name "PCLK_A13") (class "Default")
      (node (ref "U15") (pin "13") (pinfunction "Q1_13") (pintype "output"))
      (node (ref "U2") (pin "38") (pinfunction "2A4_38") (pintype "input"))
      (node (ref "U4") (pin "47") (pinfunction "1A7_47") (pintype "input"))
    )
    (net (code "178") (name "PCLK_A14") (class "Default")
      (node (ref "U15") (pin "12") (pinfunction "Q2_12") (pintype "output"))
      (node (ref "U2") (pin "37") (pinfunction "2A5_37") (pintype "input"))
      (node (ref "U4") (pin "48") (pinfunction "1A6_48") (pintype "input"))
    )
    (net (code "179") (name "PCLK_A15") (class "Default")
      (node (ref "U15") (pin "11") (pinfunction "Q3_11") (pintype "output"))
      (node (ref "U2") (pin "36") (pinfunction "2A6_36") (pintype "input"))
      (node (ref "U4") (pin "49") (pinfunction "1A5_49") (pintype "input"))
    )
    (net (code "180") (name "PCLK_A16") (class "Default")
      (node (ref "U16") (pin "14") (pinfunction "Q0_14") (pintype "output"))
      (node (ref "U2") (pin "34") (pinfunction "2A7_34") (pintype "input"))
      (node (ref "U4") (pin "51") (pinfunction "1A4_51") (pintype "input"))
    )
    (net (code "181") (name "PCLK_A17") (class "Default")
      (node (ref "U16") (pin "13") (pinfunction "Q1_13") (pintype "output"))
      (node (ref "U2") (pin "33") (pinfunction "2A8_33") (pintype "input"))
      (node (ref "U4") (pin "52") (pinfunction "1A3_52") (pintype "input"))
    )
    (net (code "182") (name "PCLK_A18") (class "Default")
      (node (ref "U16") (pin "12") (pinfunction "Q2_12") (pintype "output"))
      (node (ref "U2") (pin "31") (pinfunction "2A9_31") (pintype "input"))
      (node (ref "U4") (pin "54") (pinfunction "1A2_54") (pintype "input"))
    )
    (net (code "183") (name "PCLK_A19") (class "Default")
      (node (ref "U16") (pin "11") (pinfunction "Q3_11") (pintype "output"))
      (node (ref "U2") (pin "30") (pinfunction "2A10_30") (pintype "input"))
      (node (ref "U4") (pin "55") (pinfunction "1A1_55") (pintype "input"))
    )
    (net (code "184") (name "R0") (class "Default")
      (node (ref "ADV7125") (pin "43") (pinfunction "R2_43") (pintype "input"))
      (node (ref "ADV7125") (pin "46") (pinfunction "R5_46") (pintype "input"))
      (node (ref "U10") (pin "16") (pinfunction "B3_16") (pintype "output"))
      (node (ref "U11") (pin "13") (pinfunction "B6_13") (pintype "output"))
    )
    (net (code "185") (name "R1") (class "Default")
      (node (ref "ADV7125") (pin "41") (pinfunction "R0_41") (pintype "input"))
      (node (ref "ADV7125") (pin "44") (pinfunction "R3_44") (pintype "input"))
      (node (ref "ADV7125") (pin "47") (pinfunction "R6_47") (pintype "input"))
      (node (ref "U10") (pin "17") (pinfunction "B2_17") (pintype "output"))
      (node (ref "U11") (pin "12") (pinfunction "B7_12") (pintype "output"))
    )
    (net (code "186") (name "R2") (class "Default")
      (node (ref "ADV7125") (pin "42") (pinfunction "R1_42") (pintype "input"))
      (node (ref "ADV7125") (pin "45") (pinfunction "R4_45") (pintype "input"))
      (node (ref "ADV7125") (pin "48") (pinfunction "R7_48") (pintype "input"))
      (node (ref "U10") (pin "18") (pinfunction "B1_18") (pintype "output"))
      (node (ref "U11") (pin "11") (pinfunction "B8_11") (pintype "output"))
    )
    (net (code "187") (name "RESET") (class "Default")
      (node (ref "U22") (pin "10") (pinfunction "MR_10") (pintype "input"))
      (node (ref "U23") (pin "10") (pinfunction "MR_10") (pintype "input"))
      (node (ref "U24") (pin "10") (pinfunction "MR_10") (pintype "input"))
      (node (ref "U25") (pin "10") (pinfunction "MR_10") (pintype "input"))
      (node (ref "U7") (pin "6") (pinfunction "~{Q}_6") (pintype "output"))
    )
    (net (code "188") (name "SCLK") (class "Default")
      (node (ref "LPC1769") (pin "13") (pinfunction "13_13") (pintype "passive"))
      (node (ref "R10") (pin "1") (pinfunction "1_1") (pintype "passive"))
      (node (ref "U22") (pin "11") (pinfunction "SHCP_11") (pintype "input"))
      (node (ref "U23") (pin "11") (pinfunction "SHCP_11") (pintype "input"))
      (node (ref "U24") (pin "11") (pinfunction "SHCP_11") (pintype "input"))
      (node (ref "U25") (pin "11") (pinfunction "SHCP_11") (pintype "input"))
      (node (ref "U7") (pin "1") (pinfunction "CLK_1") (pintype "input"))
    )
    (net (code "189") (name "VGA_B") (class "Default")
      (node (ref "ADV7125") (pin "28") (pinfunction "IOB_28") (pintype "output"))
      (node (ref "J1") (pin "3") (pinfunction "BLUE_3") (pintype "passive"))
      (node (ref "R4") (pin "2") (pinfunction "2_2") (pintype "passive"))
    )
    (net (code "190") (name "VGA_G") (class "Default")
      (node (ref "ADV7125") (pin "32") (pinfunction "IOG_32") (pintype "output"))
      (node (ref "J1") (pin "2") (pinfunction "GREEN_2") (pintype "passive"))
      (node (ref "R3") (pin "2") (pinfunction "2_2") (pintype "passive"))
    )
    (net (code "191") (name "VGA_R") (class "Default")
      (node (ref "ADV7125") (pin "34") (pinfunction "IOR_34") (pintype "output"))
      (node (ref "J1") (pin "1") (pinfunction "RED_1") (pintype "passive"))
      (node (ref "R2") (pin "2") (pinfunction "2_2") (pintype "passive"))
    )
    (net (code "192") (name "VS") (class "Default")
      (node (ref "IC6") (pin "18") (pinfunction "I/O4_18") (pintype "bidirectional"))
      (node (ref "U29") (pin "14") (pinfunction "J_14") (pintype "input"))
    )
    (net (code "193") (name "VSYNC") (class "Default")
      (node (ref "J1") (pin "14") (pinfunction "VSYNC_14") (pintype "passive"))
      (node (ref "LPC1769") (pin "12") (pinfunction "12_12") (pintype "passive"))
      (node (ref "U28") (pin "3") (pinfunction "CLK_3") (pintype "input"))
      (node (ref "U29") (pin "10") (pinfunction "Q_10") (pintype "output"))
    )
    (net (code "194") (name "V_BLANK") (class "Default")
      (node (ref "IC6") (pin "19") (pinfunction "I/O5_19") (pintype "bidirectional"))
      (node (ref "U30") (pin "14") (pinfunction "J_14") (pintype "input"))
    )
    (net (code "195") (name "W_LATCH") (class "Default")
      (node (ref "U27") (pin "2") (pinfunction "A_2") (pintype "input"))
      (node (ref "U31") (pin "2") (pinfunction "A_2") (pintype "input"))
      (node (ref "U7") (pin "5") (pinfunction "Q_5") (pintype "output"))
    )
    (net (code "196") (name "unconnected-(IC6A-I{slash}O0-Pad14)") (class "Default")
      (node (ref "IC6") (pin "14") (pinfunction "I/O0_14") (pintype "bidirectional"))
    )
    (net (code "197") (name "unconnected-(IC6A-I{slash}O1-Pad15)") (class "Default")
      (node (ref "IC6") (pin "15") (pinfunction "I/O1_15") (pintype "bidirectional"))
    )
    (net (code "198") (name "unconnected-(IC6A-I{slash}O7-Pad21)") (class "Default")
      (node (ref "IC6") (pin "21") (pinfunction "I/O7_21") (pintype "bidirectional"))
    )
    (net (code "199") (name "unconnected-(IC6A-I{slash}O8-Pad22)") (class "Default")
      (node (ref "IC6") (pin "22") (pinfunction "I/O8_22") (pintype "bidirectional"))
    )
    (net (code "200") (name "unconnected-(IC6A-I{slash}O9-Pad23)") (class "Default")
      (node (ref "IC6") (pin "23") (pinfunction "I/O9_23") (pintype "bidirectional"))
    )
    (net (code "201") (name "unconnected-(IC7A-I{slash}O0-Pad14)") (class "Default")
      (node (ref "IC7") (pin "14") (pinfunction "I/O0_14") (pintype "bidirectional"))
    )
    (net (code "202") (name "unconnected-(IC7A-I{slash}O1-Pad15)") (class "Default")
      (node (ref "IC7") (pin "15") (pinfunction "I/O1_15") (pintype "bidirectional"))
    )
    (net (code "203") (name "unconnected-(IC7A-I{slash}O7-Pad21)") (class "Default")
      (node (ref "IC7") (pin "21") (pinfunction "I/O7_21") (pintype "bidirectional"))
    )
    (net (code "204") (name "unconnected-(IC7A-I{slash}O8-Pad22)") (class "Default")
      (node (ref "IC7") (pin "22") (pinfunction "I/O8_22") (pintype "bidirectional"))
    )
    (net (code "205") (name "unconnected-(IC7A-I{slash}O9-Pad23)") (class "Default")
      (node (ref "IC7") (pin "23") (pinfunction "I/O9_23") (pintype "bidirectional"))
    )
    (net (code "206") (name "unconnected-(J1-16-PadP$1)") (class "Default")
      (node (ref "J1") (pin "P$1") (pinfunction "16_P$1") (pintype "passive"))
    )
    (net (code "207") (name "unconnected-(J1-17-PadP$2)") (class "Default")
      (node (ref "J1") (pin "P$2") (pinfunction "17_P$2") (pintype "passive"))
    )
    (net (code "208") (name "unconnected-(J1-NC-Pad4)") (class "Default")
      (node (ref "J1") (pin "4") (pinfunction "NC_4") (pintype "passive"))
    )
    (net (code "209") (name "unconnected-(J1-NC-Pad9)") (class "Default")
      (node (ref "J1") (pin "9") (pinfunction "NC_9") (pintype "passive"))
    )
    (net (code "210") (name "unconnected-(J1-NC-Pad11)") (class "Default")
      (node (ref "J1") (pin "11") (pinfunction "NC_11") (pintype "passive"))
    )
    (net (code "211") (name "unconnected-(J1-SCL-Pad15)") (class "Default")
      (node (ref "J1") (pin "15") (pinfunction "SCL_15") (pintype "passive"))
    )
    (net (code "212") (name "unconnected-(J1-SDA-Pad12)") (class "Default")
      (node (ref "J1") (pin "12") (pinfunction "SDA_12") (pintype "passive"))
    )
    (net (code "213") (name "unconnected-(LPC1769-Pad1)") (class "Default")
      (node (ref "LPC1769") (pin "1") (pinfunction "1_1") (pintype "passive"))
    )
    (net (code "214") (name "unconnected-(LPC1769-Pad2)") (class "Default")
      (node (ref "LPC1769") (pin "2") (pinfunction "2_2") (pintype "passive"))
    )
    (net (code "215") (name "unconnected-(LPC1769-Pad3)") (class "Default")
      (node (ref "LPC1769") (pin "3") (pinfunction "3_3") (pintype "passive"))
    )
    (net (code "216") (name "unconnected-(LPC1769-Pad4)") (class "Default")
      (node (ref "LPC1769") (pin "4") (pinfunction "4_4") (pintype "passive"))
    )
    (net (code "217") (name "unconnected-(LPC1769-Pad5)") (class "Default")
      (node (ref "LPC1769") (pin "5") (pinfunction "5_5") (pintype "passive"))
    )
    (net (code "218") (name "unconnected-(LPC1769-Pad6)") (class "Default")
      (node (ref "LPC1769") (pin "6") (pinfunction "6_6") (pintype "passive"))
    )
    (net (code "219") (name "unconnected-(LPC1769-Pad7)") (class "Default")
      (node (ref "LPC1769") (pin "7") (pinfunction "7_7") (pintype "passive"))
    )
    (net (code "220") (name "unconnected-(LPC1769-Pad8)") (class "Default")
      (node (ref "LPC1769") (pin "8") (pinfunction "8_8") (pintype "passive"))
    )
    (net (code "221") (name "unconnected-(LPC1769-Pad9)") (class "Default")
      (node (ref "LPC1769") (pin "9") (pinfunction "9_9") (pintype "passive"))
    )
    (net (code "222") (name "unconnected-(LPC1769-Pad10)") (class "Default")
      (node (ref "LPC1769") (pin "10") (pinfunction "10_10") (pintype "passive"))
    )
    (net (code "223") (name "unconnected-(LPC1769-Pad15)") (class "Default")
      (node (ref "LPC1769") (pin "15") (pinfunction "15_15") (pintype "passive"))
    )
    (net (code "224") (name "unconnected-(LPC1769-Pad16)") (class "Default")
      (node (ref "LPC1769") (pin "16") (pinfunction "16_16") (pintype "passive"))
    )
    (net (code "225") (name "unconnected-(LPC1769-Pad17)") (class "Default")
      (node (ref "LPC1769") (pin "17") (pinfunction "17_17") (pintype "passive"))
    )
    (net (code "226") (name "unconnected-(LPC1769-Pad18)") (class "Default")
      (node (ref "LPC1769") (pin "18") (pinfunction "18_18") (pintype "passive"))
    )
    (net (code "227") (name "unconnected-(LPC1769-Pad19)") (class "Default")
      (node (ref "LPC1769") (pin "19") (pinfunction "19_19") (pintype "passive"))
    )
    (net (code "228") (name "unconnected-(LPC1769-Pad20)") (class "Default")
      (node (ref "LPC1769") (pin "20") (pinfunction "20_20") (pintype "passive"))
    )
    (net (code "229") (name "unconnected-(LPC1769-Pad21)") (class "Default")
      (node (ref "LPC1769") (pin "21") (pinfunction "21_21") (pintype "passive"))
    )
    (net (code "230") (name "unconnected-(LPC1769-Pad22)") (class "Default")
      (node (ref "LPC1769") (pin "22") (pinfunction "22_22") (pintype "passive"))
    )
    (net (code "231") (name "unconnected-(LPC1769-Pad23)") (class "Default")
      (node (ref "LPC1769") (pin "23") (pinfunction "23_23") (pintype "passive"))
    )
    (net (code "232") (name "unconnected-(LPC1769-Pad24)") (class "Default")
      (node (ref "LPC1769") (pin "24") (pinfunction "24_24") (pintype "passive"))
    )
    (net (code "233") (name "unconnected-(LPC1769-Pad25)") (class "Default")
      (node (ref "LPC1769") (pin "25") (pinfunction "25_25") (pintype "passive"))
    )
    (net (code "234") (name "unconnected-(LPC1769-Pad26)") (class "Default")
      (node (ref "LPC1769") (pin "26") (pinfunction "26_26") (pintype "passive"))
    )
    (net (code "235") (name "unconnected-(LPC1769-Pad27)") (class "Default")
      (node (ref "LPC1769") (pin "27") (pinfunction "27_27") (pintype "passive"))
    )
    (net (code "236") (name "unconnected-(LPC1769-Pad29)") (class "Default")
      (node (ref "LPC1769") (pin "29") (pinfunction "29_29") (pintype "passive"))
    )
    (net (code "237") (name "unconnected-(LPC1769-Pad30)") (class "Default")
      (node (ref "LPC1769") (pin "30") (pinfunction "30_30") (pintype "passive"))
    )
    (net (code "238") (name "unconnected-(LPC1769-Pad31)") (class "Default")
      (node (ref "LPC1769") (pin "31") (pinfunction "31_31") (pintype "passive"))
    )
    (net (code "239") (name "unconnected-(LPC1769-Pad32)") (class "Default")
      (node (ref "LPC1769") (pin "32") (pinfunction "32_32") (pintype "passive"))
    )
    (net (code "240") (name "unconnected-(LPC1769-Pad33)") (class "Default")
      (node (ref "LPC1769") (pin "33") (pinfunction "33_33") (pintype "passive"))
    )
    (net (code "241") (name "unconnected-(LPC1769-Pad34)") (class "Default")
      (node (ref "LPC1769") (pin "34") (pinfunction "34_34") (pintype "passive"))
    )
    (net (code "242") (name "unconnected-(LPC1769-Pad35)") (class "Default")
      (node (ref "LPC1769") (pin "35") (pinfunction "35_35") (pintype "passive"))
    )
    (net (code "243") (name "unconnected-(LPC1769-Pad36)") (class "Default")
      (node (ref "LPC1769") (pin "36") (pinfunction "36_36") (pintype "passive"))
    )
    (net (code "244") (name "unconnected-(LPC1769-Pad37)") (class "Default")
      (node (ref "LPC1769") (pin "37") (pinfunction "37_37") (pintype "passive"))
    )
    (net (code "245") (name "unconnected-(LPC1769-Pad38)") (class "Default")
      (node (ref "LPC1769") (pin "38") (pinfunction "38_38") (pintype "passive"))
    )
    (net (code "246") (name "unconnected-(LPC1769-Pad39)") (class "Default")
      (node (ref "LPC1769") (pin "39") (pinfunction "39_39") (pintype "passive"))
    )
    (net (code "247") (name "unconnected-(LPC1769-Pad40)") (class "Default")
      (node (ref "LPC1769") (pin "40") (pinfunction "40_40") (pintype "passive"))
    )
    (net (code "248") (name "unconnected-(LPC1769-Pad41)") (class "Default")
      (node (ref "LPC1769") (pin "41") (pinfunction "41_41") (pintype "passive"))
    )
    (net (code "249") (name "unconnected-(LPC1769-Pad42)") (class "Default")
      (node (ref "LPC1769") (pin "42") (pinfunction "42_42") (pintype "passive"))
    )
    (net (code "250") (name "unconnected-(LPC1769-Pad43)") (class "Default")
      (node (ref "LPC1769") (pin "43") (pinfunction "43_43") (pintype "passive"))
    )
    (net (code "251") (name "unconnected-(LPC1769-Pad44)") (class "Default")
      (node (ref "LPC1769") (pin "44") (pinfunction "44_44") (pintype "passive"))
    )
    (net (code "252") (name "unconnected-(LPC1769-Pad45)") (class "Default")
      (node (ref "LPC1769") (pin "45") (pinfunction "45_45") (pintype "passive"))
    )
    (net (code "253") (name "unconnected-(LPC1769-Pad46)") (class "Default")
      (node (ref "LPC1769") (pin "46") (pinfunction "46_46") (pintype "passive"))
    )
    (net (code "254") (name "unconnected-(LPC1769-Pad47)") (class "Default")
      (node (ref "LPC1769") (pin "47") (pinfunction "47_47") (pintype "passive"))
    )
    (net (code "255") (name "unconnected-(LPC1769-Pad48)") (class "Default")
      (node (ref "LPC1769") (pin "48") (pinfunction "48_48") (pintype "passive"))
    )
    (net (code "256") (name "unconnected-(LPC1769-Pad49)") (class "Default")
      (node (ref "LPC1769") (pin "49") (pinfunction "49_49") (pintype "passive"))
    )
    (net (code "257") (name "unconnected-(LPC1769-Pad50)") (class "Default")
      (node (ref "LPC1769") (pin "50") (pinfunction "50_50") (pintype "passive"))
    )
    (net (code "258") (name "unconnected-(LPC1769-Pad51)") (class "Default")
      (node (ref "LPC1769") (pin "51") (pinfunction "51_51") (pintype "passive"))
    )
    (net (code "259") (name "unconnected-(LPC1769-Pad52)") (class "Default")
      (node (ref "LPC1769") (pin "52") (pinfunction "52_52") (pintype "passive"))
    )
    (net (code "260") (name "unconnected-(LPC1769-Pad53)") (class "Default")
      (node (ref "LPC1769") (pin "53") (pinfunction "53_53") (pintype "passive"))
    )
    (net (code "261") (name "unconnected-(LPC1769-Pad55)") (class "Default")
      (node (ref "LPC1769") (pin "55") (pinfunction "55_55") (pintype "passive"))
    )
    (net (code "262") (name "unconnected-(LPC1769-Pad56)") (class "Default")
      (node (ref "LPC1769") (pin "56") (pinfunction "56_56") (pintype "passive"))
    )
    (net (code "263") (name "unconnected-(LPC1769-Pad57)") (class "Default")
      (node (ref "LPC1769") (pin "57") (pinfunction "57_57") (pintype "passive"))
    )
    (net (code "264") (name "unconnected-(LPC1769-Pad58)") (class "Default")
      (node (ref "LPC1769") (pin "58") (pinfunction "58_58") (pintype "passive"))
    )
    (net (code "265") (name "unconnected-(LPC1769-Pad59)") (class "Default")
      (node (ref "LPC1769") (pin "59") (pinfunction "59_59") (pintype "passive"))
    )
    (net (code "266") (name "unconnected-(LPC1769-Pad60)") (class "Default")
      (node (ref "LPC1769") (pin "60") (pinfunction "60_60") (pintype "passive"))
    )
    (net (code "267") (name "unconnected-(LPC1769-Pad61)") (class "Default")
      (node (ref "LPC1769") (pin "61") (pinfunction "61_61") (pintype "passive"))
    )
    (net (code "268") (name "unconnected-(LPC1769-Pad62)") (class "Default")
      (node (ref "LPC1769") (pin "62") (pinfunction "62_62") (pintype "passive"))
    )
    (net (code "269") (name "unconnected-(LPC1769-Pad63)") (class "Default")
      (node (ref "LPC1769") (pin "63") (pinfunction "63_63") (pintype "passive"))
    )
    (net (code "270") (name "unconnected-(LPC1769-Pad64)") (class "Default")
      (node (ref "LPC1769") (pin "64") (pinfunction "64_64") (pintype "passive"))
    )
    (net (code "271") (name "unconnected-(LPC1769-Pad65)") (class "Default")
      (node (ref "LPC1769") (pin "65") (pinfunction "65_65") (pintype "passive"))
    )
    (net (code "272") (name "unconnected-(LPC1769-Pad66)") (class "Default")
      (node (ref "LPC1769") (pin "66") (pinfunction "66_66") (pintype "passive"))
    )
    (net (code "273") (name "unconnected-(LPC1769-Pad67)") (class "Default")
      (node (ref "LPC1769") (pin "67") (pinfunction "67_67") (pintype "passive"))
    )
    (net (code "274") (name "unconnected-(LPC1769-Pad68)") (class "Default")
      (node (ref "LPC1769") (pin "68") (pinfunction "68_68") (pintype "passive"))
    )
    (net (code "275") (name "unconnected-(LPC1769-Pad69)") (class "Default")
      (node (ref "LPC1769") (pin "69") (pinfunction "69_69") (pintype "passive"))
    )
    (net (code "276") (name "unconnected-(LPC1769-Pad70)") (class "Default")
      (node (ref "LPC1769") (pin "70") (pinfunction "70_70") (pintype "passive"))
    )
    (net (code "277") (name "unconnected-(LPC1769-Pad71)") (class "Default")
      (node (ref "LPC1769") (pin "71") (pinfunction "71_71") (pintype "passive"))
    )
    (net (code "278") (name "unconnected-(LPC1769-Pad72)") (class "Default")
      (node (ref "LPC1769") (pin "72") (pinfunction "72_72") (pintype "passive"))
    )
    (net (code "279") (name "unconnected-(LPC1769-Pad73)") (class "Default")
      (node (ref "LPC1769") (pin "73") (pinfunction "73_73") (pintype "passive"))
    )
    (net (code "280") (name "unconnected-(U7B-Q-Pad9)") (class "Default")
      (node (ref "U7") (pin "9") (pinfunction "Q_9") (pintype "output"))
    )
    (net (code "281") (name "unconnected-(U7B-~{Q}-Pad7)") (class "Default")
      (node (ref "U7") (pin "7") (pinfunction "~{Q}_7") (pintype "output"))
    )
    (net (code "282") (name "unconnected-(U16A-TC-Pad15)") (class "Default")
      (node (ref "U16") (pin "15") (pinfunction "TC_15") (pintype "output"))
    )
    (net (code "283") (name "unconnected-(U18A-TC-Pad15)") (class "Default")
      (node (ref "U18") (pin "15") (pinfunction "TC_15") (pintype "output"))
    )
    (net (code "284") (name "unconnected-(U21A-Q2-Pad12)") (class "Default")
      (node (ref "U21") (pin "12") (pinfunction "Q2_12") (pintype "output"))
    )
    (net (code "285") (name "unconnected-(U21A-Q3-Pad11)") (class "Default")
      (node (ref "U21") (pin "11") (pinfunction "Q3_11") (pintype "output"))
    )
    (net (code "286") (name "unconnected-(U21A-TC-Pad15)") (class "Default")
      (node (ref "U21") (pin "15") (pinfunction "TC_15") (pintype "output"))
    )
    (net (code "287") (name "unconnected-(U25A-Q4-Pad4)") (class "Default")
      (node (ref "U25") (pin "4") (pinfunction "Q4_4") (pintype "output"))
    )
    (net (code "288") (name "unconnected-(U25A-Q5-Pad5)") (class "Default")
      (node (ref "U25") (pin "5") (pinfunction "Q5_5") (pintype "output"))
    )
    (net (code "289") (name "unconnected-(U25A-Q6-Pad6)") (class "Default")
      (node (ref "U25") (pin "6") (pinfunction "Q6_6") (pintype "output"))
    )
    (net (code "290") (name "unconnected-(U25A-Q7-Pad7)") (class "Default")
      (node (ref "U25") (pin "7") (pinfunction "Q7_7") (pintype "output"))
    )
    (net (code "291") (name "unconnected-(U28B-Q-Pad9)") (class "Default")
      (node (ref "U28") (pin "9") (pinfunction "Q_9") (pintype "output"))
    )
    (net (code "292") (name "unconnected-(U28B-~{Q}-Pad8)") (class "Default")
      (node (ref "U28") (pin "8") (pinfunction "~{Q}_8") (pintype "output"))
    )
    (net (code "293") (name "unconnected-(U29A-~{Q}-Pad7)") (class "Default")
      (node (ref "U29") (pin "7") (pinfunction "~{Q}_7") (pintype "output"))
    )
    (net (code "294") (name "unconnected-(U29B-~{Q}-Pad9)") (class "Default")
      (node (ref "U29") (pin "9") (pinfunction "~{Q}_9") (pintype "output"))
    )
    (net (code "295") (name "unconnected-(U30A-~{Q}-Pad7)") (class "Default")
      (node (ref "U30") (pin "7") (pinfunction "~{Q}_7") (pintype "output"))
    )
    (net (code "296") (name "unconnected-(U30B-~{Q}-Pad9)") (class "Default")
      (node (ref "U30") (pin "9") (pinfunction "~{Q}_9") (pintype "output"))
    )
    (net (code "297") (name "unconnected-(X1-TS-Pad1)") (class "Default")
      (node (ref "X1") (pin "1") (pinfunction "TS_1") (pintype "passive"))
    )
    (net (code "298") (name "~{BLANK}") (class "Default")
      (node (ref "ADV7125") (pin "11") (pinfunction "~{BLANK}_11") (pintype "input"))
      (node (ref "U13") (pin "4") (pinfunction "Y_4") (pintype "output"))
    )
    (net (code "299") (name "~{HS}") (class "Default")
      (node (ref "IC7") (pin "19") (pinfunction "I/O5_19") (pintype "bidirectional"))
      (node (ref "U29") (pin "3") (pinfunction "K_3") (pintype "input"))
    )
    (net (code "300") (name "~{H_BLANK}") (class "Default")
      (node (ref "IC7") (pin "18") (pinfunction "I/O4_18") (pintype "bidirectional"))
      (node (ref "U30") (pin "3") (pinfunction "K_3") (pintype "input"))
    )
    (net (code "301") (name "~{H_EOL}") (class "Default")
      (node (ref "IC7") (pin "16") (pinfunction "I/O2_16") (pintype "bidirectional"))
      (node (ref "U17") (pin "1") (pinfunction "MR_1") (pintype "input"))
      (node (ref "U18") (pin "1") (pinfunction "MR_1") (pintype "input"))
      (node (ref "U19") (pin "2") (pinfunction "CLK_2") (pintype "input"))
      (node (ref "U20") (pin "2") (pinfunction "CLK_2") (pintype "input"))
      (node (ref "U21") (pin "2") (pinfunction "CLK_2") (pintype "input"))
      (node (ref "U6") (pin "1") (pinfunction "MR_1") (pintype "input"))
    )
    (net (code "302") (name "~{M1_WE}") (class "Default")
      (node (ref "SRAM1") (pin "15") (pinfunction "WE_15") (pintype "input"))
      (node (ref "U27") (pin "4") (pinfunction "Y_4") (pintype "output"))
    )
    (net (code "303") (name "~{M2_WE}") (class "Default")
      (node (ref "SRAM2") (pin "15") (pinfunction "WE_15") (pintype "input"))
      (node (ref "U31") (pin "4") (pinfunction "Y_4") (pintype "output"))
    )
    (net (code "304") (name "~{VS}") (class "Default")
      (node (ref "IC6") (pin "17") (pinfunction "I/O3_17") (pintype "bidirectional"))
      (node (ref "U29") (pin "13") (pinfunction "K_13") (pintype "input"))
    )
    (net (code "305") (name "~{V_BLANK}") (class "Default")
      (node (ref "IC6") (pin "20") (pinfunction "I/O6_20") (pintype "bidirectional"))
      (node (ref "U30") (pin "13") (pinfunction "K_13") (pintype "input"))
    )
    (net (code "306") (name "~{V_EOF}") (class "Default")
      (node (ref "IC6") (pin "16") (pinfunction "I/O2_16") (pintype "bidirectional"))
      (node (ref "U12") (pin "1") (pinfunction "MR_1") (pintype "input"))
      (node (ref "U14") (pin "1") (pinfunction "MR_1") (pintype "input"))
      (node (ref "U15") (pin "1") (pinfunction "MR_1") (pintype "input"))
      (node (ref "U16") (pin "1") (pinfunction "MR_1") (pintype "input"))
      (node (ref "U19") (pin "1") (pinfunction "MR_1") (pintype "input"))
      (node (ref "U20") (pin "1") (pinfunction "MR_1") (pintype "input"))
      (node (ref "U21") (pin "1") (pinfunction "MR_1") (pintype "input"))
      (node (ref "U5") (pin "1") (pinfunction "MR_1") (pintype "input"))
    )
  )
)
